# SCH_Scope_1013D_2023-01-07.net
KiCad netlist of a schematic drawn in EasyEDA
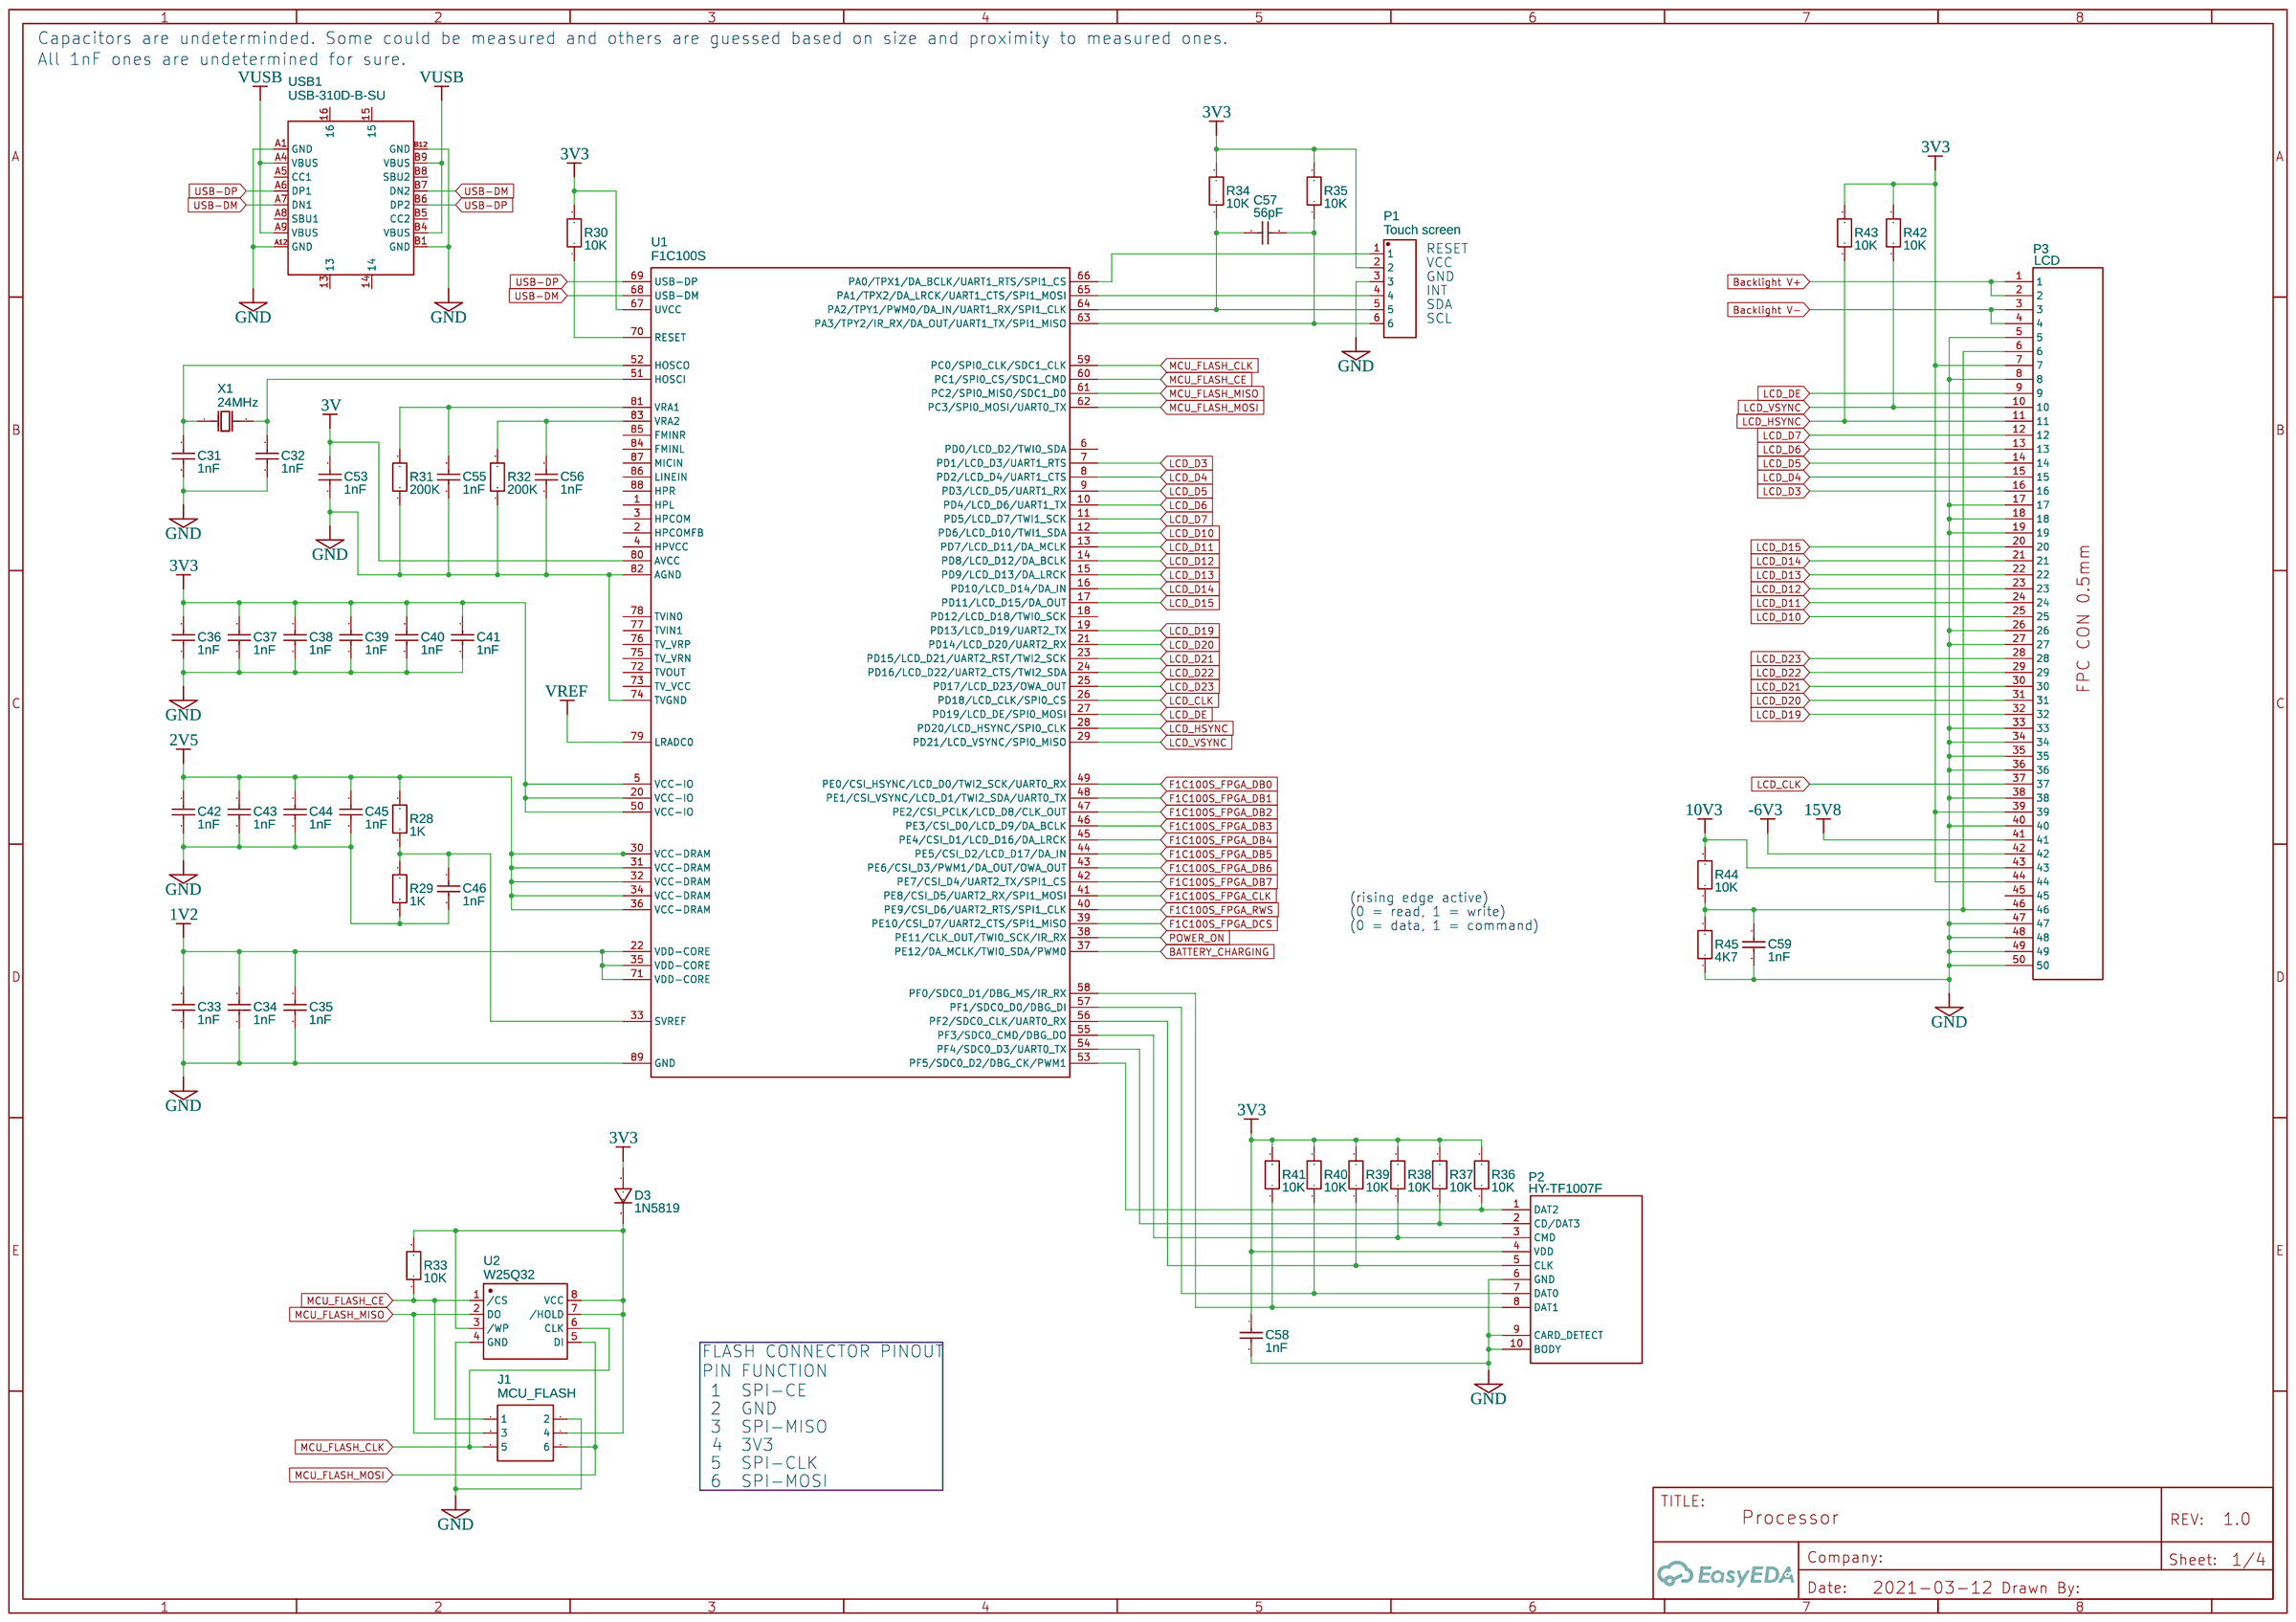
[diagram p0: Scope_Processor]
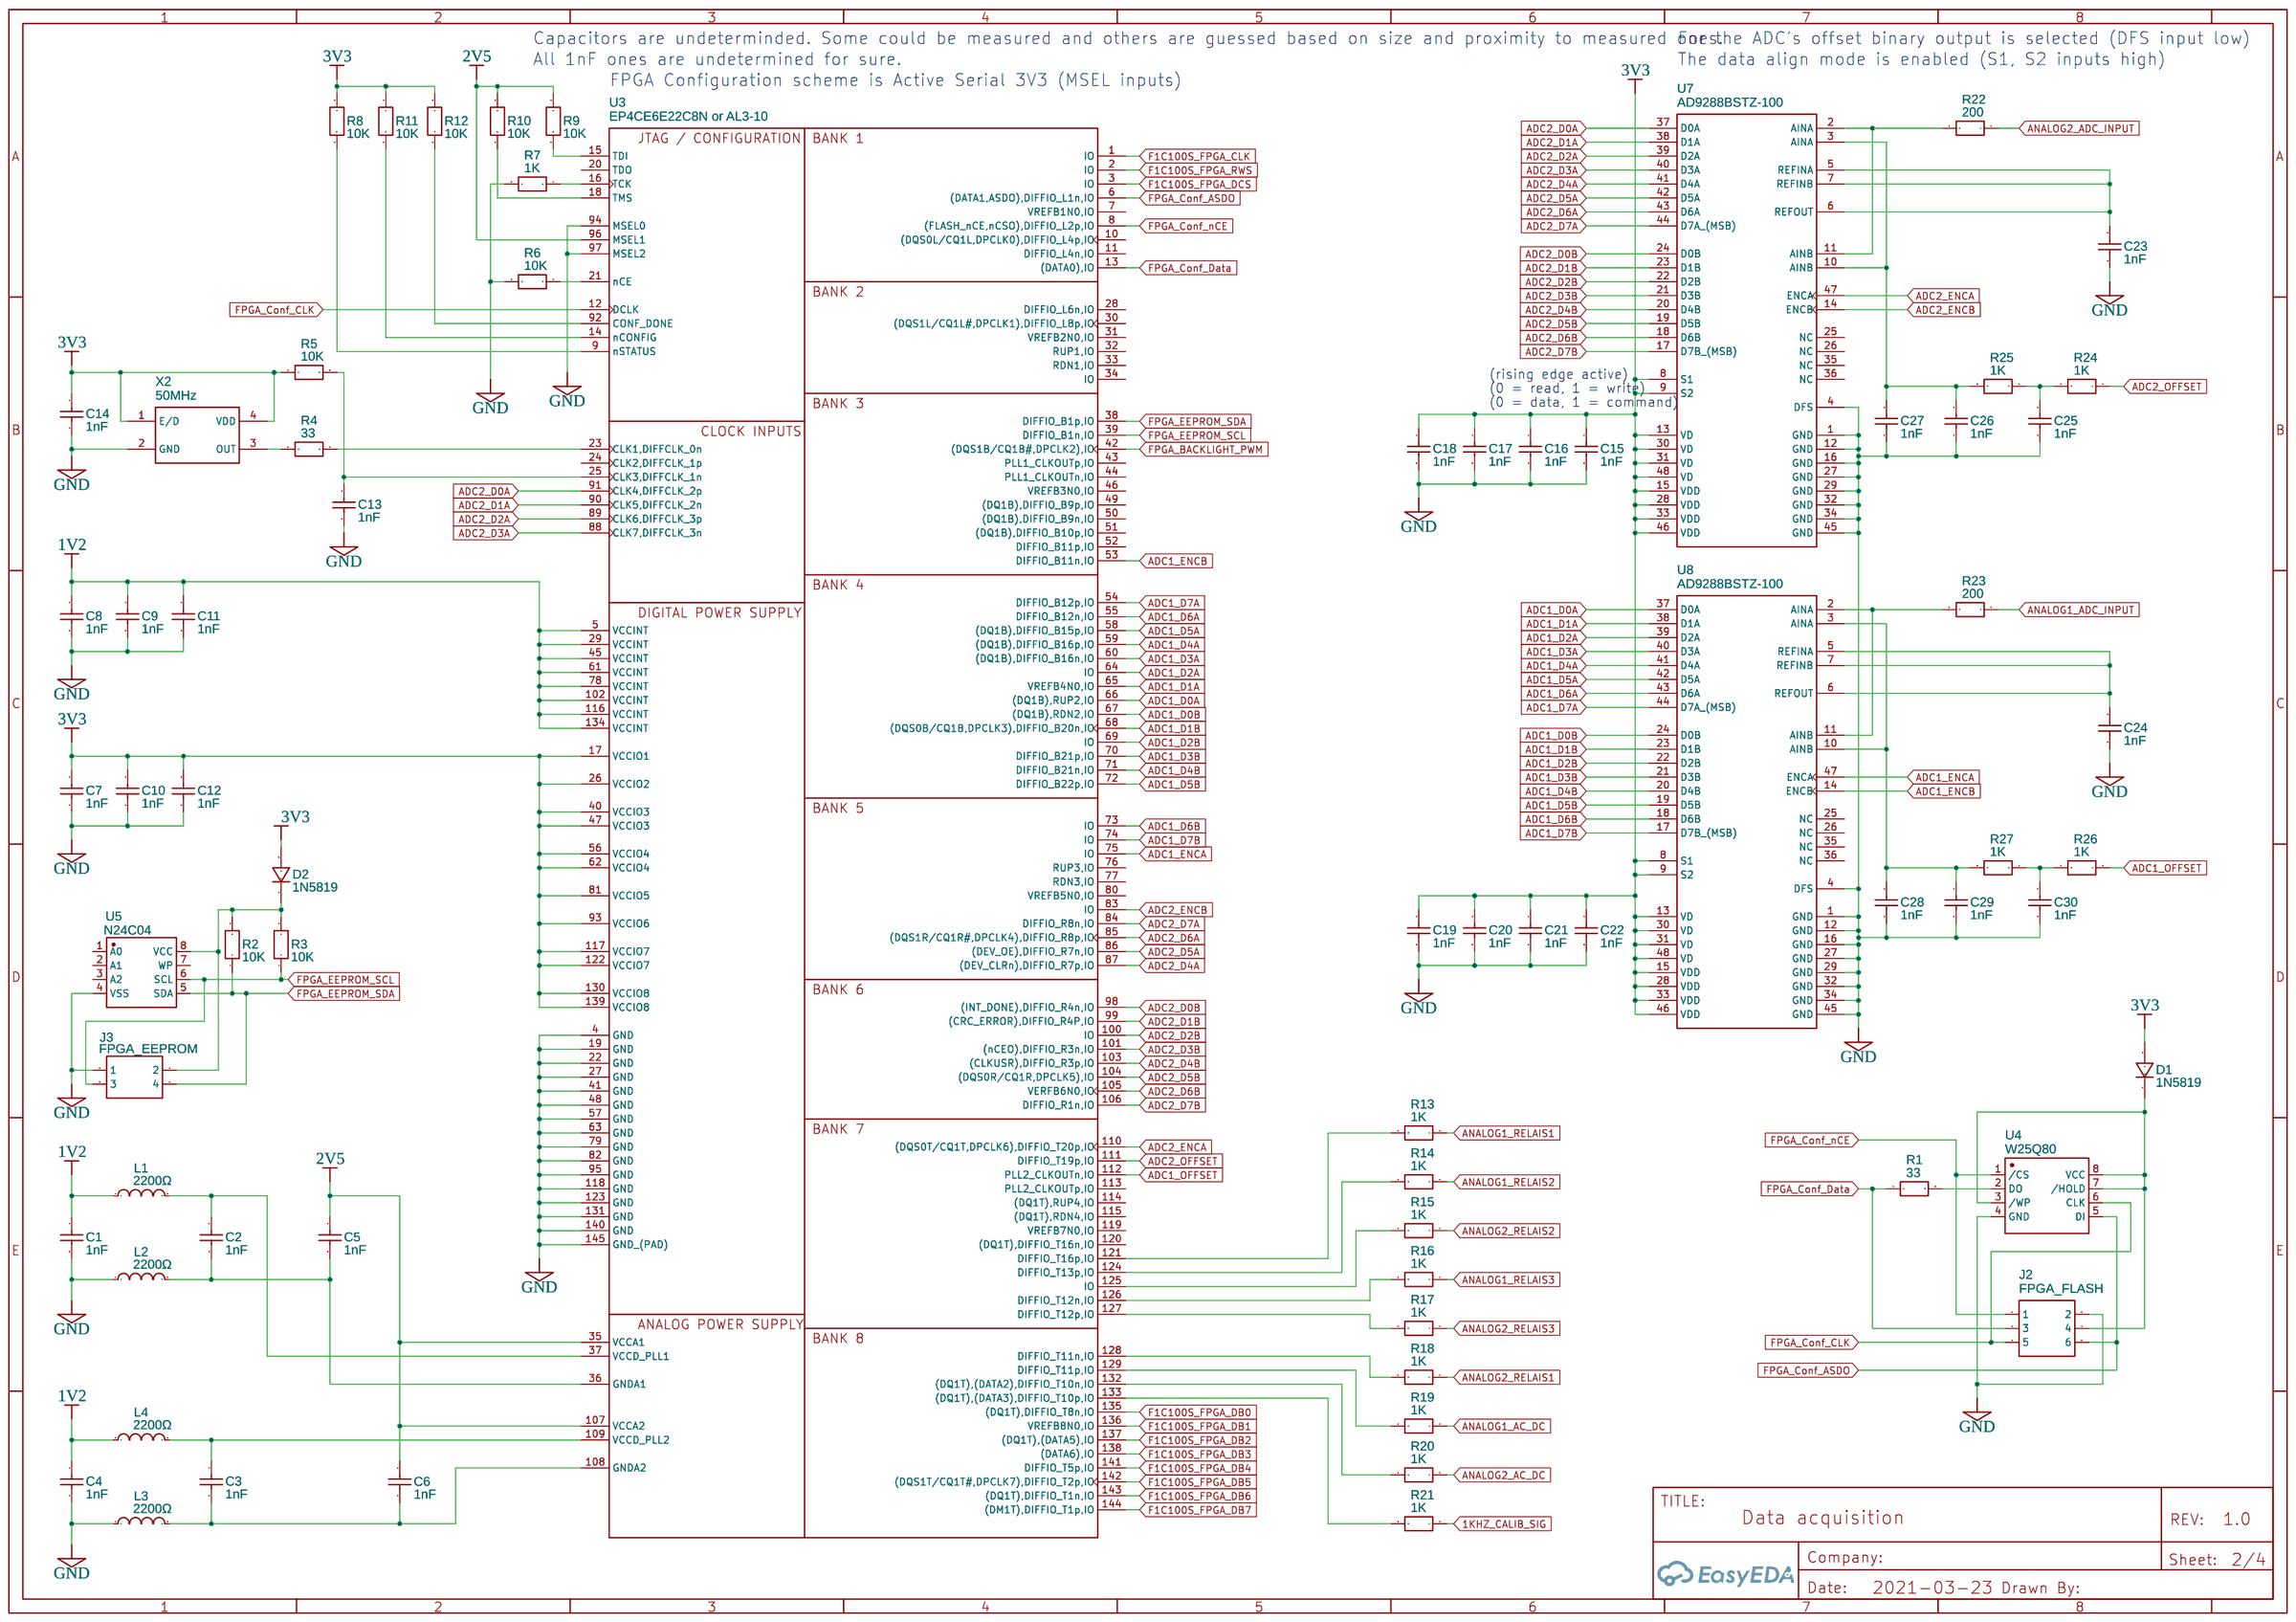
[diagram p1: Scope_Data_Acquisition]
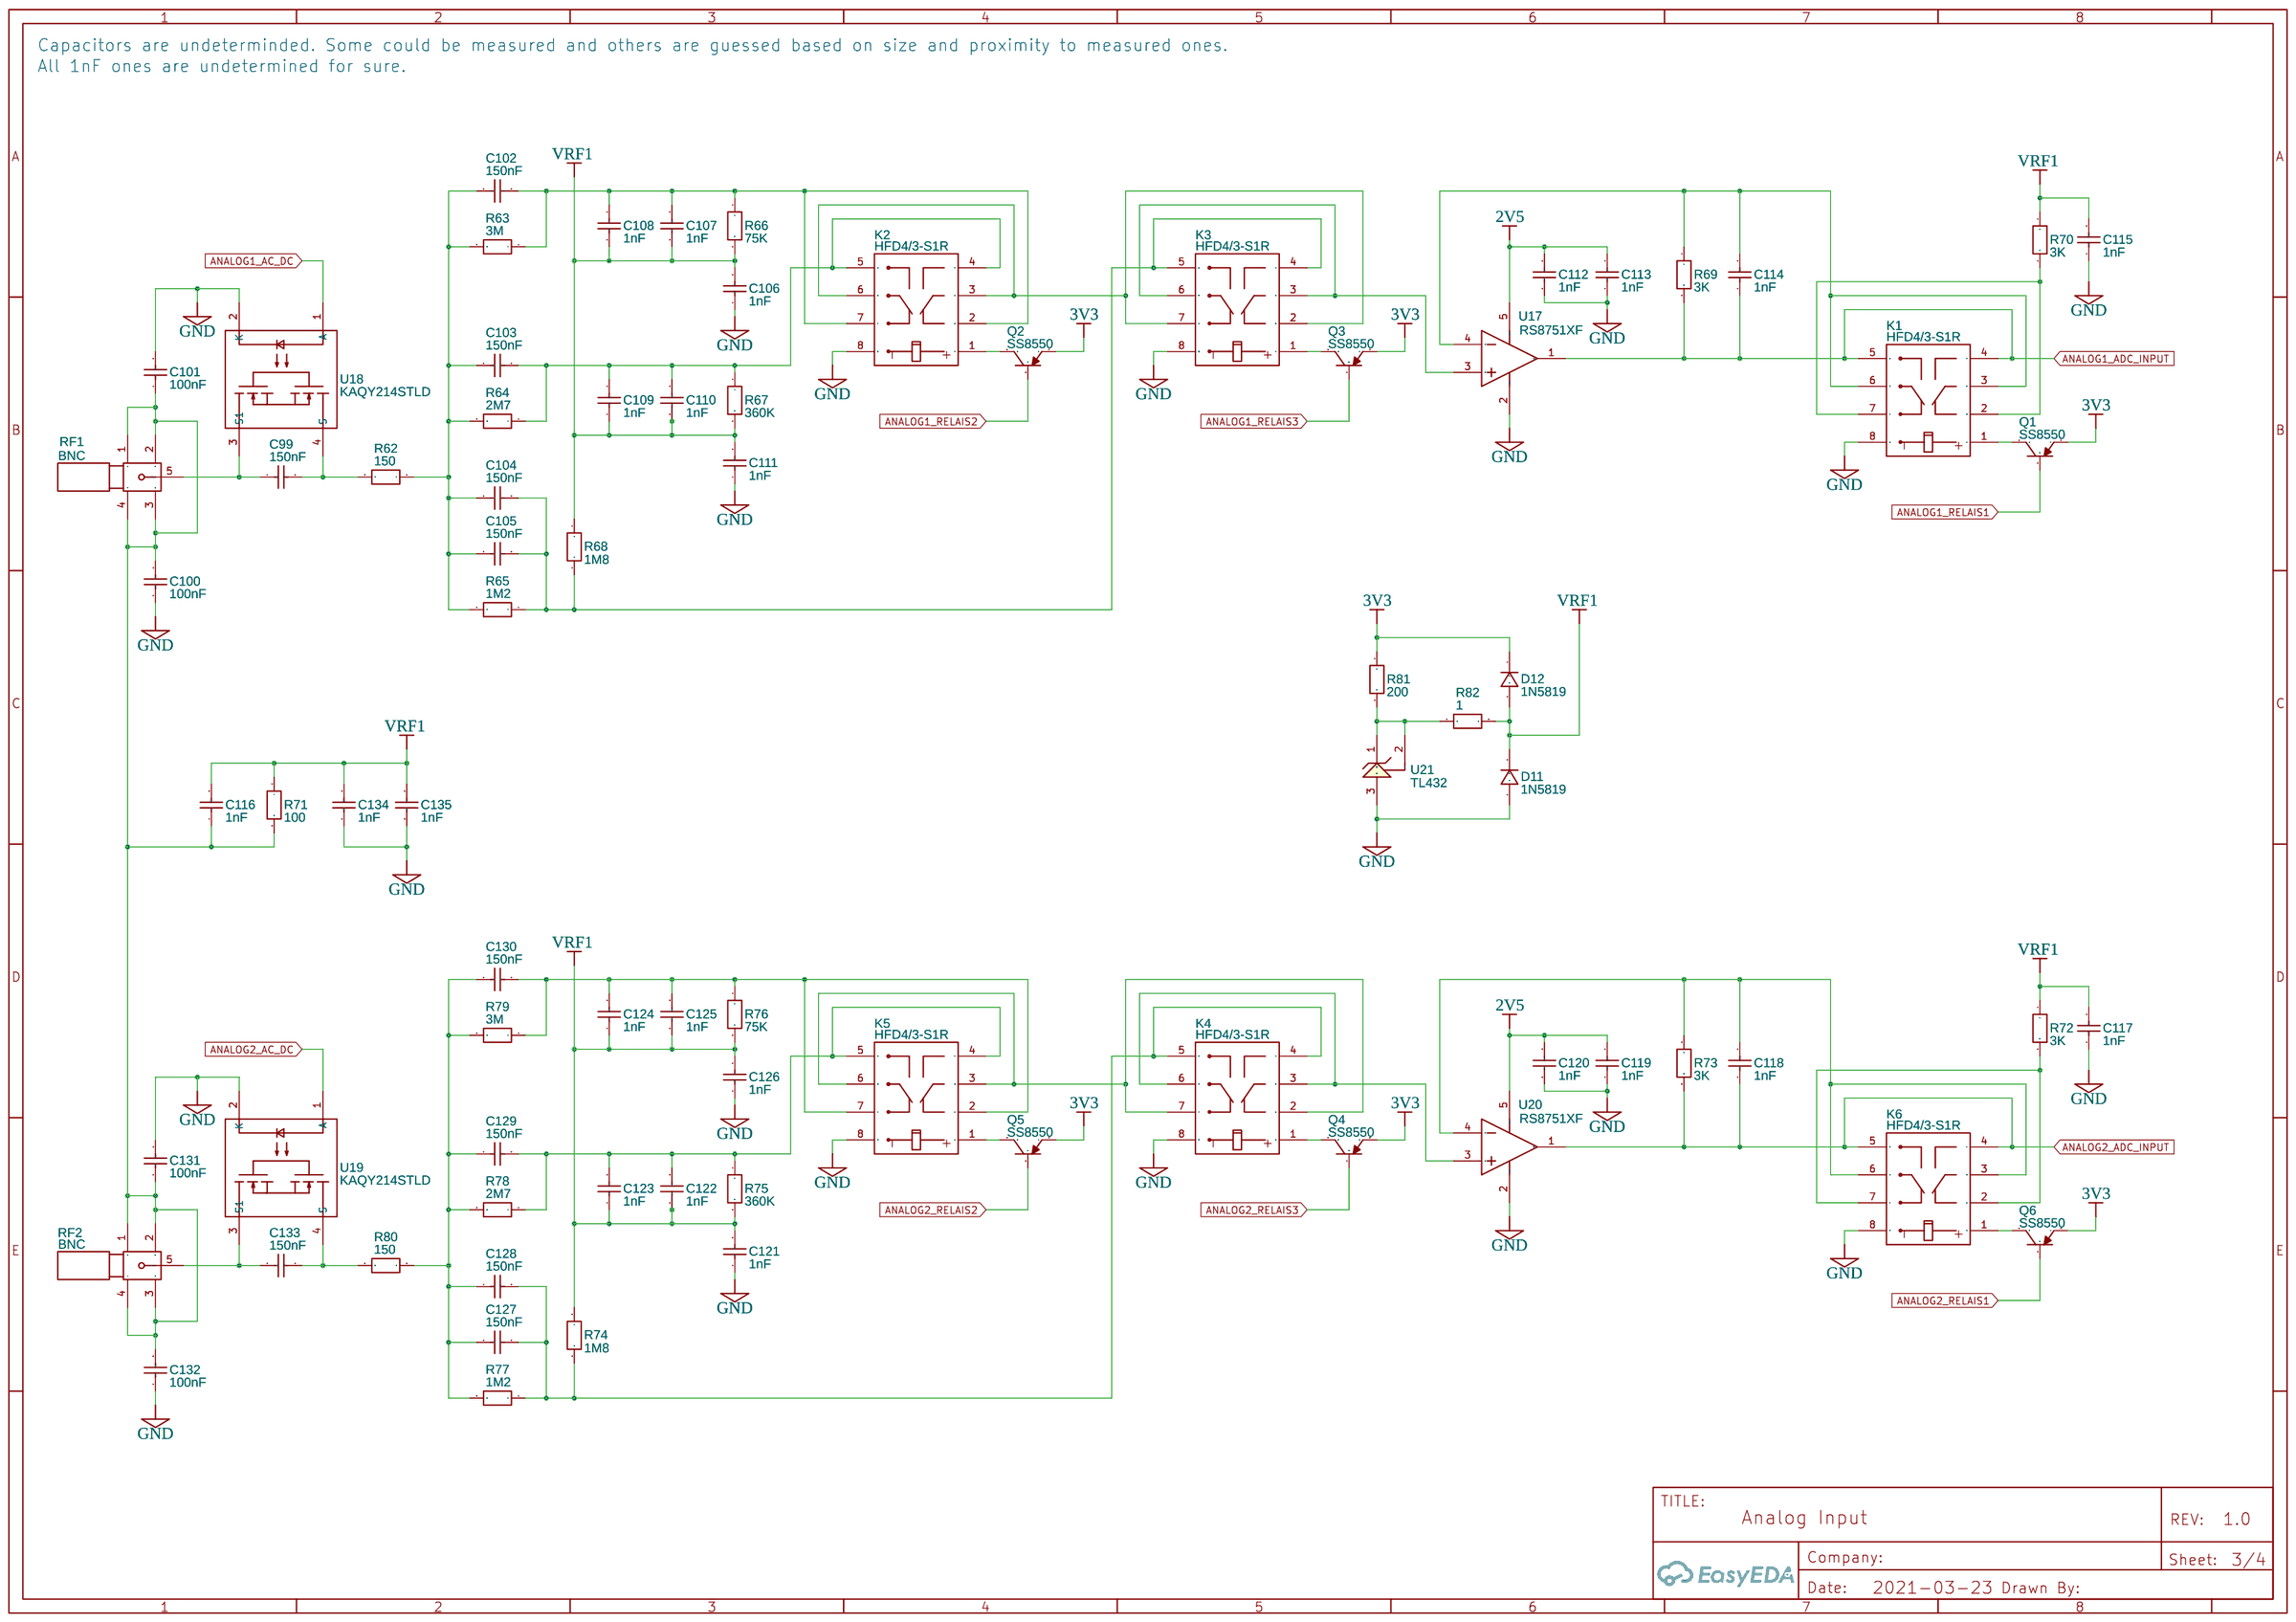
[diagram p2: Scope_Analog_Input]
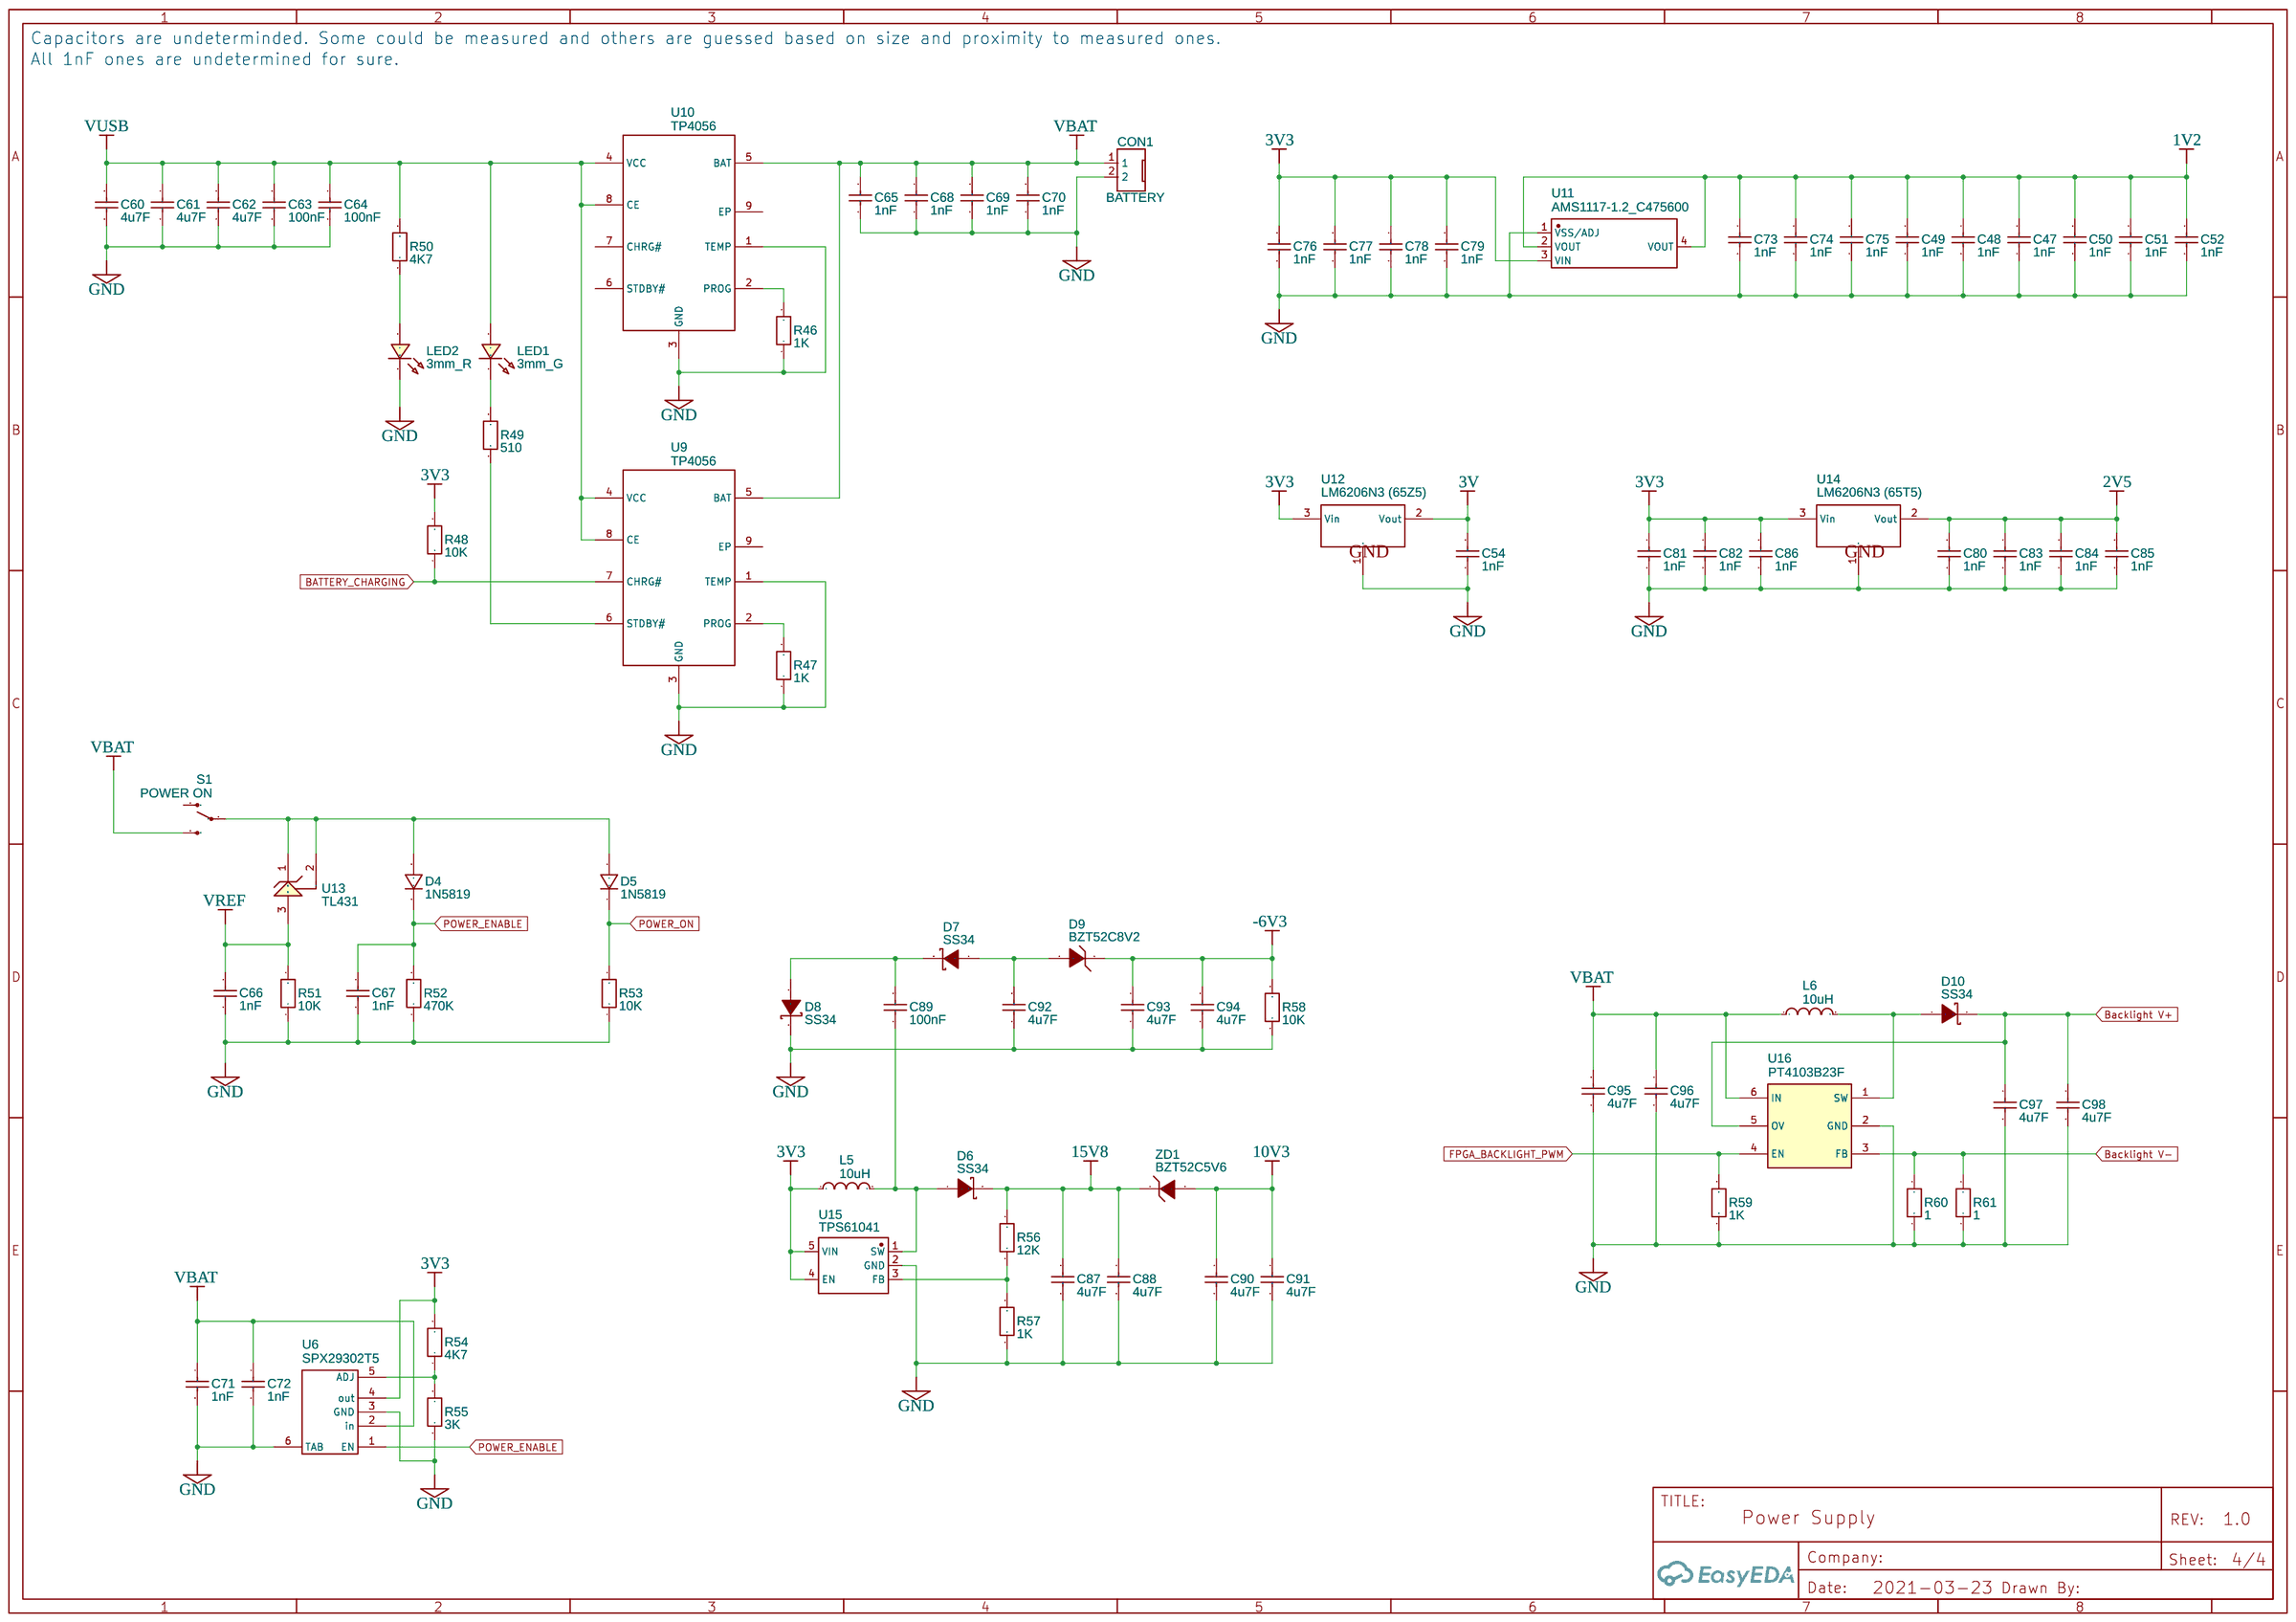
[diagram p3: Scope_Power_Supply]

(export (version "E")
  (design (tool "Eeschema 10.0.6"))
  (components
    (comp (ref "C31")
      (value "1nF")
      (fields
        (field (name "BOM_Manufacturer Part") "GRM31B7U3A471JW31L")
        (field (name "BOM_Supplier Part") "C97936")
      )
      (libsource (lib "") (part "GRM31B7U3A471JW31L"))
    )
    (comp (ref "C32")
      (value "1nF")
      (fields
        (field (name "BOM_Manufacturer Part") "GRM31B7U3A471JW31L")
        (field (name "BOM_Supplier Part") "C97936")
      )
      (libsource (lib "") (part "GRM31B7U3A471JW31L"))
    )
    (comp (ref "C33")
      (value "1nF")
      (fields
        (field (name "BOM_Manufacturer Part") "GRM31B7U3A471JW31L")
        (field (name "BOM_Supplier Part") "C97936")
      )
      (libsource (lib "") (part "GRM31B7U3A471JW31L"))
    )
    (comp (ref "C34")
      (value "1nF")
      (fields
        (field (name "BOM_Manufacturer Part") "GRM31B7U3A471JW31L")
        (field (name "BOM_Supplier Part") "C97936")
      )
      (libsource (lib "") (part "GRM31B7U3A471JW31L"))
    )
    (comp (ref "C35")
      (value "1nF")
      (fields
        (field (name "BOM_Manufacturer Part") "GRM31B7U3A471JW31L")
        (field (name "BOM_Supplier Part") "C97936")
      )
      (libsource (lib "") (part "GRM31B7U3A471JW31L"))
    )
    (comp (ref "C36")
      (value "1nF")
      (fields
        (field (name "BOM_Manufacturer Part") "GRM31B7U3A471JW31L")
        (field (name "BOM_Supplier Part") "C97936")
      )
      (libsource (lib "") (part "GRM31B7U3A471JW31L"))
    )
    (comp (ref "C37")
      (value "1nF")
      (fields
        (field (name "BOM_Manufacturer Part") "GRM31B7U3A471JW31L")
        (field (name "BOM_Supplier Part") "C97936")
      )
      (libsource (lib "") (part "GRM31B7U3A471JW31L"))
    )
    (comp (ref "C38")
      (value "1nF")
      (fields
        (field (name "BOM_Manufacturer Part") "GRM31B7U3A471JW31L")
        (field (name "BOM_Supplier Part") "C97936")
      )
      (libsource (lib "") (part "GRM31B7U3A471JW31L"))
    )
    (comp (ref "C39")
      (value "1nF")
      (fields
        (field (name "BOM_Manufacturer Part") "GRM31B7U3A471JW31L")
        (field (name "BOM_Supplier Part") "C97936")
      )
      (libsource (lib "") (part "GRM31B7U3A471JW31L"))
    )
    (comp (ref "C40")
      (value "1nF")
      (fields
        (field (name "BOM_Manufacturer Part") "GRM31B7U3A471JW31L")
        (field (name "BOM_Supplier Part") "C97936")
      )
      (libsource (lib "") (part "GRM31B7U3A471JW31L"))
    )
    (comp (ref "C41")
      (value "1nF")
      (fields
        (field (name "BOM_Manufacturer Part") "GRM31B7U3A471JW31L")
        (field (name "BOM_Supplier Part") "C97936")
      )
      (libsource (lib "") (part "GRM31B7U3A471JW31L"))
    )
    (comp (ref "C42")
      (value "1nF")
      (fields
        (field (name "BOM_Manufacturer Part") "GRM31B7U3A471JW31L")
        (field (name "BOM_Supplier Part") "C97936")
      )
      (libsource (lib "") (part "GRM31B7U3A471JW31L"))
    )
    (comp (ref "C43")
      (value "1nF")
      (fields
        (field (name "BOM_Manufacturer Part") "GRM31B7U3A471JW31L")
        (field (name "BOM_Supplier Part") "C97936")
      )
      (libsource (lib "") (part "GRM31B7U3A471JW31L"))
    )
    (comp (ref "C44")
      (value "1nF")
      (fields
        (field (name "BOM_Manufacturer Part") "GRM31B7U3A471JW31L")
        (field (name "BOM_Supplier Part") "C97936")
      )
      (libsource (lib "") (part "GRM31B7U3A471JW31L"))
    )
    (comp (ref "C45")
      (value "1nF")
      (fields
        (field (name "BOM_Manufacturer Part") "GRM31B7U3A471JW31L")
        (field (name "BOM_Supplier Part") "C97936")
      )
      (libsource (lib "") (part "GRM31B7U3A471JW31L"))
    )
    (comp (ref "C46")
      (value "1nF")
      (fields
        (field (name "BOM_Manufacturer Part") "GRM31B7U3A471JW31L")
        (field (name "BOM_Supplier Part") "C97936")
      )
      (libsource (lib "") (part "GRM31B7U3A471JW31L"))
    )
    (comp (ref "C53")
      (value "1nF")
      (fields
        (field (name "BOM_Manufacturer Part") "GRM31B7U3A471JW31L")
        (field (name "BOM_Supplier Part") "C97936")
      )
      (libsource (lib "") (part "GRM31B7U3A471JW31L"))
    )
    (comp (ref "C55")
      (value "1nF")
      (fields
        (field (name "BOM_Manufacturer Part") "GRM31B7U3A471JW31L")
        (field (name "BOM_Supplier Part") "C97936")
      )
      (libsource (lib "") (part "GRM31B7U3A471JW31L"))
    )
    (comp (ref "C56")
      (value "1nF")
      (fields
        (field (name "BOM_Manufacturer Part") "GRM31B7U3A471JW31L")
        (field (name "BOM_Supplier Part") "C97936")
      )
      (libsource (lib "") (part "GRM31B7U3A471JW31L"))
    )
    (comp (ref "C57")
      (value "56pF")
      (fields
        (field (name "BOM_Manufacturer Part") "GRM31B7U3A471JW31L")
        (field (name "BOM_Supplier Part") "C97936")
      )
      (libsource (lib "") (part "GRM31B7U3A471JW31L_1"))
    )
    (comp (ref "C58")
      (value "1nF")
      (fields
        (field (name "BOM_Manufacturer Part") "GRM31B7U3A471JW31L")
        (field (name "BOM_Supplier Part") "C97936")
      )
      (libsource (lib "") (part "GRM31B7U3A471JW31L"))
    )
    (comp (ref "C59")
      (value "1nF")
      (fields
        (field (name "BOM_Manufacturer Part") "GRM31B7U3A471JW31L")
        (field (name "BOM_Supplier Part") "C97936")
      )
      (libsource (lib "") (part "GRM31B7U3A471JW31L"))
    )
    (comp (ref "D3")
      (value "1N5819")
      (fields (field (name "BOM_Manufacturer Part") "1N4007") (field (name "BOM_Supplier Part") "C106903"))
      (libsource (lib "") (part "1N4007"))
    )
    (comp (ref "J1")
      (value "MCU_FLASH")
      (fields (field (name "BOM_Supplier Part") "C65114"))
      (libsource (lib "") (part "HDR-M-2.54_2x3"))
    )
    (comp (ref "P1")
      (value "Touch screen")
      (fields (field (name "BOM_Supplier Part") "C11049"))
      (libsource (lib "") (part "FPC-0.5MM-LSXJ-H2.0-6P"))
    )
    (comp (ref "P2")
      (value "HY-TF1007F")
      (fields (field (name "BOM_Supplier Part") "undefined"))
      (libsource (lib "") (part "HY-TF1007F"))
    )
    (comp (ref "P3") (value "LCD") (libsource (lib "") (part "FPC CONNECTOR 50P 0.5mm")))
    (comp (ref "R28") (value "1K") (libsource (lib "") (part "R_0805_EU")))
    (comp (ref "R29") (value "1K") (libsource (lib "") (part "R_0805_EU")))
    (comp (ref "R30") (value "10K") (libsource (lib "") (part "R_0805_EU")))
    (comp (ref "R31") (value "200K") (libsource (lib "") (part "R_0805_EU")))
    (comp (ref "R32") (value "200K") (libsource (lib "") (part "R_0805_EU")))
    (comp (ref "R33") (value "10K") (libsource (lib "") (part "R_0805_EU")))
    (comp (ref "R34") (value "10K") (libsource (lib "") (part "R_0805_EU")))
    (comp (ref "R35") (value "10K") (libsource (lib "") (part "R_0805_EU")))
    (comp (ref "R36") (value "10K") (libsource (lib "") (part "R_0805_EU")))
    (comp (ref "R37") (value "10K") (libsource (lib "") (part "R_0805_EU")))
    (comp (ref "R38") (value "10K") (libsource (lib "") (part "R_0805_EU")))
    (comp (ref "R39") (value "10K") (libsource (lib "") (part "R_0805_EU")))
    (comp (ref "R40") (value "10K") (libsource (lib "") (part "R_0805_EU")))
    (comp (ref "R41") (value "10K") (libsource (lib "") (part "R_0805_EU")))
    (comp (ref "R42") (value "10K") (libsource (lib "") (part "R_0805_EU")))
    (comp (ref "R43") (value "10K") (libsource (lib "") (part "R_0805_EU")))
    (comp (ref "R44") (value "10K") (libsource (lib "") (part "R_0805_EU")))
    (comp (ref "R45") (value "4K7") (libsource (lib "") (part "R_0805_EU")))
    (comp (ref "U1") (value "F1C100S") (libsource (lib "") (part "F1C100S")))
    (comp (ref "U2")
      (value "W25Q32")
      (fields
        (field (name "BOM_Manufacturer Part") "W25Q32FVSSIGTR")
        (field (name "BOM_Supplier Part") "C108057")
      )
      (libsource (lib "") (part "W25Q32FVSSIGTR"))
    )
    (comp (ref "USB1")
      (value "USB-310D-B-SU")
      (fields (field (name "BOM_Supplier Part") "C309349"))
      (libsource (lib "") (part "USB-310D-B-SU"))
    )
    (comp (ref "X1")
      (value "24MHz")
      (fields
        (field (name "BOM_Manufacturer Part") "X503224MSD2GC")
        (field (name "BOM_Supplier Part") "C48304")
      )
      (libsource (lib "") (part "X503224MSD2GC"))
    )
    (comp (ref "C1")
      (value "1nF")
      (fields
        (field (name "BOM_Manufacturer Part") "GRM31B7U3A471JW31L")
        (field (name "BOM_Supplier Part") "C97936")
      )
      (libsource (lib "") (part "GRM31B7U3A471JW31L"))
    )
    (comp (ref "C2")
      (value "1nF")
      (fields
        (field (name "BOM_Manufacturer Part") "GRM31B7U3A471JW31L")
        (field (name "BOM_Supplier Part") "C97936")
      )
      (libsource (lib "") (part "GRM31B7U3A471JW31L"))
    )
    (comp (ref "C3")
      (value "1nF")
      (fields
        (field (name "BOM_Manufacturer Part") "GRM31B7U3A471JW31L")
        (field (name "BOM_Supplier Part") "C97936")
      )
      (libsource (lib "") (part "GRM31B7U3A471JW31L"))
    )
    (comp (ref "C4")
      (value "1nF")
      (fields
        (field (name "BOM_Manufacturer Part") "GRM31B7U3A471JW31L")
        (field (name "BOM_Supplier Part") "C97936")
      )
      (libsource (lib "") (part "GRM31B7U3A471JW31L"))
    )
    (comp (ref "C5")
      (value "1nF")
      (fields
        (field (name "BOM_Manufacturer Part") "GRM31B7U3A471JW31L")
        (field (name "BOM_Supplier Part") "C97936")
      )
      (libsource (lib "") (part "GRM31B7U3A471JW31L"))
    )
    (comp (ref "C6")
      (value "1nF")
      (fields
        (field (name "BOM_Manufacturer Part") "GRM31B7U3A471JW31L")
        (field (name "BOM_Supplier Part") "C97936")
      )
      (libsource (lib "") (part "GRM31B7U3A471JW31L_1"))
    )
    (comp (ref "C7")
      (value "1nF")
      (fields
        (field (name "BOM_Manufacturer Part") "GRM31B7U3A471JW31L")
        (field (name "BOM_Supplier Part") "C97936")
      )
      (libsource (lib "") (part "GRM31B7U3A471JW31L"))
    )
    (comp (ref "C8")
      (value "1nF")
      (fields
        (field (name "BOM_Manufacturer Part") "GRM31B7U3A471JW31L")
        (field (name "BOM_Supplier Part") "C97936")
      )
      (libsource (lib "") (part "GRM31B7U3A471JW31L"))
    )
    (comp (ref "C9")
      (value "1nF")
      (fields
        (field (name "BOM_Manufacturer Part") "GRM31B7U3A471JW31L")
        (field (name "BOM_Supplier Part") "C97936")
      )
      (libsource (lib "") (part "GRM31B7U3A471JW31L"))
    )
    (comp (ref "C10")
      (value "1nF")
      (fields
        (field (name "BOM_Manufacturer Part") "GRM31B7U3A471JW31L")
        (field (name "BOM_Supplier Part") "C97936")
      )
      (libsource (lib "") (part "GRM31B7U3A471JW31L"))
    )
    (comp (ref "C11")
      (value "1nF")
      (fields
        (field (name "BOM_Manufacturer Part") "GRM31B7U3A471JW31L")
        (field (name "BOM_Supplier Part") "C97936")
      )
      (libsource (lib "") (part "GRM31B7U3A471JW31L"))
    )
    (comp (ref "C12")
      (value "1nF")
      (fields
        (field (name "BOM_Manufacturer Part") "GRM31B7U3A471JW31L")
        (field (name "BOM_Supplier Part") "C97936")
      )
      (libsource (lib "") (part "GRM31B7U3A471JW31L"))
    )
    (comp (ref "C13")
      (value "1nF")
      (fields
        (field (name "BOM_Manufacturer Part") "GRM31B7U3A471JW31L")
        (field (name "BOM_Supplier Part") "C97936")
      )
      (libsource (lib "") (part "GRM31B7U3A471JW31L"))
    )
    (comp (ref "C14")
      (value "1nF")
      (fields
        (field (name "BOM_Manufacturer Part") "GRM31B7U3A471JW31L")
        (field (name "BOM_Supplier Part") "C97936")
      )
      (libsource (lib "") (part "GRM31B7U3A471JW31L"))
    )
    (comp (ref "C15")
      (value "1nF")
      (fields
        (field (name "BOM_Manufacturer Part") "GRM31B7U3A471JW31L")
        (field (name "BOM_Supplier Part") "C97936")
      )
      (libsource (lib "") (part "GRM31B7U3A471JW31L"))
    )
    (comp (ref "C16")
      (value "1nF")
      (fields
        (field (name "BOM_Manufacturer Part") "GRM31B7U3A471JW31L")
        (field (name "BOM_Supplier Part") "C97936")
      )
      (libsource (lib "") (part "GRM31B7U3A471JW31L"))
    )
    (comp (ref "C17")
      (value "1nF")
      (fields
        (field (name "BOM_Manufacturer Part") "GRM31B7U3A471JW31L")
        (field (name "BOM_Supplier Part") "C97936")
      )
      (libsource (lib "") (part "GRM31B7U3A471JW31L"))
    )
    (comp (ref "C18")
      (value "1nF")
      (fields
        (field (name "BOM_Manufacturer Part") "GRM31B7U3A471JW31L")
        (field (name "BOM_Supplier Part") "C97936")
      )
      (libsource (lib "") (part "GRM31B7U3A471JW31L"))
    )
    (comp (ref "C19")
      (value "1nF")
      (fields
        (field (name "BOM_Manufacturer Part") "GRM31B7U3A471JW31L")
        (field (name "BOM_Supplier Part") "C97936")
      )
      (libsource (lib "") (part "GRM31B7U3A471JW31L"))
    )
    (comp (ref "C20")
      (value "1nF")
      (fields
        (field (name "BOM_Manufacturer Part") "GRM31B7U3A471JW31L")
        (field (name "BOM_Supplier Part") "C97936")
      )
      (libsource (lib "") (part "GRM31B7U3A471JW31L"))
    )
    (comp (ref "C21")
      (value "1nF")
      (fields
        (field (name "BOM_Manufacturer Part") "GRM31B7U3A471JW31L")
        (field (name "BOM_Supplier Part") "C97936")
      )
      (libsource (lib "") (part "GRM31B7U3A471JW31L"))
    )
    (comp (ref "C22")
      (value "1nF")
      (fields
        (field (name "BOM_Manufacturer Part") "GRM31B7U3A471JW31L")
        (field (name "BOM_Supplier Part") "C97936")
      )
      (libsource (lib "") (part "GRM31B7U3A471JW31L"))
    )
    (comp (ref "C23")
      (value "1nF")
      (fields
        (field (name "BOM_Manufacturer Part") "GRM31B7U3A471JW31L")
        (field (name "BOM_Supplier Part") "C97936")
      )
      (libsource (lib "") (part "GRM31B7U3A471JW31L"))
    )
    (comp (ref "C24")
      (value "1nF")
      (fields
        (field (name "BOM_Manufacturer Part") "GRM31B7U3A471JW31L")
        (field (name "BOM_Supplier Part") "C97936")
      )
      (libsource (lib "") (part "GRM31B7U3A471JW31L"))
    )
    (comp (ref "C25")
      (value "1nF")
      (fields
        (field (name "BOM_Manufacturer Part") "GRM31B7U3A471JW31L")
        (field (name "BOM_Supplier Part") "C97936")
      )
      (libsource (lib "") (part "GRM31B7U3A471JW31L"))
    )
    (comp (ref "C26")
      (value "1nF")
      (fields
        (field (name "BOM_Manufacturer Part") "GRM31B7U3A471JW31L")
        (field (name "BOM_Supplier Part") "C97936")
      )
      (libsource (lib "") (part "GRM31B7U3A471JW31L"))
    )
    (comp (ref "C27")
      (value "1nF")
      (fields
        (field (name "BOM_Manufacturer Part") "GRM31B7U3A471JW31L")
        (field (name "BOM_Supplier Part") "C97936")
      )
      (libsource (lib "") (part "GRM31B7U3A471JW31L"))
    )
    (comp (ref "C28")
      (value "1nF")
      (fields
        (field (name "BOM_Manufacturer Part") "GRM31B7U3A471JW31L")
        (field (name "BOM_Supplier Part") "C97936")
      )
      (libsource (lib "") (part "GRM31B7U3A471JW31L"))
    )
    (comp (ref "C29")
      (value "1nF")
      (fields
        (field (name "BOM_Manufacturer Part") "GRM31B7U3A471JW31L")
        (field (name "BOM_Supplier Part") "C97936")
      )
      (libsource (lib "") (part "GRM31B7U3A471JW31L"))
    )
    (comp (ref "C30")
      (value "1nF")
      (fields
        (field (name "BOM_Manufacturer Part") "GRM31B7U3A471JW31L")
        (field (name "BOM_Supplier Part") "C97936")
      )
      (libsource (lib "") (part "GRM31B7U3A471JW31L"))
    )
    (comp (ref "D1")
      (value "1N5819")
      (fields (field (name "BOM_Manufacturer Part") "1N4007") (field (name "BOM_Supplier Part") "C106903"))
      (libsource (lib "") (part "1N4007"))
    )
    (comp (ref "D2")
      (value "1N5819")
      (fields (field (name "BOM_Manufacturer Part") "1N4007") (field (name "BOM_Supplier Part") "C106903"))
      (libsource (lib "") (part "1N4007"))
    )
    (comp (ref "J2")
      (value "FPGA_FLASH")
      (fields (field (name "BOM_Supplier Part") "C65114"))
      (libsource (lib "") (part "HDR-M-2.54_2x3"))
    )
    (comp (ref "J3")
      (value "FPGA_EEPROM")
      (fields (field (name "BOM_Supplier Part") "C66690"))
      (libsource (lib "") (part "HDR-M-2.54_2x2"))
    )
    (comp (ref "L1")
      (value "2200Ω")
      (fields
        (field (name "BOM_Manufacturer Part") "BLM21PG221SN1D")
        (field (name "BOM_Supplier Part") "C85840")
      )
      (libsource (lib "") (part "BLM21PG221SN1D"))
    )
    (comp (ref "L2")
      (value "2200Ω")
      (fields
        (field (name "BOM_Manufacturer Part") "BLM21PG221SN1D")
        (field (name "BOM_Supplier Part") "C85840")
      )
      (libsource (lib "") (part "BLM21PG221SN1D"))
    )
    (comp (ref "L3")
      (value "2200Ω")
      (fields
        (field (name "BOM_Manufacturer Part") "BLM21PG221SN1D")
        (field (name "BOM_Supplier Part") "C85840")
      )
      (libsource (lib "") (part "BLM21PG221SN1D"))
    )
    (comp (ref "L4")
      (value "2200Ω")
      (fields
        (field (name "BOM_Manufacturer Part") "BLM21PG221SN1D")
        (field (name "BOM_Supplier Part") "C85840")
      )
      (libsource (lib "") (part "BLM21PG221SN1D"))
    )
    (comp (ref "R1") (value "33") (libsource (lib "") (part "R_0805_EU_3")))
    (comp (ref "R2") (value "10K") (libsource (lib "") (part "R_0805_EU_2")))
    (comp (ref "R3") (value "10K") (libsource (lib "") (part "R_0805_EU_2")))
    (comp (ref "R4") (value "33") (libsource (lib "") (part "R_0805_EU")))
    (comp (ref "R5") (value "10K") (libsource (lib "") (part "R_0805_EU_3")))
    (comp (ref "R6") (value "10K") (libsource (lib "") (part "R_0805_EU")))
    (comp (ref "R7") (value "1K") (libsource (lib "") (part "R_0805_EU")))
    (comp (ref "R8") (value "10K") (libsource (lib "") (part "R_0805_EU_1")))
    (comp (ref "R9") (value "10K") (libsource (lib "") (part "R_0805_EU_1")))
    (comp (ref "R10") (value "10K") (libsource (lib "") (part "R_0805_EU_1")))
    (comp (ref "R11") (value "10K") (libsource (lib "") (part "R_0805_EU_1")))
    (comp (ref "R12") (value "10K") (libsource (lib "") (part "R_0805_EU_1")))
    (comp (ref "R13") (value "1K") (libsource (lib "") (part "R_0805_EU")))
    (comp (ref "R14") (value "1K") (libsource (lib "") (part "R_0805_EU")))
    (comp (ref "R15") (value "1K") (libsource (lib "") (part "R_0805_EU")))
    (comp (ref "R16") (value "1K") (libsource (lib "") (part "R_0805_EU")))
    (comp (ref "R17") (value "1K") (libsource (lib "") (part "R_0805_EU")))
    (comp (ref "R18") (value "1K") (libsource (lib "") (part "R_0805_EU")))
    (comp (ref "R19") (value "1K") (libsource (lib "") (part "R_0805_EU")))
    (comp (ref "R20") (value "1K") (libsource (lib "") (part "R_0805_EU")))
    (comp (ref "R21") (value "1K") (libsource (lib "") (part "R_0805_EU")))
    (comp (ref "R22") (value "200") (libsource (lib "") (part "R_0805_EU")))
    (comp (ref "R23") (value "200") (libsource (lib "") (part "R_0805_EU")))
    (comp (ref "R24") (value "1K") (libsource (lib "") (part "R_0805_EU")))
    (comp (ref "R25") (value "1K") (libsource (lib "") (part "R_0805_EU")))
    (comp (ref "R26") (value "1K") (libsource (lib "") (part "R_0805_EU")))
    (comp (ref "R27") (value "1K") (libsource (lib "") (part "R_0805_EU")))
    (comp (ref "U3") (value "EP4CE6E22C8N or AL3-10") (libsource (lib "") (part "EP4CE6E22C8N")))
    (comp (ref "U4")
      (value "W25Q80")
      (fields
        (field (name "BOM_Manufacturer Part") "W25Q32FVSSIGTR")
        (field (name "BOM_Supplier Part") "C108057")
      )
      (libsource (lib "") (part "W25Q32FVSSIGTR"))
    )
    (comp (ref "U5")
      (value "N24C04")
      (fields
        (field (name "BOM_Manufacturer Part") "24LC04BT-I/SN")
        (field (name "BOM_Supplier Part") "C511263")
      )
      (libsource (lib "") (part "24LC04BT-I/SN"))
    )
    (comp (ref "U7") (value "AD9288BSTZ-100") (libsource (lib "") (part "AD9288BSTZ-100")))
    (comp (ref "U8") (value "AD9288BSTZ-100") (libsource (lib "") (part "AD9288BSTZ-100")))
    (comp (ref "X2")
      (value "50MHz")
      (fields
        (field (name "BOM_Manufacturer Part") "O705050MEEA4SC 50MHZ±25PPM")
        (field (name "BOM_Supplier Part") "C112970")
      )
      (libsource (lib "") (part "O705050MEEA4SC 50MHZ±25PPM"))
    )
    (comp (ref "C99")
      (value "150nF")
      (fields
        (field (name "BOM_Manufacturer Part") "GRM31B7U3A471JW31L")
        (field (name "BOM_Supplier Part") "C97936")
      )
      (libsource (lib "") (part "GRM31B7U3A471JW31L_1"))
    )
    (comp (ref "C100")
      (value "100nF")
      (fields
        (field (name "BOM_Manufacturer Part") "GRM31B7U3A471JW31L")
        (field (name "BOM_Supplier Part") "C97936")
      )
      (libsource (lib "") (part "GRM31B7U3A471JW31L"))
    )
    (comp (ref "C101")
      (value "100nF")
      (fields
        (field (name "BOM_Manufacturer Part") "GRM31B7U3A471JW31L")
        (field (name "BOM_Supplier Part") "C97936")
      )
      (libsource (lib "") (part "GRM31B7U3A471JW31L"))
    )
    (comp (ref "C102")
      (value "150nF")
      (fields
        (field (name "BOM_Manufacturer Part") "GRM31B7U3A471JW31L")
        (field (name "BOM_Supplier Part") "C97936")
      )
      (libsource (lib "") (part "GRM31B7U3A471JW31L_1"))
    )
    (comp (ref "C103")
      (value "150nF")
      (fields
        (field (name "BOM_Manufacturer Part") "GRM31B7U3A471JW31L")
        (field (name "BOM_Supplier Part") "C97936")
      )
      (libsource (lib "") (part "GRM31B7U3A471JW31L_1"))
    )
    (comp (ref "C104")
      (value "150nF")
      (fields
        (field (name "BOM_Manufacturer Part") "GRM31B7U3A471JW31L")
        (field (name "BOM_Supplier Part") "C97936")
      )
      (libsource (lib "") (part "GRM31B7U3A471JW31L_1"))
    )
    (comp (ref "C105")
      (value "150nF")
      (fields
        (field (name "BOM_Manufacturer Part") "GRM31B7U3A471JW31L")
        (field (name "BOM_Supplier Part") "C97936")
      )
      (libsource (lib "") (part "GRM31B7U3A471JW31L_1"))
    )
    (comp (ref "C106")
      (value "1nF")
      (fields
        (field (name "BOM_Manufacturer Part") "GRM31B7U3A471JW31L")
        (field (name "BOM_Supplier Part") "C97936")
      )
      (libsource (lib "") (part "GRM31B7U3A471JW31L"))
    )
    (comp (ref "C107")
      (value "1nF")
      (fields
        (field (name "BOM_Manufacturer Part") "GRM31B7U3A471JW31L")
        (field (name "BOM_Supplier Part") "C97936")
      )
      (libsource (lib "") (part "GRM31B7U3A471JW31L"))
    )
    (comp (ref "C108")
      (value "1nF")
      (fields
        (field (name "BOM_Manufacturer Part") "GRM31B7U3A471JW31L")
        (field (name "BOM_Supplier Part") "C97936")
      )
      (libsource (lib "") (part "GRM31B7U3A471JW31L"))
    )
    (comp (ref "C109")
      (value "1nF")
      (fields
        (field (name "BOM_Manufacturer Part") "GRM31B7U3A471JW31L")
        (field (name "BOM_Supplier Part") "C97936")
      )
      (libsource (lib "") (part "GRM31B7U3A471JW31L"))
    )
    (comp (ref "C110")
      (value "1nF")
      (fields
        (field (name "BOM_Manufacturer Part") "GRM31B7U3A471JW31L")
        (field (name "BOM_Supplier Part") "C97936")
      )
      (libsource (lib "") (part "GRM31B7U3A471JW31L"))
    )
    (comp (ref "C111")
      (value "1nF")
      (fields
        (field (name "BOM_Manufacturer Part") "GRM31B7U3A471JW31L")
        (field (name "BOM_Supplier Part") "C97936")
      )
      (libsource (lib "") (part "GRM31B7U3A471JW31L"))
    )
    (comp (ref "C112")
      (value "1nF")
      (fields
        (field (name "BOM_Manufacturer Part") "GRM31B7U3A471JW31L")
        (field (name "BOM_Supplier Part") "C97936")
      )
      (libsource (lib "") (part "GRM31B7U3A471JW31L"))
    )
    (comp (ref "C113")
      (value "1nF")
      (fields
        (field (name "BOM_Manufacturer Part") "GRM31B7U3A471JW31L")
        (field (name "BOM_Supplier Part") "C97936")
      )
      (libsource (lib "") (part "GRM31B7U3A471JW31L"))
    )
    (comp (ref "C114")
      (value "1nF")
      (fields
        (field (name "BOM_Manufacturer Part") "GRM31B7U3A471JW31L")
        (field (name "BOM_Supplier Part") "C97936")
      )
      (libsource (lib "") (part "GRM31B7U3A471JW31L"))
    )
    (comp (ref "C115")
      (value "1nF")
      (fields
        (field (name "BOM_Manufacturer Part") "GRM31B7U3A471JW31L")
        (field (name "BOM_Supplier Part") "C97936")
      )
      (libsource (lib "") (part "GRM31B7U3A471JW31L"))
    )
    (comp (ref "C116")
      (value "1nF")
      (fields
        (field (name "BOM_Manufacturer Part") "GRM31B7U3A471JW31L")
        (field (name "BOM_Supplier Part") "C97936")
      )
      (libsource (lib "") (part "GRM31B7U3A471JW31L"))
    )
    (comp (ref "C117")
      (value "1nF")
      (fields
        (field (name "BOM_Manufacturer Part") "GRM31B7U3A471JW31L")
        (field (name "BOM_Supplier Part") "C97936")
      )
      (libsource (lib "") (part "GRM31B7U3A471JW31L"))
    )
    (comp (ref "C118")
      (value "1nF")
      (fields
        (field (name "BOM_Manufacturer Part") "GRM31B7U3A471JW31L")
        (field (name "BOM_Supplier Part") "C97936")
      )
      (libsource (lib "") (part "GRM31B7U3A471JW31L"))
    )
    (comp (ref "C119")
      (value "1nF")
      (fields
        (field (name "BOM_Manufacturer Part") "GRM31B7U3A471JW31L")
        (field (name "BOM_Supplier Part") "C97936")
      )
      (libsource (lib "") (part "GRM31B7U3A471JW31L"))
    )
    (comp (ref "C120")
      (value "1nF")
      (fields
        (field (name "BOM_Manufacturer Part") "GRM31B7U3A471JW31L")
        (field (name "BOM_Supplier Part") "C97936")
      )
      (libsource (lib "") (part "GRM31B7U3A471JW31L"))
    )
    (comp (ref "C121")
      (value "1nF")
      (fields
        (field (name "BOM_Manufacturer Part") "GRM31B7U3A471JW31L")
        (field (name "BOM_Supplier Part") "C97936")
      )
      (libsource (lib "") (part "GRM31B7U3A471JW31L"))
    )
    (comp (ref "C122")
      (value "1nF")
      (fields
        (field (name "BOM_Manufacturer Part") "GRM31B7U3A471JW31L")
        (field (name "BOM_Supplier Part") "C97936")
      )
      (libsource (lib "") (part "GRM31B7U3A471JW31L"))
    )
    (comp (ref "C123")
      (value "1nF")
      (fields
        (field (name "BOM_Manufacturer Part") "GRM31B7U3A471JW31L")
        (field (name "BOM_Supplier Part") "C97936")
      )
      (libsource (lib "") (part "GRM31B7U3A471JW31L"))
    )
    (comp (ref "C124")
      (value "1nF")
      (fields
        (field (name "BOM_Manufacturer Part") "GRM31B7U3A471JW31L")
        (field (name "BOM_Supplier Part") "C97936")
      )
      (libsource (lib "") (part "GRM31B7U3A471JW31L"))
    )
    (comp (ref "C125")
      (value "1nF")
      (fields
        (field (name "BOM_Manufacturer Part") "GRM31B7U3A471JW31L")
        (field (name "BOM_Supplier Part") "C97936")
      )
      (libsource (lib "") (part "GRM31B7U3A471JW31L"))
    )
    (comp (ref "C126")
      (value "1nF")
      (fields
        (field (name "BOM_Manufacturer Part") "GRM31B7U3A471JW31L")
        (field (name "BOM_Supplier Part") "C97936")
      )
      (libsource (lib "") (part "GRM31B7U3A471JW31L"))
    )
    (comp (ref "C127")
      (value "150nF")
      (fields
        (field (name "BOM_Manufacturer Part") "GRM31B7U3A471JW31L")
        (field (name "BOM_Supplier Part") "C97936")
      )
      (libsource (lib "") (part "GRM31B7U3A471JW31L_1"))
    )
    (comp (ref "C128")
      (value "150nF")
      (fields
        (field (name "BOM_Manufacturer Part") "GRM31B7U3A471JW31L")
        (field (name "BOM_Supplier Part") "C97936")
      )
      (libsource (lib "") (part "GRM31B7U3A471JW31L_1"))
    )
    (comp (ref "C129")
      (value "150nF")
      (fields
        (field (name "BOM_Manufacturer Part") "GRM31B7U3A471JW31L")
        (field (name "BOM_Supplier Part") "C97936")
      )
      (libsource (lib "") (part "GRM31B7U3A471JW31L_1"))
    )
    (comp (ref "C130")
      (value "150nF")
      (fields
        (field (name "BOM_Manufacturer Part") "GRM31B7U3A471JW31L")
        (field (name "BOM_Supplier Part") "C97936")
      )
      (libsource (lib "") (part "GRM31B7U3A471JW31L_1"))
    )
    (comp (ref "C131")
      (value "100nF")
      (fields
        (field (name "BOM_Manufacturer Part") "GRM31B7U3A471JW31L")
        (field (name "BOM_Supplier Part") "C97936")
      )
      (libsource (lib "") (part "GRM31B7U3A471JW31L"))
    )
    (comp (ref "C132")
      (value "100nF")
      (fields
        (field (name "BOM_Manufacturer Part") "GRM31B7U3A471JW31L")
        (field (name "BOM_Supplier Part") "C97936")
      )
      (libsource (lib "") (part "GRM31B7U3A471JW31L"))
    )
    (comp (ref "C133")
      (value "150nF")
      (fields
        (field (name "BOM_Manufacturer Part") "GRM31B7U3A471JW31L")
        (field (name "BOM_Supplier Part") "C97936")
      )
      (libsource (lib "") (part "GRM31B7U3A471JW31L_1"))
    )
    (comp (ref "C134")
      (value "1nF")
      (fields
        (field (name "BOM_Manufacturer Part") "GRM31B7U3A471JW31L")
        (field (name "BOM_Supplier Part") "C97936")
      )
      (libsource (lib "") (part "GRM31B7U3A471JW31L"))
    )
    (comp (ref "C135")
      (value "1nF")
      (fields
        (field (name "BOM_Manufacturer Part") "GRM31B7U3A471JW31L")
        (field (name "BOM_Supplier Part") "C97936")
      )
      (libsource (lib "") (part "GRM31B7U3A471JW31L"))
    )
    (comp (ref "D11")
      (value "1N5819")
      (fields (field (name "BOM_Manufacturer Part") "1N4007") (field (name "BOM_Supplier Part") "C106903"))
      (libsource (lib "") (part "1N4007"))
    )
    (comp (ref "D12")
      (value "1N5819")
      (fields (field (name "BOM_Manufacturer Part") "1N4007") (field (name "BOM_Supplier Part") "C106903"))
      (libsource (lib "") (part "1N4007"))
    )
    (comp (ref "K1")
      (value "HFD4/3-S1R")
      (fields (field (name "BOM_Supplier Part") "C143232"))
      (libsource (lib "") (part "HFD4/3-S1R"))
    )
    (comp (ref "K2")
      (value "HFD4/3-S1R")
      (fields (field (name "BOM_Supplier Part") "C143232"))
      (libsource (lib "") (part "HFD4/3-S1R"))
    )
    (comp (ref "K3")
      (value "HFD4/3-S1R")
      (fields (field (name "BOM_Supplier Part") "C143232"))
      (libsource (lib "") (part "HFD4/3-S1R"))
    )
    (comp (ref "K4")
      (value "HFD4/3-S1R")
      (fields (field (name "BOM_Supplier Part") "C143232"))
      (libsource (lib "") (part "HFD4/3-S1R"))
    )
    (comp (ref "K5")
      (value "HFD4/3-S1R")
      (fields (field (name "BOM_Supplier Part") "C143232"))
      (libsource (lib "") (part "HFD4/3-S1R"))
    )
    (comp (ref "K6")
      (value "HFD4/3-S1R")
      (fields (field (name "BOM_Supplier Part") "C143232"))
      (libsource (lib "") (part "HFD4/3-S1R"))
    )
    (comp (ref "Q1")
      (value "SS8550")
      (fields (field (name "BOM_Supplier Part") "C909745"))
      (libsource (lib "") (part "SS8550"))
    )
    (comp (ref "Q2")
      (value "SS8550")
      (fields (field (name "BOM_Supplier Part") "C909745"))
      (libsource (lib "") (part "SS8550"))
    )
    (comp (ref "Q3")
      (value "SS8550")
      (fields (field (name "BOM_Supplier Part") "C909745"))
      (libsource (lib "") (part "SS8550"))
    )
    (comp (ref "Q4")
      (value "SS8550")
      (fields (field (name "BOM_Supplier Part") "C909745"))
      (libsource (lib "") (part "SS8550"))
    )
    (comp (ref "Q5")
      (value "SS8550")
      (fields (field (name "BOM_Supplier Part") "C909745"))
      (libsource (lib "") (part "SS8550"))
    )
    (comp (ref "Q6")
      (value "SS8550")
      (fields (field (name "BOM_Supplier Part") "C909745"))
      (libsource (lib "") (part "SS8550"))
    )
    (comp (ref "R62") (value "150") (libsource (lib "") (part "R_0805_EU_1")))
    (comp (ref "R63") (value "3M") (libsource (lib "") (part "R_0805_EU_1")))
    (comp (ref "R64") (value "2M7") (libsource (lib "") (part "R_0805_EU_1")))
    (comp (ref "R65") (value "1M2") (libsource (lib "") (part "R_0805_EU_1")))
    (comp (ref "R66") (value "75K") (libsource (lib "") (part "R_0805_EU")))
    (comp (ref "R67") (value "360K") (libsource (lib "") (part "R_0805_EU")))
    (comp (ref "R68") (value "1M8") (libsource (lib "") (part "R_0805_EU")))
    (comp (ref "R69") (value "3K") (libsource (lib "") (part "R_0805_EU")))
    (comp (ref "R70") (value "3K") (libsource (lib "") (part "R_0805_EU")))
    (comp (ref "R71") (value "100") (libsource (lib "") (part "R_0805_EU")))
    (comp (ref "R72") (value "3K") (libsource (lib "") (part "R_0805_EU")))
    (comp (ref "R73") (value "3K") (libsource (lib "") (part "R_0805_EU")))
    (comp (ref "R74") (value "1M8") (libsource (lib "") (part "R_0805_EU")))
    (comp (ref "R75") (value "360K") (libsource (lib "") (part "R_0805_EU")))
    (comp (ref "R76") (value "75K") (libsource (lib "") (part "R_0805_EU")))
    (comp (ref "R77") (value "1M2") (libsource (lib "") (part "R_0805_EU_1")))
    (comp (ref "R78") (value "2M7") (libsource (lib "") (part "R_0805_EU_1")))
    (comp (ref "R79") (value "3M") (libsource (lib "") (part "R_0805_EU_1")))
    (comp (ref "R80") (value "150") (libsource (lib "") (part "R_0805_EU_1")))
    (comp (ref "R81") (value "200") (libsource (lib "") (part "R_0805_EU")))
    (comp (ref "R82") (value "1") (libsource (lib "") (part "R_0805_EU_2")))
    (comp (ref "RF1")
      (value "BNC")
      (fields
        (field (name "BOM_Manufacturer Part") "DOSIN-801-0080")
        (field (name "BOM_Supplier Part") "C521219")
      )
      (libsource (lib "") (part "DOSIN-801-0080"))
    )
    (comp (ref "RF2")
      (value "BNC")
      (fields
        (field (name "BOM_Manufacturer Part") "DOSIN-801-0080")
        (field (name "BOM_Supplier Part") "C521219")
      )
      (libsource (lib "") (part "DOSIN-801-0080"))
    )
    (comp (ref "U17")
      (value "RS8751XF")
      (fields (field (name "BOM_Supplier Part") "C236995"))
      (libsource (lib "") (part "RS8751XF"))
    )
    (comp (ref "U18")
      (value "KAQY214STLD")
      (fields (field (name "BOM_Supplier Part") "C113331"))
      (libsource (lib "") (part "KAQY214STLD"))
    )
    (comp (ref "U19")
      (value "KAQY214STLD")
      (fields (field (name "BOM_Supplier Part") "C113331"))
      (libsource (lib "") (part "KAQY214STLD"))
    )
    (comp (ref "U20")
      (value "RS8751XF")
      (fields (field (name "BOM_Supplier Part") "C236995"))
      (libsource (lib "") (part "RS8751XF"))
    )
    (comp (ref "U21") (value "TL432") (libsource (lib "") (part "TL431AIDBZTG4")))
    (comp (ref "C47")
      (value "1nF")
      (fields
        (field (name "BOM_Manufacturer Part") "GRM31B7U3A471JW31L")
        (field (name "BOM_Supplier Part") "C97936")
      )
      (libsource (lib "") (part "GRM31B7U3A471JW31L"))
    )
    (comp (ref "C48")
      (value "1nF")
      (fields
        (field (name "BOM_Manufacturer Part") "GRM31B7U3A471JW31L")
        (field (name "BOM_Supplier Part") "C97936")
      )
      (libsource (lib "") (part "GRM31B7U3A471JW31L"))
    )
    (comp (ref "C49")
      (value "1nF")
      (fields
        (field (name "BOM_Manufacturer Part") "GRM31B7U3A471JW31L")
        (field (name "BOM_Supplier Part") "C97936")
      )
      (libsource (lib "") (part "GRM31B7U3A471JW31L"))
    )
    (comp (ref "C50")
      (value "1nF")
      (fields
        (field (name "BOM_Manufacturer Part") "GRM31B7U3A471JW31L")
        (field (name "BOM_Supplier Part") "C97936")
      )
      (libsource (lib "") (part "GRM31B7U3A471JW31L"))
    )
    (comp (ref "C51")
      (value "1nF")
      (fields
        (field (name "BOM_Manufacturer Part") "GRM31B7U3A471JW31L")
        (field (name "BOM_Supplier Part") "C97936")
      )
      (libsource (lib "") (part "GRM31B7U3A471JW31L"))
    )
    (comp (ref "C52")
      (value "1nF")
      (fields
        (field (name "BOM_Manufacturer Part") "GRM31B7U3A471JW31L")
        (field (name "BOM_Supplier Part") "C97936")
      )
      (libsource (lib "") (part "GRM31B7U3A471JW31L"))
    )
    (comp (ref "C54")
      (value "1nF")
      (fields
        (field (name "BOM_Manufacturer Part") "GRM31B7U3A471JW31L")
        (field (name "BOM_Supplier Part") "C97936")
      )
      (libsource (lib "") (part "GRM31B7U3A471JW31L"))
    )
    (comp (ref "C60")
      (value "4u7F")
      (fields
        (field (name "BOM_Manufacturer Part") "GRM31B7U3A471JW31L")
        (field (name "BOM_Supplier Part") "C97936")
      )
      (libsource (lib "") (part "GRM31B7U3A471JW31L"))
    )
    (comp (ref "C61")
      (value "4u7F")
      (fields
        (field (name "BOM_Manufacturer Part") "GRM31B7U3A471JW31L")
        (field (name "BOM_Supplier Part") "C97936")
      )
      (libsource (lib "") (part "GRM31B7U3A471JW31L"))
    )
    (comp (ref "C62")
      (value "4u7F")
      (fields
        (field (name "BOM_Manufacturer Part") "GRM31B7U3A471JW31L")
        (field (name "BOM_Supplier Part") "C97936")
      )
      (libsource (lib "") (part "GRM31B7U3A471JW31L"))
    )
    (comp (ref "C63")
      (value "100nF")
      (fields
        (field (name "BOM_Manufacturer Part") "GRM31B7U3A471JW31L")
        (field (name "BOM_Supplier Part") "C97936")
      )
      (libsource (lib "") (part "GRM31B7U3A471JW31L"))
    )
    (comp (ref "C64")
      (value "100nF")
      (fields
        (field (name "BOM_Manufacturer Part") "GRM31B7U3A471JW31L")
        (field (name "BOM_Supplier Part") "C97936")
      )
      (libsource (lib "") (part "GRM31B7U3A471JW31L"))
    )
    (comp (ref "C65")
      (value "1nF")
      (fields
        (field (name "BOM_Manufacturer Part") "GRM31B7U3A471JW31L")
        (field (name "BOM_Supplier Part") "C97936")
      )
      (libsource (lib "") (part "GRM31B7U3A471JW31L"))
    )
    (comp (ref "C66")
      (value "1nF")
      (fields
        (field (name "BOM_Manufacturer Part") "GRM31B7U3A471JW31L")
        (field (name "BOM_Supplier Part") "C97936")
      )
      (libsource (lib "") (part "GRM31B7U3A471JW31L"))
    )
    (comp (ref "C67")
      (value "1nF")
      (fields
        (field (name "BOM_Manufacturer Part") "GRM31B7U3A471JW31L")
        (field (name "BOM_Supplier Part") "C97936")
      )
      (libsource (lib "") (part "GRM31B7U3A471JW31L"))
    )
    (comp (ref "C68")
      (value "1nF")
      (fields
        (field (name "BOM_Manufacturer Part") "GRM31B7U3A471JW31L")
        (field (name "BOM_Supplier Part") "C97936")
      )
      (libsource (lib "") (part "GRM31B7U3A471JW31L"))
    )
    (comp (ref "C69")
      (value "1nF")
      (fields
        (field (name "BOM_Manufacturer Part") "GRM31B7U3A471JW31L")
        (field (name "BOM_Supplier Part") "C97936")
      )
      (libsource (lib "") (part "GRM31B7U3A471JW31L"))
    )
    (comp (ref "C70")
      (value "1nF")
      (fields
        (field (name "BOM_Manufacturer Part") "GRM31B7U3A471JW31L")
        (field (name "BOM_Supplier Part") "C97936")
      )
      (libsource (lib "") (part "GRM31B7U3A471JW31L"))
    )
    (comp (ref "C71")
      (value "1nF")
      (fields
        (field (name "BOM_Manufacturer Part") "GRM31B7U3A471JW31L")
        (field (name "BOM_Supplier Part") "C97936")
      )
      (libsource (lib "") (part "GRM31B7U3A471JW31L"))
    )
    (comp (ref "C72")
      (value "1nF")
      (fields
        (field (name "BOM_Manufacturer Part") "GRM31B7U3A471JW31L")
        (field (name "BOM_Supplier Part") "C97936")
      )
      (libsource (lib "") (part "GRM31B7U3A471JW31L"))
    )
    (comp (ref "C73")
      (value "1nF")
      (fields
        (field (name "BOM_Manufacturer Part") "GRM31B7U3A471JW31L")
        (field (name "BOM_Supplier Part") "C97936")
      )
      (libsource (lib "") (part "GRM31B7U3A471JW31L"))
    )
    (comp (ref "C74")
      (value "1nF")
      (fields
        (field (name "BOM_Manufacturer Part") "GRM31B7U3A471JW31L")
        (field (name "BOM_Supplier Part") "C97936")
      )
      (libsource (lib "") (part "GRM31B7U3A471JW31L"))
    )
    (comp (ref "C75")
      (value "1nF")
      (fields
        (field (name "BOM_Manufacturer Part") "GRM31B7U3A471JW31L")
        (field (name "BOM_Supplier Part") "C97936")
      )
      (libsource (lib "") (part "GRM31B7U3A471JW31L"))
    )
    (comp (ref "C76")
      (value "1nF")
      (fields
        (field (name "BOM_Manufacturer Part") "GRM31B7U3A471JW31L")
        (field (name "BOM_Supplier Part") "C97936")
      )
      (libsource (lib "") (part "GRM31B7U3A471JW31L"))
    )
    (comp (ref "C77")
      (value "1nF")
      (fields
        (field (name "BOM_Manufacturer Part") "GRM31B7U3A471JW31L")
        (field (name "BOM_Supplier Part") "C97936")
      )
      (libsource (lib "") (part "GRM31B7U3A471JW31L"))
    )
    (comp (ref "C78")
      (value "1nF")
      (fields
        (field (name "BOM_Manufacturer Part") "GRM31B7U3A471JW31L")
        (field (name "BOM_Supplier Part") "C97936")
      )
      (libsource (lib "") (part "GRM31B7U3A471JW31L"))
    )
    (comp (ref "C79")
      (value "1nF")
      (fields
        (field (name "BOM_Manufacturer Part") "GRM31B7U3A471JW31L")
        (field (name "BOM_Supplier Part") "C97936")
      )
      (libsource (lib "") (part "GRM31B7U3A471JW31L"))
    )
    (comp (ref "C80")
      (value "1nF")
      (fields
        (field (name "BOM_Manufacturer Part") "GRM31B7U3A471JW31L")
        (field (name "BOM_Supplier Part") "C97936")
      )
      (libsource (lib "") (part "GRM31B7U3A471JW31L"))
    )
    (comp (ref "C81")
      (value "1nF")
      (fields
        (field (name "BOM_Manufacturer Part") "GRM31B7U3A471JW31L")
        (field (name "BOM_Supplier Part") "C97936")
      )
      (libsource (lib "") (part "GRM31B7U3A471JW31L"))
    )
    (comp (ref "C82")
      (value "1nF")
      (fields
        (field (name "BOM_Manufacturer Part") "GRM31B7U3A471JW31L")
        (field (name "BOM_Supplier Part") "C97936")
      )
      (libsource (lib "") (part "GRM31B7U3A471JW31L"))
    )
    (comp (ref "C83")
      (value "1nF")
      (fields
        (field (name "BOM_Manufacturer Part") "GRM31B7U3A471JW31L")
        (field (name "BOM_Supplier Part") "C97936")
      )
      (libsource (lib "") (part "GRM31B7U3A471JW31L"))
    )
    (comp (ref "C84")
      (value "1nF")
      (fields
        (field (name "BOM_Manufacturer Part") "GRM31B7U3A471JW31L")
        (field (name "BOM_Supplier Part") "C97936")
      )
      (libsource (lib "") (part "GRM31B7U3A471JW31L"))
    )
    (comp (ref "C85")
      (value "1nF")
      (fields
        (field (name "BOM_Manufacturer Part") "GRM31B7U3A471JW31L")
        (field (name "BOM_Supplier Part") "C97936")
      )
      (libsource (lib "") (part "GRM31B7U3A471JW31L"))
    )
    (comp (ref "C86")
      (value "1nF")
      (fields
        (field (name "BOM_Manufacturer Part") "GRM31B7U3A471JW31L")
        (field (name "BOM_Supplier Part") "C97936")
      )
      (libsource (lib "") (part "GRM31B7U3A471JW31L"))
    )
    (comp (ref "C87")
      (value "4u7F")
      (fields
        (field (name "BOM_Manufacturer Part") "GRM31B7U3A471JW31L")
        (field (name "BOM_Supplier Part") "C97936")
      )
      (libsource (lib "") (part "GRM31B7U3A471JW31L"))
    )
    (comp (ref "C88")
      (value "4u7F")
      (fields
        (field (name "BOM_Manufacturer Part") "GRM31B7U3A471JW31L")
        (field (name "BOM_Supplier Part") "C97936")
      )
      (libsource (lib "") (part "GRM31B7U3A471JW31L"))
    )
    (comp (ref "C89")
      (value "100nF")
      (fields
        (field (name "BOM_Manufacturer Part") "GRM31B7U3A471JW31L")
        (field (name "BOM_Supplier Part") "C97936")
      )
      (libsource (lib "") (part "GRM31B7U3A471JW31L"))
    )
    (comp (ref "C90")
      (value "4u7F")
      (fields
        (field (name "BOM_Manufacturer Part") "GRM31B7U3A471JW31L")
        (field (name "BOM_Supplier Part") "C97936")
      )
      (libsource (lib "") (part "GRM31B7U3A471JW31L"))
    )
    (comp (ref "C91")
      (value "4u7F")
      (fields
        (field (name "BOM_Manufacturer Part") "GRM31B7U3A471JW31L")
        (field (name "BOM_Supplier Part") "C97936")
      )
      (libsource (lib "") (part "GRM31B7U3A471JW31L"))
    )
    (comp (ref "C92")
      (value "4u7F")
      (fields
        (field (name "BOM_Manufacturer Part") "GRM31B7U3A471JW31L")
        (field (name "BOM_Supplier Part") "C97936")
      )
      (libsource (lib "") (part "GRM31B7U3A471JW31L"))
    )
    (comp (ref "C93")
      (value "4u7F")
      (fields
        (field (name "BOM_Manufacturer Part") "GRM31B7U3A471JW31L")
        (field (name "BOM_Supplier Part") "C97936")
      )
      (libsource (lib "") (part "GRM31B7U3A471JW31L"))
    )
    (comp (ref "C94")
      (value "4u7F")
      (fields
        (field (name "BOM_Manufacturer Part") "GRM31B7U3A471JW31L")
        (field (name "BOM_Supplier Part") "C97936")
      )
      (libsource (lib "") (part "GRM31B7U3A471JW31L"))
    )
    (comp (ref "C95")
      (value "4u7F")
      (fields
        (field (name "BOM_Manufacturer Part") "GRM31B7U3A471JW31L")
        (field (name "BOM_Supplier Part") "C97936")
      )
      (libsource (lib "") (part "GRM31B7U3A471JW31L"))
    )
    (comp (ref "C96")
      (value "4u7F")
      (fields
        (field (name "BOM_Manufacturer Part") "GRM31B7U3A471JW31L")
        (field (name "BOM_Supplier Part") "C97936")
      )
      (libsource (lib "") (part "GRM31B7U3A471JW31L"))
    )
    (comp (ref "C97")
      (value "4u7F")
      (fields
        (field (name "BOM_Manufacturer Part") "GRM31B7U3A471JW31L")
        (field (name "BOM_Supplier Part") "C97936")
      )
      (libsource (lib "") (part "GRM31B7U3A471JW31L"))
    )
    (comp (ref "C98")
      (value "4u7F")
      (fields
        (field (name "BOM_Manufacturer Part") "GRM31B7U3A471JW31L")
        (field (name "BOM_Supplier Part") "C97936")
      )
      (libsource (lib "") (part "GRM31B7U3A471JW31L"))
    )
    (comp (ref "CON1") (value "BATTERY") (libsource (lib "") (part "XH2.54-2P")))
    (comp (ref "D4")
      (value "1N5819")
      (fields (field (name "BOM_Manufacturer Part") "1N4007") (field (name "BOM_Supplier Part") "C106903"))
      (libsource (lib "") (part "1N4007"))
    )
    (comp (ref "D5")
      (value "1N5819")
      (fields (field (name "BOM_Manufacturer Part") "1N4007") (field (name "BOM_Supplier Part") "C106903"))
      (libsource (lib "") (part "1N4007"))
    )
    (comp (ref "D6")
      (value "SS34")
      (fields (field (name "BOM_Supplier Part") "C13763"))
      (libsource (lib "") (part "SS34"))
    )
    (comp (ref "D7")
      (value "SS34")
      (fields (field (name "BOM_Supplier Part") "C13763"))
      (libsource (lib "") (part "SS34_2"))
    )
    (comp (ref "D8")
      (value "SS34")
      (fields (field (name "BOM_Supplier Part") "C13763"))
      (libsource (lib "") (part "SS34_1"))
    )
    (comp (ref "D9")
      (value "BZT52C8V2")
      (fields (field (name "BOM_Supplier Part") "C2122"))
      (libsource (lib "") (part "BZT52C8V2"))
    )
    (comp (ref "D10")
      (value "SS34")
      (fields (field (name "BOM_Supplier Part") "C13763"))
      (libsource (lib "") (part "SS34"))
    )
    (comp (ref "L5")
      (value "10uH")
      (fields
        (field (name "BOM_Manufacturer Part") "SMDRI74-101MT")
        (field (name "BOM_Supplier Part") "C36970")
      )
      (libsource (lib "") (part "SMDRI74-101MT_1"))
    )
    (comp (ref "L6")
      (value "10uH")
      (fields
        (field (name "BOM_Manufacturer Part") "SMDRI74-101MT")
        (field (name "BOM_Supplier Part") "C36970")
      )
      (libsource (lib "") (part "SMDRI74-101MT"))
    )
    (comp (ref "LED1")
      (value "3mm_G")
      (fields
        (field (name "BOM_Manufacturer Part") "204-10SYGD/S530-E3")
        (field (name "BOM_Supplier Part") "C85161")
      )
      (libsource (lib "") (part "LED-TH-3mm_G"))
    )
    (comp (ref "LED2")
      (value "3mm_R")
      (fields
        (field (name "BOM_Manufacturer Part") "204-10SDRD/S530-A3-L")
        (field (name "BOM_Supplier Part") "C84774")
      )
      (libsource (lib "") (part "LED-TH-3mm_R"))
    )
    (comp (ref "R46") (value "1K") (libsource (lib "") (part "R_0805_EU")))
    (comp (ref "R47") (value "1K") (libsource (lib "") (part "R_0805_EU")))
    (comp (ref "R48") (value "10K") (libsource (lib "") (part "R_0805_EU")))
    (comp (ref "R49") (value "510") (libsource (lib "") (part "R_0805_EU")))
    (comp (ref "R50") (value "4K7") (libsource (lib "") (part "R_0805_EU")))
    (comp (ref "R51") (value "10K") (libsource (lib "") (part "R_0805_EU")))
    (comp (ref "R52") (value "470K") (libsource (lib "") (part "R_0805_EU")))
    (comp (ref "R53") (value "10K") (libsource (lib "") (part "R_0805_EU")))
    (comp (ref "R54") (value "4K7") (libsource (lib "") (part "R_0805_EU")))
    (comp (ref "R55") (value "3K") (libsource (lib "") (part "R_0805_EU")))
    (comp (ref "R56") (value "12K") (libsource (lib "") (part "R_0805_EU")))
    (comp (ref "R57") (value "1K") (libsource (lib "") (part "R_0805_EU")))
    (comp (ref "R58") (value "10K") (libsource (lib "") (part "R_0805_EU")))
    (comp (ref "R59") (value "1K") (libsource (lib "") (part "R_0805_EU")))
    (comp (ref "R60") (value "1") (libsource (lib "") (part "R_0805_EU")))
    (comp (ref "R61") (value "1") (libsource (lib "") (part "R_0805_EU")))
    (comp (ref "S1") (value "POWER ON") (libsource (lib "") (part "SWITCH-SPDTPTH2")))
    (comp (ref "U6")
      (value "SPX29302T5")
      (fields
        (field (name "BOM_Manufacturer Part") "SPX29302T5-L/TR")
        (field (name "BOM_Supplier Part") "C9013")
      )
      (libsource (lib "") (part "SPX29302T5-L/TR"))
    )
    (comp (ref "U9")
      (value "TP4056")
      (fields (field (name "BOM_Supplier Part") "C16581"))
      (libsource (lib "") (part "TP4056"))
    )
    (comp (ref "U10")
      (value "TP4056")
      (fields (field (name "BOM_Supplier Part") "C16581"))
      (libsource (lib "") (part "TP4056"))
    )
    (comp (ref "U11")
      (value "AMS1117-1.2_C475600")
      (fields
        (field (name "BOM_Manufacturer Part") "AMS1117-1.2")
        (field (name "BOM_Supplier Part") "C475600")
      )
      (libsource (lib "") (part "AMS1117-1.2_C475600"))
    )
    (comp (ref "U12")
      (value "LM6206N3 (65Z5)")
      (fields
        (field (name "BOM_Manufacturer Part") "LM6206N3")
        (field (name "BOM_Supplier Part") "LM6206N3 (662K)")
      )
      (libsource (lib "") (part "LM6206N3"))
    )
    (comp (ref "U13") (value "TL431") (libsource (lib "") (part "TL431AIDBZTG4")))
    (comp (ref "U14")
      (value "LM6206N3 (65T5)")
      (fields
        (field (name "BOM_Manufacturer Part") "LM6206N3")
        (field (name "BOM_Supplier Part") "LM6206N3 (662K)")
      )
      (libsource (lib "") (part "LM6206N3"))
    )
    (comp (ref "U15")
      (value "TPS61041")
      (fields
        (field (name "BOM_Manufacturer Part") "TPS61040DBVR")
        (field (name "BOM_Supplier Part") "C7722")
      )
      (libsource (lib "") (part "TPS61040DBVR"))
    )
    (comp (ref "U16")
      (value "PT4103B23F")
      (fields (field (name "BOM_Supplier Part") "C19861"))
      (libsource (lib "") (part "PT4103B23F"))
    )
    (comp (ref "ZD1")
      (value "BZT52C5V6")
      (fields (field (name "BOM_Supplier Part") "C2119"))
      (libsource (lib "") (part "BZT52C5V6"))
    )
  )
  (nets
    (net (code "1") (name "-6V3") (class "Default")
      (node (ref "C93") (pin "1") (pinfunction "1_1") (pintype "input"))
      (node (ref "C94") (pin "1") (pinfunction "1_1") (pintype "input"))
      (node (ref "D9") (pin "1") (pinfunction "K_1") (pintype "unspecified"))
      (node (ref "P3") (pin "42") (pinfunction "42_42") (pintype "unspecified"))
      (node (ref "R58") (pin "2") (pinfunction "2_2") (pintype "unspecified"))
    )
    (net (code "2") (name "1KHZ_CALIB_SIG") (class "Default")
      (node (ref "R21") (pin "1") (pinfunction "1_1") (pintype "unspecified"))
    )
    (net (code "3") (name "1V2") (class "Default")
      (node (ref "C1") (pin "1") (pinfunction "1_1") (pintype "input"))
      (node (ref "C11") (pin "1") (pinfunction "1_1") (pintype "input"))
      (node (ref "C33") (pin "1") (pinfunction "1_1") (pintype "input"))
      (node (ref "C34") (pin "1") (pinfunction "1_1") (pintype "input"))
      (node (ref "C35") (pin "1") (pinfunction "1_1") (pintype "input"))
      (node (ref "C4") (pin "1") (pinfunction "1_1") (pintype "input"))
      (node (ref "C47") (pin "1") (pinfunction "1_1") (pintype "input"))
      (node (ref "C48") (pin "1") (pinfunction "1_1") (pintype "input"))
      (node (ref "C49") (pin "1") (pinfunction "1_1") (pintype "input"))
      (node (ref "C50") (pin "1") (pinfunction "1_1") (pintype "input"))
      (node (ref "C51") (pin "1") (pinfunction "1_1") (pintype "input"))
      (node (ref "C52") (pin "1") (pinfunction "1_1") (pintype "input"))
      (node (ref "C73") (pin "1") (pinfunction "1_1") (pintype "input"))
      (node (ref "C74") (pin "1") (pinfunction "1_1") (pintype "input"))
      (node (ref "C75") (pin "1") (pinfunction "1_1") (pintype "input"))
      (node (ref "C8") (pin "1") (pinfunction "1_1") (pintype "input"))
      (node (ref "C9") (pin "1") (pinfunction "1_1") (pintype "input"))
      (node (ref "L1") (pin "1") (pinfunction "1_1") (pintype "unspecified"))
      (node (ref "L4") (pin "1") (pinfunction "1_1") (pintype "unspecified"))
      (node (ref "U1") (pin "22") (pinfunction "VDD-CORE_22") (pintype "unspecified"))
      (node (ref "U1") (pin "35") (pinfunction "VDD-CORE_35") (pintype "unspecified"))
      (node (ref "U1") (pin "71") (pinfunction "VDD-CORE_71") (pintype "unspecified"))
      (node (ref "U11") (pin "2") (pinfunction "VOUT_2") (pintype "unspecified"))
      (node (ref "U11") (pin "4") (pinfunction "VOUT_4") (pintype "unspecified"))
      (node (ref "U3") (pin "102") (pinfunction "VCCINT_102") (pintype "input"))
      (node (ref "U3") (pin "116") (pinfunction "VCCINT_116") (pintype "input"))
      (node (ref "U3") (pin "134") (pinfunction "VCCINT_134") (pintype "input"))
      (node (ref "U3") (pin "29") (pinfunction "VCCINT_29") (pintype "input"))
      (node (ref "U3") (pin "45") (pinfunction "VCCINT_45") (pintype "input"))
      (node (ref "U3") (pin "5") (pinfunction "VCCINT_5") (pintype "input"))
      (node (ref "U3") (pin "61") (pinfunction "VCCINT_61") (pintype "input"))
      (node (ref "U3") (pin "78") (pinfunction "VCCINT_78") (pintype "input"))
    )
    (net (code "4") (name "2V5") (class "Default")
      (node (ref "C112") (pin "2") (pinfunction "2_2") (pintype "input"))
      (node (ref "C113") (pin "2") (pinfunction "2_2") (pintype "input"))
      (node (ref "C119") (pin "2") (pinfunction "2_2") (pintype "input"))
      (node (ref "C120") (pin "2") (pinfunction "2_2") (pintype "input"))
      (node (ref "C42") (pin "1") (pinfunction "1_1") (pintype "input"))
      (node (ref "C43") (pin "1") (pinfunction "1_1") (pintype "input"))
      (node (ref "C44") (pin "1") (pinfunction "1_1") (pintype "input"))
      (node (ref "C45") (pin "1") (pinfunction "1_1") (pintype "input"))
      (node (ref "C5") (pin "1") (pinfunction "1_1") (pintype "input"))
      (node (ref "C6") (pin "2") (pinfunction "2_2") (pintype "input"))
      (node (ref "C80") (pin "1") (pinfunction "1_1") (pintype "input"))
      (node (ref "C83") (pin "1") (pinfunction "1_1") (pintype "input"))
      (node (ref "C84") (pin "1") (pinfunction "1_1") (pintype "input"))
      (node (ref "C85") (pin "1") (pinfunction "1_1") (pintype "input"))
      (node (ref "R10") (pin "1") (pinfunction "1_1") (pintype "unspecified"))
      (node (ref "R28") (pin "2") (pinfunction "2_2") (pintype "unspecified"))
      (node (ref "R9") (pin "1") (pinfunction "1_1") (pintype "unspecified"))
      (node (ref "U1") (pin "30") (pinfunction "VCC-DRAM_30") (pintype "unspecified"))
      (node (ref "U1") (pin "31") (pinfunction "VCC-DRAM_31") (pintype "unspecified"))
      (node (ref "U1") (pin "32") (pinfunction "VCC-DRAM_32") (pintype "unspecified"))
      (node (ref "U1") (pin "34") (pinfunction "VCC-DRAM_34") (pintype "unspecified"))
      (node (ref "U1") (pin "36") (pinfunction "VCC-DRAM_36") (pintype "unspecified"))
      (node (ref "U14") (pin "2") (pinfunction "Vout_2") (pintype "output"))
      (node (ref "U17") (pin "5") (pinfunction "+V_5") (pintype "passive"))
      (node (ref "U20") (pin "5") (pinfunction "+V_5") (pintype "passive"))
      (node (ref "U3") (pin "107") (pinfunction "VCCA2_107") (pintype "input"))
      (node (ref "U3") (pin "35") (pinfunction "VCCA1_35") (pintype "input"))
      (node (ref "U3") (pin "96") (pinfunction "MSEL1_96") (pintype "input"))
    )
    (net (code "5") (name "3V") (class "Default")
      (node (ref "C53") (pin "1") (pinfunction "1_1") (pintype "input"))
      (node (ref "C54") (pin "1") (pinfunction "1_1") (pintype "input"))
      (node (ref "U1") (pin "80") (pinfunction "AVCC_80") (pintype "unspecified"))
      (node (ref "U12") (pin "2") (pinfunction "Vout_2") (pintype "output"))
    )
    (net (code "6") (name "3V3") (class "Default")
      (node (ref "C10") (pin "1") (pinfunction "1_1") (pintype "input"))
      (node (ref "C12") (pin "1") (pinfunction "1_1") (pintype "input"))
      (node (ref "C14") (pin "1") (pinfunction "1_1") (pintype "input"))
      (node (ref "C15") (pin "1") (pinfunction "1_1") (pintype "input"))
      (node (ref "C16") (pin "1") (pinfunction "1_1") (pintype "input"))
      (node (ref "C17") (pin "1") (pinfunction "1_1") (pintype "input"))
      (node (ref "C18") (pin "1") (pinfunction "1_1") (pintype "input"))
      (node (ref "C19") (pin "1") (pinfunction "1_1") (pintype "input"))
      (node (ref "C20") (pin "1") (pinfunction "1_1") (pintype "input"))
      (node (ref "C21") (pin "1") (pinfunction "1_1") (pintype "input"))
      (node (ref "C22") (pin "1") (pinfunction "1_1") (pintype "input"))
      (node (ref "C36") (pin "1") (pinfunction "1_1") (pintype "input"))
      (node (ref "C37") (pin "1") (pinfunction "1_1") (pintype "input"))
      (node (ref "C38") (pin "1") (pinfunction "1_1") (pintype "input"))
      (node (ref "C39") (pin "1") (pinfunction "1_1") (pintype "input"))
      (node (ref "C40") (pin "1") (pinfunction "1_1") (pintype "input"))
      (node (ref "C41") (pin "1") (pinfunction "1_1") (pintype "input"))
      (node (ref "C58") (pin "1") (pinfunction "1_1") (pintype "input"))
      (node (ref "C7") (pin "1") (pinfunction "1_1") (pintype "input"))
      (node (ref "C76") (pin "1") (pinfunction "1_1") (pintype "input"))
      (node (ref "C77") (pin "1") (pinfunction "1_1") (pintype "input"))
      (node (ref "C78") (pin "1") (pinfunction "1_1") (pintype "input"))
      (node (ref "C79") (pin "1") (pinfunction "1_1") (pintype "input"))
      (node (ref "C81") (pin "1") (pinfunction "1_1") (pintype "input"))
      (node (ref "C82") (pin "1") (pinfunction "1_1") (pintype "input"))
      (node (ref "C86") (pin "1") (pinfunction "1_1") (pintype "input"))
      (node (ref "D1") (pin "2") (pinfunction "2_2") (pintype "unspecified"))
      (node (ref "D12") (pin "1") (pinfunction "1_1") (pintype "unspecified"))
      (node (ref "D2") (pin "2") (pinfunction "2_2") (pintype "unspecified"))
      (node (ref "D3") (pin "2") (pinfunction "2_2") (pintype "unspecified"))
      (node (ref "L5") (pin "1") (pinfunction "1_1") (pintype "unspecified"))
      (node (ref "P1") (pin "2") (pinfunction "2_2") (pintype "unspecified"))
      (node (ref "P2") (pin "4") (pinfunction "VDD_4") (pintype "unspecified"))
      (node (ref "P3") (pin "39") (pinfunction "39_39") (pintype "unspecified"))
      (node (ref "P3") (pin "44") (pinfunction "44_44") (pintype "unspecified"))
      (node (ref "P3") (pin "7") (pinfunction "7_7") (pintype "unspecified"))
      (node (ref "Q1") (pin "2") (pinfunction "E_2") (pintype "input"))
      (node (ref "Q2") (pin "2") (pinfunction "E_2") (pintype "input"))
      (node (ref "Q3") (pin "2") (pinfunction "E_2") (pintype "input"))
      (node (ref "Q4") (pin "2") (pinfunction "E_2") (pintype "input"))
      (node (ref "Q5") (pin "2") (pinfunction "E_2") (pintype "input"))
      (node (ref "Q6") (pin "2") (pinfunction "E_2") (pintype "input"))
      (node (ref "R11") (pin "1") (pinfunction "1_1") (pintype "unspecified"))
      (node (ref "R12") (pin "1") (pinfunction "1_1") (pintype "unspecified"))
      (node (ref "R30") (pin "2") (pinfunction "2_2") (pintype "unspecified"))
      (node (ref "R34") (pin "2") (pinfunction "2_2") (pintype "unspecified"))
      (node (ref "R35") (pin "2") (pinfunction "2_2") (pintype "unspecified"))
      (node (ref "R36") (pin "2") (pinfunction "2_2") (pintype "unspecified"))
      (node (ref "R37") (pin "2") (pinfunction "2_2") (pintype "unspecified"))
      (node (ref "R38") (pin "2") (pinfunction "2_2") (pintype "unspecified"))
      (node (ref "R39") (pin "2") (pinfunction "2_2") (pintype "unspecified"))
      (node (ref "R40") (pin "2") (pinfunction "2_2") (pintype "unspecified"))
      (node (ref "R41") (pin "2") (pinfunction "2_2") (pintype "unspecified"))
      (node (ref "R42") (pin "2") (pinfunction "2_2") (pintype "unspecified"))
      (node (ref "R43") (pin "2") (pinfunction "2_2") (pintype "unspecified"))
      (node (ref "R48") (pin "2") (pinfunction "2_2") (pintype "unspecified"))
      (node (ref "R5") (pin "1") (pinfunction "1_1") (pintype "unspecified"))
      (node (ref "R54") (pin "2") (pinfunction "2_2") (pintype "unspecified"))
      (node (ref "R8") (pin "1") (pinfunction "1_1") (pintype "unspecified"))
      (node (ref "R81") (pin "1") (pinfunction "1_1") (pintype "unspecified"))
      (node (ref "U1") (pin "20") (pinfunction "VCC-IO_20") (pintype "unspecified"))
      (node (ref "U1") (pin "5") (pinfunction "VCC-IO_5") (pintype "unspecified"))
      (node (ref "U1") (pin "50") (pinfunction "VCC-IO_50") (pintype "unspecified"))
      (node (ref "U1") (pin "67") (pinfunction "UVCC_67") (pintype "unspecified"))
      (node (ref "U11") (pin "3") (pinfunction "VIN_3") (pintype "unspecified"))
      (node (ref "U12") (pin "3") (pinfunction "Vin_3") (pintype "unspecified"))
      (node (ref "U14") (pin "3") (pinfunction "Vin_3") (pintype "unspecified"))
      (node (ref "U15") (pin "4") (pinfunction "EN_4") (pintype "unspecified"))
      (node (ref "U15") (pin "5") (pinfunction "VIN_5") (pintype "unspecified"))
      (node (ref "U3") (pin "117") (pinfunction "VCCIO7_117") (pintype "input"))
      (node (ref "U3") (pin "122") (pinfunction "VCCIO7_122") (pintype "input"))
      (node (ref "U3") (pin "130") (pinfunction "VCCIO8_130") (pintype "input"))
      (node (ref "U3") (pin "139") (pinfunction "VCCIO8_139") (pintype "input"))
      (node (ref "U3") (pin "17") (pinfunction "VCCIO1_17") (pintype "input"))
      (node (ref "U3") (pin "26") (pinfunction "VCCIO2_26") (pintype "input"))
      (node (ref "U3") (pin "40") (pinfunction "VCCIO3_40") (pintype "input"))
      (node (ref "U3") (pin "47") (pinfunction "VCCIO3_47") (pintype "input"))
      (node (ref "U3") (pin "56") (pinfunction "VCCIO4_56") (pintype "input"))
      (node (ref "U3") (pin "62") (pinfunction "VCCIO4_62") (pintype "input"))
      (node (ref "U3") (pin "81") (pinfunction "VCCIO5_81") (pintype "input"))
      (node (ref "U3") (pin "93") (pinfunction "VCCIO6_93") (pintype "input"))
      (node (ref "U6") (pin "4") (pinfunction "out_4") (pintype "unspecified"))
      (node (ref "U7") (pin "13") (pinfunction "VD_13") (pintype "passive"))
      (node (ref "U7") (pin "15") (pinfunction "VDD_15") (pintype "passive"))
      (node (ref "U7") (pin "28") (pinfunction "VDD_28") (pintype "passive"))
      (node (ref "U7") (pin "30") (pinfunction "VD_30") (pintype "passive"))
      (node (ref "U7") (pin "31") (pinfunction "VD_31") (pintype "passive"))
      (node (ref "U7") (pin "33") (pinfunction "VDD_33") (pintype "passive"))
      (node (ref "U7") (pin "46") (pinfunction "VDD_46") (pintype "passive"))
      (node (ref "U7") (pin "48") (pinfunction "VD_48") (pintype "passive"))
      (node (ref "U7") (pin "8") (pinfunction "S1_8") (pintype "unspecified"))
      (node (ref "U7") (pin "9") (pinfunction "S2_9") (pintype "unspecified"))
      (node (ref "U8") (pin "13") (pinfunction "VD_13") (pintype "passive"))
      (node (ref "U8") (pin "15") (pinfunction "VDD_15") (pintype "passive"))
      (node (ref "U8") (pin "28") (pinfunction "VDD_28") (pintype "passive"))
      (node (ref "U8") (pin "30") (pinfunction "VD_30") (pintype "passive"))
      (node (ref "U8") (pin "31") (pinfunction "VD_31") (pintype "passive"))
      (node (ref "U8") (pin "33") (pinfunction "VDD_33") (pintype "passive"))
      (node (ref "U8") (pin "46") (pinfunction "VDD_46") (pintype "passive"))
      (node (ref "U8") (pin "48") (pinfunction "VD_48") (pintype "passive"))
      (node (ref "U8") (pin "8") (pinfunction "S1_8") (pintype "unspecified"))
      (node (ref "U8") (pin "9") (pinfunction "S2_9") (pintype "unspecified"))
      (node (ref "X2") (pin "1") (pinfunction "E/D_1") (pintype "unspecified"))
      (node (ref "X2") (pin "4") (pinfunction "VDD_4") (pintype "unspecified"))
    )
    (net (code "7") (name "10V3") (class "Default")
      (node (ref "C90") (pin "1") (pinfunction "1_1") (pintype "input"))
      (node (ref "C91") (pin "1") (pinfunction "1_1") (pintype "input"))
      (node (ref "P3") (pin "43") (pinfunction "43_43") (pintype "unspecified"))
      (node (ref "R44") (pin "2") (pinfunction "2_2") (pintype "unspecified"))
      (node (ref "ZD1") (pin "2") (pinfunction "A_2") (pintype "unspecified"))
    )
    (net (code "8") (name "15V8") (class "Default")
      (node (ref "C87") (pin "1") (pinfunction "1_1") (pintype "input"))
      (node (ref "C88") (pin "1") (pinfunction "1_1") (pintype "input"))
      (node (ref "D6") (pin "2") (pinfunction "K_2") (pintype "unspecified"))
      (node (ref "P3") (pin "41") (pinfunction "41_41") (pintype "unspecified"))
      (node (ref "R56") (pin "2") (pinfunction "2_2") (pintype "unspecified"))
      (node (ref "ZD1") (pin "1") (pinfunction "K_1") (pintype "unspecified"))
    )
    (net (code "9") (name "ADC1_D0A") (class "Default")
      (node (ref "U3") (pin "66") (pinfunction "(DQ1B),RUP2,IO_66") (pintype "input"))
      (node (ref "U8") (pin "37") (pinfunction "D0A_37") (pintype "unspecified"))
    )
    (net (code "10") (name "ADC1_D0B") (class "Default")
      (node (ref "U3") (pin "67") (pinfunction "(DQ1B),RDN2,IO_67") (pintype "input"))
      (node (ref "U8") (pin "24") (pinfunction "D0B_24") (pintype "unspecified"))
    )
    (net (code "11") (name "ADC1_D1A") (class "Default")
      (node (ref "U3") (pin "65") (pinfunction "VREFB4N0,IO_65") (pintype "input"))
      (node (ref "U8") (pin "38") (pinfunction "D1A_38") (pintype "unspecified"))
    )
    (net (code "12") (name "ADC1_D1B") (class "Default")
      (node (ref "U3") (pin "68") (pinfunction "(DQS0B/CQ1B,DPCLK3),DIFFIO_B20n,IO_68") (pintype "input"))
      (node (ref "U8") (pin "23") (pinfunction "D1B_23") (pintype "unspecified"))
    )
    (net (code "13") (name "ADC1_D2A") (class "Default")
      (node (ref "U3") (pin "64") (pinfunction "IO_64") (pintype "input"))
      (node (ref "U8") (pin "39") (pinfunction "D2A_39") (pintype "unspecified"))
    )
    (net (code "14") (name "ADC1_D2B") (class "Default")
      (node (ref "U3") (pin "69") (pinfunction "IO_69") (pintype "input"))
      (node (ref "U8") (pin "22") (pinfunction "D2B_22") (pintype "unspecified"))
    )
    (net (code "15") (name "ADC1_D3A") (class "Default")
      (node (ref "U3") (pin "60") (pinfunction "(DQ1B),DIFFIO_B16n,IO_60") (pintype "input"))
      (node (ref "U8") (pin "40") (pinfunction "D3A_40") (pintype "unspecified"))
    )
    (net (code "16") (name "ADC1_D3B") (class "Default")
      (node (ref "U3") (pin "70") (pinfunction "DIFFIO_B21p,IO_70") (pintype "input"))
      (node (ref "U8") (pin "21") (pinfunction "D3B_21") (pintype "unspecified"))
    )
    (net (code "17") (name "ADC1_D4A") (class "Default")
      (node (ref "U3") (pin "59") (pinfunction "(DQ1B),DIFFIO_B16p,IO_59") (pintype "input"))
      (node (ref "U8") (pin "41") (pinfunction "D4A_41") (pintype "unspecified"))
    )
    (net (code "18") (name "ADC1_D4B") (class "Default")
      (node (ref "U3") (pin "71") (pinfunction "DIFFIO_B21n,IO_71") (pintype "input"))
      (node (ref "U8") (pin "20") (pinfunction "D4B_20") (pintype "unspecified"))
    )
    (net (code "19") (name "ADC1_D5A") (class "Default")
      (node (ref "U3") (pin "58") (pinfunction "(DQ1B),DIFFIO_B15p,IO_58") (pintype "input"))
      (node (ref "U8") (pin "42") (pinfunction "D5A_42") (pintype "unspecified"))
    )
    (net (code "20") (name "ADC1_D5B") (class "Default")
      (node (ref "U3") (pin "72") (pinfunction "DIFFIO_B22p,IO_72") (pintype "input"))
      (node (ref "U8") (pin "19") (pinfunction "D5B_19") (pintype "unspecified"))
    )
    (net (code "21") (name "ADC1_D6A") (class "Default")
      (node (ref "U3") (pin "55") (pinfunction "DIFFIO_B12n,IO_55") (pintype "input"))
      (node (ref "U8") (pin "43") (pinfunction "D6A_43") (pintype "unspecified"))
    )
    (net (code "22") (name "ADC1_D6B") (class "Default")
      (node (ref "U3") (pin "73") (pinfunction "IO_73") (pintype "input"))
      (node (ref "U8") (pin "18") (pinfunction "D6B_18") (pintype "unspecified"))
    )
    (net (code "23") (name "ADC1_D7A") (class "Default")
      (node (ref "U3") (pin "54") (pinfunction "DIFFIO_B12p,IO_54") (pintype "input"))
      (node (ref "U8") (pin "44") (pinfunction "D7A_(MSB)_44") (pintype "unspecified"))
    )
    (net (code "24") (name "ADC1_D7B") (class "Default")
      (node (ref "U3") (pin "74") (pinfunction "IO_74") (pintype "input"))
      (node (ref "U8") (pin "17") (pinfunction "D7B_(MSB)_17") (pintype "unspecified"))
    )
    (net (code "25") (name "ADC1_ENCA") (class "Default")
      (node (ref "U3") (pin "75") (pinfunction "IO_75") (pintype "input"))
      (node (ref "U8") (pin "47") (pinfunction "ENCA_47") (pintype "unspecified"))
    )
    (net (code "26") (name "ADC1_ENCB") (class "Default")
      (node (ref "U3") (pin "53") (pinfunction "DIFFIO_B11n,IO_53") (pintype "input"))
      (node (ref "U8") (pin "14") (pinfunction "ENCB_14") (pintype "unspecified"))
    )
    (net (code "27") (name "ADC1_OFFSET") (class "Default")
      (node (ref "R26") (pin "1") (pinfunction "1_1") (pintype "unspecified"))
      (node (ref "U3") (pin "112") (pinfunction "PLL2_CLKOUTn,IO_112") (pintype "input"))
    )
    (net (code "28") (name "ADC2_D0A") (class "Default")
      (node (ref "U3") (pin "91") (pinfunction "CLK4,DIFFCLK_2p_91") (pintype "input"))
      (node (ref "U7") (pin "37") (pinfunction "D0A_37") (pintype "unspecified"))
    )
    (net (code "29") (name "ADC2_D0B") (class "Default")
      (node (ref "U3") (pin "98") (pinfunction "(INT_DONE),DIFFIO_R4n,IO_98") (pintype "input"))
      (node (ref "U7") (pin "24") (pinfunction "D0B_24") (pintype "unspecified"))
    )
    (net (code "30") (name "ADC2_D1A") (class "Default")
      (node (ref "U3") (pin "90") (pinfunction "CLK5,DIFFCLK_2n_90") (pintype "input"))
      (node (ref "U7") (pin "38") (pinfunction "D1A_38") (pintype "unspecified"))
    )
    (net (code "31") (name "ADC2_D1B") (class "Default")
      (node (ref "U3") (pin "99") (pinfunction "(CRC_ERROR),DIFFIO_R4P,IO_99") (pintype "input"))
      (node (ref "U7") (pin "23") (pinfunction "D1B_23") (pintype "unspecified"))
    )
    (net (code "32") (name "ADC2_D2A") (class "Default")
      (node (ref "U3") (pin "89") (pinfunction "CLK6,DIFFCLK_3p_89") (pintype "input"))
      (node (ref "U7") (pin "39") (pinfunction "D2A_39") (pintype "unspecified"))
    )
    (net (code "33") (name "ADC2_D2B") (class "Default")
      (node (ref "U3") (pin "100") (pinfunction "IO_100") (pintype "input"))
      (node (ref "U7") (pin "22") (pinfunction "D2B_22") (pintype "unspecified"))
    )
    (net (code "34") (name "ADC2_D3A") (class "Default")
      (node (ref "U3") (pin "88") (pinfunction "CLK7,DIFFCLK_3n_88") (pintype "input"))
      (node (ref "U7") (pin "40") (pinfunction "D3A_40") (pintype "unspecified"))
    )
    (net (code "35") (name "ADC2_D3B") (class "Default")
      (node (ref "U3") (pin "101") (pinfunction "(nCEO),DIFFIO_R3n,IO_101") (pintype "input"))
      (node (ref "U7") (pin "21") (pinfunction "D3B_21") (pintype "unspecified"))
    )
    (net (code "36") (name "ADC2_D4A") (class "Default")
      (node (ref "U3") (pin "87") (pinfunction "(DEV_CLRn),DIFFIO_R7p,IO_87") (pintype "input"))
      (node (ref "U7") (pin "41") (pinfunction "D4A_41") (pintype "unspecified"))
    )
    (net (code "37") (name "ADC2_D4B") (class "Default")
      (node (ref "U3") (pin "103") (pinfunction "(CLKUSR),DIFFIO_R3p,IO_103") (pintype "input"))
      (node (ref "U7") (pin "20") (pinfunction "D4B_20") (pintype "unspecified"))
    )
    (net (code "38") (name "ADC2_D5A") (class "Default")
      (node (ref "U3") (pin "86") (pinfunction "(DEV_OE),DIFFIO_R7n,IO_86") (pintype "input"))
      (node (ref "U7") (pin "42") (pinfunction "D5A_42") (pintype "unspecified"))
    )
    (net (code "39") (name "ADC2_D5B") (class "Default")
      (node (ref "U3") (pin "104") (pinfunction "(DQS0R/CQ1R,DPCLK5),IO_104") (pintype "input"))
      (node (ref "U7") (pin "19") (pinfunction "D5B_19") (pintype "unspecified"))
    )
    (net (code "40") (name "ADC2_D6A") (class "Default")
      (node (ref "U3") (pin "85") (pinfunction "(DQS1R/CQ1R#,DPCLK4),DIFFIO_R8p,IO_85") (pintype "input"))
      (node (ref "U7") (pin "43") (pinfunction "D6A_43") (pintype "unspecified"))
    )
    (net (code "41") (name "ADC2_D6B") (class "Default")
      (node (ref "U3") (pin "105") (pinfunction "VERFB6N0,IO_105") (pintype "input"))
      (node (ref "U7") (pin "18") (pinfunction "D6B_18") (pintype "unspecified"))
    )
    (net (code "42") (name "ADC2_D7A") (class "Default")
      (node (ref "U3") (pin "84") (pinfunction "DIFFIO_R8n,IO_84") (pintype "input"))
      (node (ref "U7") (pin "44") (pinfunction "D7A_(MSB)_44") (pintype "unspecified"))
    )
    (net (code "43") (name "ADC2_D7B") (class "Default")
      (node (ref "U3") (pin "106") (pinfunction "DIFFIO_R1n,IO_106") (pintype "input"))
      (node (ref "U7") (pin "17") (pinfunction "D7B_(MSB)_17") (pintype "unspecified"))
    )
    (net (code "44") (name "ADC2_ENCA") (class "Default")
      (node (ref "U3") (pin "110") (pinfunction "(DQS0T/CQ1T,DPCLK6),DIFFIO_T20p,IO_110") (pintype "input"))
      (node (ref "U7") (pin "47") (pinfunction "ENCA_47") (pintype "unspecified"))
    )
    (net (code "45") (name "ADC2_ENCB") (class "Default")
      (node (ref "U3") (pin "83") (pinfunction "IO_83") (pintype "input"))
      (node (ref "U7") (pin "14") (pinfunction "ENCB_14") (pintype "unspecified"))
    )
    (net (code "46") (name "ADC2_OFFSET") (class "Default")
      (node (ref "R24") (pin "1") (pinfunction "1_1") (pintype "unspecified"))
      (node (ref "U3") (pin "111") (pinfunction "DIFFIO_T19p,IO_111") (pintype "input"))
    )
    (net (code "47") (name "ANALOG1_AC_DC") (class "Default")
      (node (ref "R19") (pin "1") (pinfunction "1_1") (pintype "unspecified"))
      (node (ref "U18") (pin "1") (pinfunction "A_1") (pintype "unspecified"))
    )
    (net (code "48") (name "ANALOG1_ADC_INPUT") (class "Default")
      (node (ref "C114") (pin "1") (pinfunction "1_1") (pintype "input"))
      (node (ref "K1") (pin "4") (pinfunction "4_4") (pintype "input"))
      (node (ref "K1") (pin "5") (pinfunction "5_5") (pintype "input"))
      (node (ref "R23") (pin "1") (pinfunction "1_1") (pintype "unspecified"))
      (node (ref "R69") (pin "2") (pinfunction "2_2") (pintype "unspecified"))
      (node (ref "U17") (pin "1") (pinfunction "OUT_1") (pintype "output"))
    )
    (net (code "49") (name "ANALOG1_RELAIS1") (class "Default")
      (node (ref "Q1") (pin "1") (pinfunction "B_1") (pintype "input"))
      (node (ref "R13") (pin "1") (pinfunction "1_1") (pintype "unspecified"))
    )
    (net (code "50") (name "ANALOG1_RELAIS2") (class "Default")
      (node (ref "Q2") (pin "1") (pinfunction "B_1") (pintype "input"))
      (node (ref "R14") (pin "1") (pinfunction "1_1") (pintype "unspecified"))
    )
    (net (code "51") (name "ANALOG1_RELAIS3") (class "Default")
      (node (ref "Q3") (pin "1") (pinfunction "B_1") (pintype "input"))
      (node (ref "R16") (pin "1") (pinfunction "1_1") (pintype "unspecified"))
    )
    (net (code "52") (name "ANALOG2_AC_DC") (class "Default")
      (node (ref "R20") (pin "1") (pinfunction "1_1") (pintype "unspecified"))
      (node (ref "U19") (pin "1") (pinfunction "A_1") (pintype "unspecified"))
    )
    (net (code "53") (name "ANALOG2_ADC_INPUT") (class "Default")
      (node (ref "C118") (pin "1") (pinfunction "1_1") (pintype "input"))
      (node (ref "K6") (pin "4") (pinfunction "4_4") (pintype "input"))
      (node (ref "K6") (pin "5") (pinfunction "5_5") (pintype "input"))
      (node (ref "R22") (pin "1") (pinfunction "1_1") (pintype "unspecified"))
      (node (ref "R73") (pin "2") (pinfunction "2_2") (pintype "unspecified"))
      (node (ref "U20") (pin "1") (pinfunction "OUT_1") (pintype "output"))
    )
    (net (code "54") (name "ANALOG2_RELAIS1") (class "Default")
      (node (ref "Q6") (pin "1") (pinfunction "B_1") (pintype "input"))
      (node (ref "R18") (pin "1") (pinfunction "1_1") (pintype "unspecified"))
    )
    (net (code "55") (name "ANALOG2_RELAIS2") (class "Default")
      (node (ref "Q5") (pin "1") (pinfunction "B_1") (pintype "input"))
      (node (ref "R15") (pin "1") (pinfunction "1_1") (pintype "unspecified"))
    )
    (net (code "56") (name "ANALOG2_RELAIS3") (class "Default")
      (node (ref "Q4") (pin "1") (pinfunction "B_1") (pintype "input"))
      (node (ref "R17") (pin "1") (pinfunction "1_1") (pintype "unspecified"))
    )
    (net (code "57") (name "BATTERY_CHARGING") (class "Default")
      (node (ref "R48") (pin "1") (pinfunction "1_1") (pintype "unspecified"))
      (node (ref "U1") (pin "37") (pinfunction "PE12/DA_MCLK/TWI0_SDA/PWM0_37") (pintype "unspecified"))
      (node (ref "U9") (pin "7") (pinfunction "CHRG#_7") (pintype "unspecified"))
    )
    (net (code "58") (name "Backlight V+") (class "Default")
      (node (ref "C97") (pin "1") (pinfunction "1_1") (pintype "input"))
      (node (ref "C98") (pin "1") (pinfunction "1_1") (pintype "input"))
      (node (ref "D10") (pin "2") (pinfunction "K_2") (pintype "unspecified"))
      (node (ref "P3") (pin "1") (pinfunction "1_1") (pintype "unspecified"))
      (node (ref "P3") (pin "2") (pinfunction "2_2") (pintype "unspecified"))
      (node (ref "U16") (pin "5") (pinfunction "OV_5") (pintype "unspecified"))
    )
    (net (code "59") (name "Backlight V-") (class "Default")
      (node (ref "P3") (pin "3") (pinfunction "3_3") (pintype "unspecified"))
      (node (ref "P3") (pin "4") (pinfunction "4_4") (pintype "unspecified"))
      (node (ref "R60") (pin "2") (pinfunction "2_2") (pintype "unspecified"))
      (node (ref "R61") (pin "2") (pinfunction "2_2") (pintype "unspecified"))
      (node (ref "U16") (pin "3") (pinfunction "FB_3") (pintype "unspecified"))
    )
    (net (code "60") (name "F1C100S_FPGA_CLK") (class "Default")
      (node (ref "U1") (pin "41") (pinfunction "PE8/CSI_D5/UART2_RX/SPI1_MOSI_41") (pintype "unspecified"))
      (node (ref "U3") (pin "1") (pinfunction "IO_1") (pintype "input"))
    )
    (net (code "61") (name "F1C100S_FPGA_DB0") (class "Default")
      (node (ref "U1") (pin "49") (pinfunction "PE0/CSI_HSYNC/LCD_D0/TWI2_SCK/UART0_RX_49") (pintype "unspecified"))
      (node (ref "U3") (pin "135") (pinfunction "(DQ1T),DIFFIO_T8n,IO_135") (pintype "input"))
    )
    (net (code "62") (name "F1C100S_FPGA_DB1") (class "Default")
      (node (ref "U1") (pin "48") (pinfunction "PE1/CSI_VSYNC/LCD_D1/TWI2_SDA/UART0_TX_48") (pintype "unspecified"))
      (node (ref "U3") (pin "136") (pinfunction "VREFB8N0,IO_136") (pintype "input"))
    )
    (net (code "63") (name "F1C100S_FPGA_DB2") (class "Default")
      (node (ref "U1") (pin "47") (pinfunction "PE2/CSI_PCLK/LCD_D8/CLK_OUT_47") (pintype "unspecified"))
      (node (ref "U3") (pin "137") (pinfunction "(DQ1T),(DATA5),IO_137") (pintype "input"))
    )
    (net (code "64") (name "F1C100S_FPGA_DB3") (class "Default")
      (node (ref "U1") (pin "46") (pinfunction "PE3/CSI_D0/LCD_D9/DA_BCLK_46") (pintype "unspecified"))
      (node (ref "U3") (pin "138") (pinfunction "(DATA6),IO_138") (pintype "input"))
    )
    (net (code "65") (name "F1C100S_FPGA_DB4") (class "Default")
      (node (ref "U1") (pin "45") (pinfunction "PE4/CSI_D1/LCD_D16/DA_LRCK_45") (pintype "unspecified"))
      (node (ref "U3") (pin "141") (pinfunction "DIFFIO_T5p,IO_141") (pintype "input"))
    )
    (net (code "66") (name "F1C100S_FPGA_DB5") (class "Default")
      (node (ref "U1") (pin "44") (pinfunction "PE5/CSI_D2/LCD_D17/DA_IN_44") (pintype "unspecified"))
      (node (ref "U3") (pin "142") (pinfunction "(DQS1T/CQ1T#,DPCLK7),DIFFIO_T2p,IO_142") (pintype "input"))
    )
    (net (code "67") (name "F1C100S_FPGA_DB6") (class "Default")
      (node (ref "U1") (pin "43") (pinfunction "PE6/CSI_D3/PWM1/DA_OUT/OWA_OUT_43") (pintype "unspecified"))
      (node (ref "U3") (pin "143") (pinfunction "(DQ1T),DIFFIO_T1n,IO_143") (pintype "input"))
    )
    (net (code "68") (name "F1C100S_FPGA_DB7") (class "Default")
      (node (ref "U1") (pin "42") (pinfunction "PE7/CSI_D4/UART2_TX/SPI1_CS_42") (pintype "unspecified"))
      (node (ref "U3") (pin "144") (pinfunction "(DM1T),DIFFIO_T1p,IO_144") (pintype "input"))
    )
    (net (code "69") (name "F1C100S_FPGA_DCS") (class "Default")
      (node (ref "U1") (pin "39") (pinfunction "PE10/CSI_D7/UART2_CTS/SPI1_MISO_39") (pintype "unspecified"))
      (node (ref "U3") (pin "3") (pinfunction "IO_3") (pintype "input"))
    )
    (net (code "70") (name "F1C100S_FPGA_RWS") (class "Default")
      (node (ref "U1") (pin "40") (pinfunction "PE9/CSI_D6/UART2_RTS/SPI1_CLK_40") (pintype "unspecified"))
      (node (ref "U3") (pin "2") (pinfunction "IO_2") (pintype "input"))
    )
    (net (code "71") (name "FPGA_BACKLIGHT_PWM") (class "Default")
      (node (ref "R59") (pin "2") (pinfunction "2_2") (pintype "unspecified"))
      (node (ref "U16") (pin "4") (pinfunction "EN_4") (pintype "unspecified"))
      (node (ref "U3") (pin "42") (pinfunction "(DQS1B/CQ1B#,DPCLK2),IO_42") (pintype "input"))
    )
    (net (code "72") (name "FPGA_Conf_ASDO") (class "Default")
      (node (ref "J2") (pin "6") (pinfunction "6_6") (pintype "input"))
      (node (ref "U3") (pin "6") (pinfunction "(DATA1,ASDO),DIFFIO_L1n,IO_6") (pintype "input"))
      (node (ref "U4") (pin "5") (pinfunction "DI_5") (pintype "unspecified"))
    )
    (net (code "73") (name "FPGA_Conf_CLK") (class "Default")
      (node (ref "J2") (pin "5") (pinfunction "5_5") (pintype "input"))
      (node (ref "U3") (pin "12") (pinfunction "DCLK_12") (pintype "input"))
      (node (ref "U4") (pin "6") (pinfunction "CLK_6") (pintype "unspecified"))
    )
    (net (code "74") (name "FPGA_Conf_Data") (class "Default")
      (node (ref "J2") (pin "3") (pinfunction "3_3") (pintype "input"))
      (node (ref "R1") (pin "1") (pinfunction "1_1") (pintype "unspecified"))
      (node (ref "U3") (pin "13") (pinfunction "(DATA0),IO_13") (pintype "input"))
    )
    (net (code "75") (name "FPGA_Conf_nCE") (class "Default")
      (node (ref "J2") (pin "1") (pinfunction "1_1") (pintype "input"))
      (node (ref "U3") (pin "8") (pinfunction "(FLASH_nCE,nCSO),DIFFIO_L2p,IO_8") (pintype "input"))
      (node (ref "U4") (pin "1") (pinfunction "/CS_1") (pintype "unspecified"))
    )
    (net (code "76") (name "FPGA_EEPROM_SCL") (class "Default")
      (node (ref "J3") (pin "3") (pinfunction "3_3") (pintype "input"))
      (node (ref "R3") (pin "1") (pinfunction "1_1") (pintype "unspecified"))
      (node (ref "U3") (pin "39") (pinfunction "DIFFIO_B1n,IO_39") (pintype "input"))
      (node (ref "U5") (pin "6") (pinfunction "SCL_6") (pintype "unspecified"))
    )
    (net (code "77") (name "FPGA_EEPROM_SDA") (class "Default")
      (node (ref "J3") (pin "4") (pinfunction "4_4") (pintype "input"))
      (node (ref "R2") (pin "1") (pinfunction "1_1") (pintype "unspecified"))
      (node (ref "U3") (pin "38") (pinfunction "DIFFIO_B1p,IO_38") (pintype "input"))
      (node (ref "U5") (pin "5") (pinfunction "SDA_5") (pintype "unspecified"))
    )
    (net (code "78") (name "GND") (class "Default")
      (node (ref "C1") (pin "2") (pinfunction "2_2") (pintype "input"))
      (node (ref "C10") (pin "2") (pinfunction "2_2") (pintype "input"))
      (node (ref "C100") (pin "1") (pinfunction "1_1") (pintype "input"))
      (node (ref "C101") (pin "2") (pinfunction "2_2") (pintype "input"))
      (node (ref "C106") (pin "1") (pinfunction "1_1") (pintype "input"))
      (node (ref "C11") (pin "2") (pinfunction "2_2") (pintype "input"))
      (node (ref "C111") (pin "1") (pinfunction "1_1") (pintype "input"))
      (node (ref "C112") (pin "1") (pinfunction "1_1") (pintype "input"))
      (node (ref "C113") (pin "1") (pinfunction "1_1") (pintype "input"))
      (node (ref "C115") (pin "1") (pinfunction "1_1") (pintype "input"))
      (node (ref "C117") (pin "1") (pinfunction "1_1") (pintype "input"))
      (node (ref "C119") (pin "1") (pinfunction "1_1") (pintype "input"))
      (node (ref "C12") (pin "2") (pinfunction "2_2") (pintype "input"))
      (node (ref "C120") (pin "1") (pinfunction "1_1") (pintype "input"))
      (node (ref "C121") (pin "1") (pinfunction "1_1") (pintype "input"))
      (node (ref "C126") (pin "1") (pinfunction "1_1") (pintype "input"))
      (node (ref "C13") (pin "2") (pinfunction "2_2") (pintype "input"))
      (node (ref "C131") (pin "2") (pinfunction "2_2") (pintype "input"))
      (node (ref "C132") (pin "1") (pinfunction "1_1") (pintype "input"))
      (node (ref "C134") (pin "1") (pinfunction "1_1") (pintype "input"))
      (node (ref "C135") (pin "1") (pinfunction "1_1") (pintype "input"))
      (node (ref "C14") (pin "2") (pinfunction "2_2") (pintype "input"))
      (node (ref "C15") (pin "2") (pinfunction "2_2") (pintype "input"))
      (node (ref "C16") (pin "2") (pinfunction "2_2") (pintype "input"))
      (node (ref "C17") (pin "2") (pinfunction "2_2") (pintype "input"))
      (node (ref "C18") (pin "2") (pinfunction "2_2") (pintype "input"))
      (node (ref "C19") (pin "2") (pinfunction "2_2") (pintype "input"))
      (node (ref "C20") (pin "2") (pinfunction "2_2") (pintype "input"))
      (node (ref "C21") (pin "2") (pinfunction "2_2") (pintype "input"))
      (node (ref "C22") (pin "2") (pinfunction "2_2") (pintype "input"))
      (node (ref "C23") (pin "2") (pinfunction "2_2") (pintype "input"))
      (node (ref "C24") (pin "2") (pinfunction "2_2") (pintype "input"))
      (node (ref "C25") (pin "2") (pinfunction "2_2") (pintype "input"))
      (node (ref "C26") (pin "2") (pinfunction "2_2") (pintype "input"))
      (node (ref "C27") (pin "2") (pinfunction "2_2") (pintype "input"))
      (node (ref "C28") (pin "2") (pinfunction "2_2") (pintype "input"))
      (node (ref "C29") (pin "2") (pinfunction "2_2") (pintype "input"))
      (node (ref "C30") (pin "2") (pinfunction "2_2") (pintype "input"))
      (node (ref "C31") (pin "2") (pinfunction "2_2") (pintype "input"))
      (node (ref "C32") (pin "2") (pinfunction "2_2") (pintype "input"))
      (node (ref "C33") (pin "2") (pinfunction "2_2") (pintype "input"))
      (node (ref "C34") (pin "2") (pinfunction "2_2") (pintype "input"))
      (node (ref "C35") (pin "2") (pinfunction "2_2") (pintype "input"))
      (node (ref "C36") (pin "2") (pinfunction "2_2") (pintype "input"))
      (node (ref "C37") (pin "2") (pinfunction "2_2") (pintype "input"))
      (node (ref "C38") (pin "2") (pinfunction "2_2") (pintype "input"))
      (node (ref "C39") (pin "2") (pinfunction "2_2") (pintype "input"))
      (node (ref "C4") (pin "2") (pinfunction "2_2") (pintype "input"))
      (node (ref "C40") (pin "2") (pinfunction "2_2") (pintype "input"))
      (node (ref "C41") (pin "2") (pinfunction "2_2") (pintype "input"))
      (node (ref "C42") (pin "2") (pinfunction "2_2") (pintype "input"))
      (node (ref "C43") (pin "2") (pinfunction "2_2") (pintype "input"))
      (node (ref "C44") (pin "2") (pinfunction "2_2") (pintype "input"))
      (node (ref "C45") (pin "2") (pinfunction "2_2") (pintype "input"))
      (node (ref "C46") (pin "2") (pinfunction "2_2") (pintype "input"))
      (node (ref "C47") (pin "2") (pinfunction "2_2") (pintype "input"))
      (node (ref "C48") (pin "2") (pinfunction "2_2") (pintype "input"))
      (node (ref "C49") (pin "2") (pinfunction "2_2") (pintype "input"))
      (node (ref "C50") (pin "2") (pinfunction "2_2") (pintype "input"))
      (node (ref "C51") (pin "2") (pinfunction "2_2") (pintype "input"))
      (node (ref "C52") (pin "2") (pinfunction "2_2") (pintype "input"))
      (node (ref "C53") (pin "2") (pinfunction "2_2") (pintype "input"))
      (node (ref "C54") (pin "2") (pinfunction "2_2") (pintype "input"))
      (node (ref "C55") (pin "2") (pinfunction "2_2") (pintype "input"))
      (node (ref "C56") (pin "2") (pinfunction "2_2") (pintype "input"))
      (node (ref "C58") (pin "2") (pinfunction "2_2") (pintype "input"))
      (node (ref "C59") (pin "2") (pinfunction "2_2") (pintype "input"))
      (node (ref "C60") (pin "2") (pinfunction "2_2") (pintype "input"))
      (node (ref "C61") (pin "2") (pinfunction "2_2") (pintype "input"))
      (node (ref "C62") (pin "2") (pinfunction "2_2") (pintype "input"))
      (node (ref "C63") (pin "2") (pinfunction "2_2") (pintype "input"))
      (node (ref "C64") (pin "2") (pinfunction "2_2") (pintype "input"))
      (node (ref "C65") (pin "2") (pinfunction "2_2") (pintype "input"))
      (node (ref "C66") (pin "2") (pinfunction "2_2") (pintype "input"))
      (node (ref "C67") (pin "2") (pinfunction "2_2") (pintype "input"))
      (node (ref "C68") (pin "2") (pinfunction "2_2") (pintype "input"))
      (node (ref "C69") (pin "2") (pinfunction "2_2") (pintype "input"))
      (node (ref "C7") (pin "2") (pinfunction "2_2") (pintype "input"))
      (node (ref "C70") (pin "2") (pinfunction "2_2") (pintype "input"))
      (node (ref "C71") (pin "2") (pinfunction "2_2") (pintype "input"))
      (node (ref "C72") (pin "2") (pinfunction "2_2") (pintype "input"))
      (node (ref "C73") (pin "2") (pinfunction "2_2") (pintype "input"))
      (node (ref "C74") (pin "2") (pinfunction "2_2") (pintype "input"))
      (node (ref "C75") (pin "2") (pinfunction "2_2") (pintype "input"))
      (node (ref "C76") (pin "2") (pinfunction "2_2") (pintype "input"))
      (node (ref "C77") (pin "2") (pinfunction "2_2") (pintype "input"))
      (node (ref "C78") (pin "2") (pinfunction "2_2") (pintype "input"))
      (node (ref "C79") (pin "2") (pinfunction "2_2") (pintype "input"))
      (node (ref "C8") (pin "2") (pinfunction "2_2") (pintype "input"))
      (node (ref "C80") (pin "2") (pinfunction "2_2") (pintype "input"))
      (node (ref "C81") (pin "2") (pinfunction "2_2") (pintype "input"))
      (node (ref "C82") (pin "2") (pinfunction "2_2") (pintype "input"))
      (node (ref "C83") (pin "2") (pinfunction "2_2") (pintype "input"))
      (node (ref "C84") (pin "2") (pinfunction "2_2") (pintype "input"))
      (node (ref "C85") (pin "2") (pinfunction "2_2") (pintype "input"))
      (node (ref "C86") (pin "2") (pinfunction "2_2") (pintype "input"))
      (node (ref "C87") (pin "2") (pinfunction "2_2") (pintype "input"))
      (node (ref "C88") (pin "2") (pinfunction "2_2") (pintype "input"))
      (node (ref "C9") (pin "2") (pinfunction "2_2") (pintype "input"))
      (node (ref "C90") (pin "2") (pinfunction "2_2") (pintype "input"))
      (node (ref "C91") (pin "2") (pinfunction "2_2") (pintype "input"))
      (node (ref "C92") (pin "2") (pinfunction "2_2") (pintype "input"))
      (node (ref "C93") (pin "2") (pinfunction "2_2") (pintype "input"))
      (node (ref "C94") (pin "2") (pinfunction "2_2") (pintype "input"))
      (node (ref "C95") (pin "2") (pinfunction "2_2") (pintype "input"))
      (node (ref "C96") (pin "2") (pinfunction "2_2") (pintype "input"))
      (node (ref "C97") (pin "2") (pinfunction "2_2") (pintype "input"))
      (node (ref "C98") (pin "2") (pinfunction "2_2") (pintype "input"))
      (node (ref "CON1") (pin "2") (pinfunction "2_2") (pintype "bidirectional"))
      (node (ref "D11") (pin "2") (pinfunction "2_2") (pintype "unspecified"))
      (node (ref "D8") (pin "2") (pinfunction "K_2") (pintype "unspecified"))
      (node (ref "J1") (pin "2") (pinfunction "2_2") (pintype "input"))
      (node (ref "J2") (pin "2") (pinfunction "2_2") (pintype "input"))
      (node (ref "J3") (pin "1") (pinfunction "1_1") (pintype "input"))
      (node (ref "K1") (pin "8") (pinfunction "8_8") (pintype "input"))
      (node (ref "K2") (pin "8") (pinfunction "8_8") (pintype "input"))
      (node (ref "K3") (pin "8") (pinfunction "8_8") (pintype "input"))
      (node (ref "K4") (pin "8") (pinfunction "8_8") (pintype "input"))
      (node (ref "K5") (pin "8") (pinfunction "8_8") (pintype "input"))
      (node (ref "K6") (pin "8") (pinfunction "8_8") (pintype "input"))
      (node (ref "L2") (pin "1") (pinfunction "1_1") (pintype "unspecified"))
      (node (ref "L3") (pin "1") (pinfunction "1_1") (pintype "unspecified"))
      (node (ref "LED2") (pin "2") (pinfunction "2_2") (pintype "unspecified"))
      (node (ref "P1") (pin "3") (pinfunction "3_3") (pintype "unspecified"))
      (node (ref "P2") (pin "10") (pinfunction "BODY_10") (pintype "unspecified"))
      (node (ref "P2") (pin "6") (pinfunction "GND_6") (pintype "unspecified"))
      (node (ref "P2") (pin "9") (pinfunction "CARD_DETECT_9") (pintype "unspecified"))
      (node (ref "P3") (pin "17") (pinfunction "17_17") (pintype "unspecified"))
      (node (ref "P3") (pin "18") (pinfunction "18_18") (pintype "unspecified"))
      (node (ref "P3") (pin "19") (pinfunction "19_19") (pintype "unspecified"))
      (node (ref "P3") (pin "26") (pinfunction "26_26") (pintype "unspecified"))
      (node (ref "P3") (pin "27") (pinfunction "27_27") (pintype "unspecified"))
      (node (ref "P3") (pin "33") (pinfunction "33_33") (pintype "unspecified"))
      (node (ref "P3") (pin "34") (pinfunction "34_34") (pintype "unspecified"))
      (node (ref "P3") (pin "35") (pinfunction "35_35") (pintype "unspecified"))
      (node (ref "P3") (pin "36") (pinfunction "36_36") (pintype "unspecified"))
      (node (ref "P3") (pin "38") (pinfunction "38_38") (pintype "unspecified"))
      (node (ref "P3") (pin "40") (pinfunction "40_40") (pintype "unspecified"))
      (node (ref "P3") (pin "47") (pinfunction "47_47") (pintype "unspecified"))
      (node (ref "P3") (pin "48") (pinfunction "48_48") (pintype "unspecified"))
      (node (ref "P3") (pin "49") (pinfunction "49_49") (pintype "unspecified"))
      (node (ref "P3") (pin "5") (pinfunction "5_5") (pintype "unspecified"))
      (node (ref "P3") (pin "50") (pinfunction "50_50") (pintype "unspecified"))
      (node (ref "P3") (pin "8") (pinfunction "8_8") (pintype "unspecified"))
      (node (ref "R29") (pin "1") (pinfunction "1_1") (pintype "unspecified"))
      (node (ref "R31") (pin "1") (pinfunction "1_1") (pintype "unspecified"))
      (node (ref "R32") (pin "1") (pinfunction "1_1") (pintype "unspecified"))
      (node (ref "R45") (pin "1") (pinfunction "1_1") (pintype "unspecified"))
      (node (ref "R46") (pin "1") (pinfunction "1_1") (pintype "unspecified"))
      (node (ref "R47") (pin "1") (pinfunction "1_1") (pintype "unspecified"))
      (node (ref "R51") (pin "1") (pinfunction "1_1") (pintype "unspecified"))
      (node (ref "R52") (pin "1") (pinfunction "1_1") (pintype "unspecified"))
      (node (ref "R53") (pin "1") (pinfunction "1_1") (pintype "unspecified"))
      (node (ref "R55") (pin "1") (pinfunction "1_1") (pintype "unspecified"))
      (node (ref "R57") (pin "1") (pinfunction "1_1") (pintype "unspecified"))
      (node (ref "R58") (pin "1") (pinfunction "1_1") (pintype "unspecified"))
      (node (ref "R59") (pin "1") (pinfunction "1_1") (pintype "unspecified"))
      (node (ref "R6") (pin "2") (pinfunction "2_2") (pintype "unspecified"))
      (node (ref "R60") (pin "1") (pinfunction "1_1") (pintype "unspecified"))
      (node (ref "R61") (pin "1") (pinfunction "1_1") (pintype "unspecified"))
      (node (ref "R7") (pin "2") (pinfunction "2_2") (pintype "unspecified"))
      (node (ref "U1") (pin "74") (pinfunction "TVGND_74") (pintype "unspecified"))
      (node (ref "U1") (pin "82") (pinfunction "AGND_82") (pintype "unspecified"))
      (node (ref "U1") (pin "89") (pinfunction "GND_89") (pintype "unspecified"))
      (node (ref "U10") (pin "1") (pinfunction "TEMP_1") (pintype "unspecified"))
      (node (ref "U10") (pin "3") (pinfunction "GND_3") (pintype "unspecified"))
      (node (ref "U11") (pin "1") (pinfunction "VSS/ADJ_1") (pintype "unspecified"))
      (node (ref "U12") (pin "1") (pinfunction "GND_1") (pintype "passive"))
      (node (ref "U14") (pin "1") (pinfunction "GND_1") (pintype "passive"))
      (node (ref "U15") (pin "2") (pinfunction "GND_2") (pintype "unspecified"))
      (node (ref "U16") (pin "2") (pinfunction "GND_2") (pintype "unspecified"))
      (node (ref "U17") (pin "2") (pinfunction "V-_2") (pintype "passive"))
      (node (ref "U18") (pin "2") (pinfunction "K_2") (pintype "unspecified"))
      (node (ref "U19") (pin "2") (pinfunction "K_2") (pintype "unspecified"))
      (node (ref "U2") (pin "4") (pinfunction "GND_4") (pintype "unspecified"))
      (node (ref "U20") (pin "2") (pinfunction "V-_2") (pintype "passive"))
      (node (ref "U21") (pin "3") (pinfunction "ANODE_3") (pintype "unspecified"))
      (node (ref "U3") (pin "118") (pinfunction "GND_118") (pintype "input"))
      (node (ref "U3") (pin "123") (pinfunction "GND_123") (pintype "input"))
      (node (ref "U3") (pin "131") (pinfunction "GND_131") (pintype "input"))
      (node (ref "U3") (pin "140") (pinfunction "GND_140") (pintype "input"))
      (node (ref "U3") (pin "145") (pinfunction "GND_(PAD)_145") (pintype "input"))
      (node (ref "U3") (pin "19") (pinfunction "GND_19") (pintype "input"))
      (node (ref "U3") (pin "22") (pinfunction "GND_22") (pintype "input"))
      (node (ref "U3") (pin "27") (pinfunction "GND_27") (pintype "input"))
      (node (ref "U3") (pin "4") (pinfunction "GND_4") (pintype "input"))
      (node (ref "U3") (pin "41") (pinfunction "GND_41") (pintype "input"))
      (node (ref "U3") (pin "48") (pinfunction "GND_48") (pintype "input"))
      (node (ref "U3") (pin "57") (pinfunction "GND_57") (pintype "input"))
      (node (ref "U3") (pin "63") (pinfunction "GND_63") (pintype "input"))
      (node (ref "U3") (pin "79") (pinfunction "GND_79") (pintype "input"))
      (node (ref "U3") (pin "82") (pinfunction "GND_82") (pintype "input"))
      (node (ref "U3") (pin "94") (pinfunction "MSEL0_94") (pintype "input"))
      (node (ref "U3") (pin "95") (pinfunction "GND_95") (pintype "input"))
      (node (ref "U3") (pin "97") (pinfunction "MSEL2_97") (pintype "input"))
      (node (ref "U4") (pin "4") (pinfunction "GND_4") (pintype "unspecified"))
      (node (ref "U5") (pin "4") (pinfunction "VSS_4") (pintype "unspecified"))
      (node (ref "U6") (pin "3") (pinfunction "GND_3") (pintype "unspecified"))
      (node (ref "U6") (pin "6") (pinfunction "TAB_6") (pintype "unspecified"))
      (node (ref "U7") (pin "1") (pinfunction "GND_1") (pintype "passive"))
      (node (ref "U7") (pin "12") (pinfunction "GND_12") (pintype "passive"))
      (node (ref "U7") (pin "16") (pinfunction "GND_16") (pintype "passive"))
      (node (ref "U7") (pin "27") (pinfunction "GND_27") (pintype "passive"))
      (node (ref "U7") (pin "29") (pinfunction "GND_29") (pintype "passive"))
      (node (ref "U7") (pin "32") (pinfunction "GND_32") (pintype "passive"))
      (node (ref "U7") (pin "34") (pinfunction "GND_34") (pintype "passive"))
      (node (ref "U7") (pin "4") (pinfunction "DFS_4") (pintype "unspecified"))
      (node (ref "U7") (pin "45") (pinfunction "GND_45") (pintype "passive"))
      (node (ref "U8") (pin "1") (pinfunction "GND_1") (pintype "passive"))
      (node (ref "U8") (pin "12") (pinfunction "GND_12") (pintype "passive"))
      (node (ref "U8") (pin "16") (pinfunction "GND_16") (pintype "passive"))
      (node (ref "U8") (pin "27") (pinfunction "GND_27") (pintype "passive"))
      (node (ref "U8") (pin "29") (pinfunction "GND_29") (pintype "passive"))
      (node (ref "U8") (pin "32") (pinfunction "GND_32") (pintype "passive"))
      (node (ref "U8") (pin "34") (pinfunction "GND_34") (pintype "passive"))
      (node (ref "U8") (pin "4") (pinfunction "DFS_4") (pintype "unspecified"))
      (node (ref "U8") (pin "45") (pinfunction "GND_45") (pintype "passive"))
      (node (ref "U9") (pin "1") (pinfunction "TEMP_1") (pintype "unspecified"))
      (node (ref "U9") (pin "3") (pinfunction "GND_3") (pintype "unspecified"))
      (node (ref "USB1") (pin "A1") (pinfunction "GND_A1") (pintype "unspecified"))
      (node (ref "USB1") (pin "A12") (pinfunction "GND_A12") (pintype "unspecified"))
      (node (ref "USB1") (pin "B1") (pinfunction "GND_B1") (pintype "unspecified"))
      (node (ref "USB1") (pin "B12") (pinfunction "GND_B12") (pintype "unspecified"))
      (node (ref "X2") (pin "2") (pinfunction "GND_2") (pintype "unspecified"))
    )
    (net (code "79") (name "LCD_CLK") (class "Default")
      (node (ref "P3") (pin "37") (pinfunction "37_37") (pintype "unspecified"))
      (node (ref "U1") (pin "26") (pinfunction "PD18/LCD_CLK/SPI0_CS_26") (pintype "unspecified"))
    )
    (net (code "80") (name "LCD_D3") (class "Default")
      (node (ref "P3") (pin "16") (pinfunction "16_16") (pintype "unspecified"))
      (node (ref "U1") (pin "7") (pinfunction "PD1/LCD_D3/UART1_RTS_7") (pintype "unspecified"))
    )
    (net (code "81") (name "LCD_D4") (class "Default")
      (node (ref "P3") (pin "15") (pinfunction "15_15") (pintype "unspecified"))
      (node (ref "U1") (pin "8") (pinfunction "PD2/LCD_D4/UART1_CTS_8") (pintype "unspecified"))
    )
    (net (code "82") (name "LCD_D5") (class "Default")
      (node (ref "P3") (pin "14") (pinfunction "14_14") (pintype "unspecified"))
      (node (ref "U1") (pin "9") (pinfunction "PD3/LCD_D5/UART1_RX_9") (pintype "unspecified"))
    )
    (net (code "83") (name "LCD_D6") (class "Default")
      (node (ref "P3") (pin "13") (pinfunction "13_13") (pintype "unspecified"))
      (node (ref "U1") (pin "10") (pinfunction "PD4/LCD_D6/UART1_TX_10") (pintype "unspecified"))
    )
    (net (code "84") (name "LCD_D7") (class "Default")
      (node (ref "P3") (pin "12") (pinfunction "12_12") (pintype "unspecified"))
      (node (ref "U1") (pin "11") (pinfunction "PD5/LCD_D7/TWI1_SCK_11") (pintype "unspecified"))
    )
    (net (code "85") (name "LCD_D10") (class "Default")
      (node (ref "P3") (pin "25") (pinfunction "25_25") (pintype "unspecified"))
      (node (ref "U1") (pin "12") (pinfunction "PD6/LCD_D10/TWI1_SDA_12") (pintype "unspecified"))
    )
    (net (code "86") (name "LCD_D11") (class "Default")
      (node (ref "P3") (pin "24") (pinfunction "24_24") (pintype "unspecified"))
      (node (ref "U1") (pin "13") (pinfunction "PD7/LCD_D11/DA_MCLK_13") (pintype "unspecified"))
    )
    (net (code "87") (name "LCD_D12") (class "Default")
      (node (ref "P3") (pin "23") (pinfunction "23_23") (pintype "unspecified"))
      (node (ref "U1") (pin "14") (pinfunction "PD8/LCD_D12/DA_BCLK_14") (pintype "unspecified"))
    )
    (net (code "88") (name "LCD_D13") (class "Default")
      (node (ref "P3") (pin "22") (pinfunction "22_22") (pintype "unspecified"))
      (node (ref "U1") (pin "15") (pinfunction "PD9/LCD_D13/DA_LRCK_15") (pintype "unspecified"))
    )
    (net (code "89") (name "LCD_D14") (class "Default")
      (node (ref "P3") (pin "21") (pinfunction "21_21") (pintype "unspecified"))
      (node (ref "U1") (pin "16") (pinfunction "PD10/LCD_D14/DA_IN_16") (pintype "unspecified"))
    )
    (net (code "90") (name "LCD_D15") (class "Default")
      (node (ref "P3") (pin "20") (pinfunction "20_20") (pintype "unspecified"))
      (node (ref "U1") (pin "17") (pinfunction "PD11/LCD_D15/DA_OUT_17") (pintype "unspecified"))
    )
    (net (code "91") (name "LCD_D19") (class "Default")
      (node (ref "P3") (pin "32") (pinfunction "32_32") (pintype "unspecified"))
      (node (ref "U1") (pin "19") (pinfunction "PD13/LCD_D19/UART2_TX_19") (pintype "unspecified"))
    )
    (net (code "92") (name "LCD_D20") (class "Default")
      (node (ref "P3") (pin "31") (pinfunction "31_31") (pintype "unspecified"))
      (node (ref "U1") (pin "21") (pinfunction "PD14/LCD_D20/UART2_RX_21") (pintype "unspecified"))
    )
    (net (code "93") (name "LCD_D21") (class "Default")
      (node (ref "P3") (pin "30") (pinfunction "30_30") (pintype "unspecified"))
      (node (ref "U1") (pin "23") (pinfunction "PD15/LCD_D21/UART2_RST/TWI2_SCK_23") (pintype "unspecified"))
    )
    (net (code "94") (name "LCD_D22") (class "Default")
      (node (ref "P3") (pin "29") (pinfunction "29_29") (pintype "unspecified"))
      (node (ref "U1") (pin "24") (pinfunction "PD16/LCD_D22/UART2_CTS/TWI2_SDA_24") (pintype "unspecified"))
    )
    (net (code "95") (name "LCD_D23") (class "Default")
      (node (ref "P3") (pin "28") (pinfunction "28_28") (pintype "unspecified"))
      (node (ref "U1") (pin "25") (pinfunction "PD17/LCD_D23/OWA_OUT_25") (pintype "unspecified"))
    )
    (net (code "96") (name "LCD_DE") (class "Default")
      (node (ref "P3") (pin "9") (pinfunction "9_9") (pintype "unspecified"))
      (node (ref "U1") (pin "27") (pinfunction "PD19/LCD_DE/SPI0_MOSI_27") (pintype "unspecified"))
    )
    (net (code "97") (name "LCD_HSYNC") (class "Default")
      (node (ref "P3") (pin "11") (pinfunction "11_11") (pintype "unspecified"))
      (node (ref "R43") (pin "1") (pinfunction "1_1") (pintype "unspecified"))
      (node (ref "U1") (pin "28") (pinfunction "PD20/LCD_HSYNC/SPI0_CLK_28") (pintype "unspecified"))
    )
    (net (code "98") (name "LCD_VSYNC") (class "Default")
      (node (ref "P3") (pin "10") (pinfunction "10_10") (pintype "unspecified"))
      (node (ref "R42") (pin "1") (pinfunction "1_1") (pintype "unspecified"))
      (node (ref "U1") (pin "29") (pinfunction "PD21/LCD_VSYNC/SPI0_MISO_29") (pintype "unspecified"))
    )
    (net (code "99") (name "MCU_FLASH_CE") (class "Default")
      (node (ref "J1") (pin "1") (pinfunction "1_1") (pintype "input"))
      (node (ref "R33") (pin "1") (pinfunction "1_1") (pintype "unspecified"))
      (node (ref "U1") (pin "60") (pinfunction "PC1/SPI0_CS/SDC1_CMD_60") (pintype "unspecified"))
      (node (ref "U2") (pin "1") (pinfunction "/CS_1") (pintype "unspecified"))
    )
    (net (code "100") (name "MCU_FLASH_CLK") (class "Default")
      (node (ref "J1") (pin "5") (pinfunction "5_5") (pintype "input"))
      (node (ref "U1") (pin "59") (pinfunction "PC0/SPI0_CLK/SDC1_CLK_59") (pintype "unspecified"))
      (node (ref "U2") (pin "6") (pinfunction "CLK_6") (pintype "unspecified"))
    )
    (net (code "101") (name "MCU_FLASH_MISO") (class "Default")
      (node (ref "J1") (pin "3") (pinfunction "3_3") (pintype "input"))
      (node (ref "U1") (pin "61") (pinfunction "PC2/SPI0_MISO/SDC1_D0_61") (pintype "unspecified"))
      (node (ref "U2") (pin "2") (pinfunction "DO_2") (pintype "unspecified"))
    )
    (net (code "102") (name "MCU_FLASH_MOSI") (class "Default")
      (node (ref "J1") (pin "6") (pinfunction "6_6") (pintype "input"))
      (node (ref "U1") (pin "62") (pinfunction "PC3/SPI0_MOSI/UART0_TX_62") (pintype "unspecified"))
      (node (ref "U2") (pin "5") (pinfunction "DI_5") (pintype "unspecified"))
    )
    (net (code "103") (name "Net-(C25-Pad1)") (class "Default")
      (node (ref "C25") (pin "1") (pinfunction "1_1") (pintype "input"))
      (node (ref "R24") (pin "2") (pinfunction "2_2") (pintype "unspecified"))
      (node (ref "R25") (pin "1") (pinfunction "1_1") (pintype "unspecified"))
    )
    (net (code "104") (name "Net-(C26-Pad1)") (class "Default")
      (node (ref "C26") (pin "1") (pinfunction "1_1") (pintype "input"))
      (node (ref "C27") (pin "1") (pinfunction "1_1") (pintype "input"))
      (node (ref "R25") (pin "2") (pinfunction "2_2") (pintype "unspecified"))
      (node (ref "U7") (pin "10") (pinfunction "AINB_10") (pintype "unspecified"))
      (node (ref "U7") (pin "3") (pinfunction "AINA_3") (pintype "unspecified"))
    )
    (net (code "105") (name "Net-(C28-Pad1)") (class "Default")
      (node (ref "C28") (pin "1") (pinfunction "1_1") (pintype "input"))
      (node (ref "C29") (pin "1") (pinfunction "1_1") (pintype "input"))
      (node (ref "R27") (pin "2") (pinfunction "2_2") (pintype "unspecified"))
      (node (ref "U8") (pin "10") (pinfunction "AINB_10") (pintype "unspecified"))
      (node (ref "U8") (pin "3") (pinfunction "AINA_3") (pintype "unspecified"))
    )
    (net (code "106") (name "Net-(C30-Pad1)") (class "Default")
      (node (ref "C30") (pin "1") (pinfunction "1_1") (pintype "input"))
      (node (ref "R26") (pin "2") (pinfunction "2_2") (pintype "unspecified"))
      (node (ref "R27") (pin "1") (pinfunction "1_1") (pintype "unspecified"))
    )
    (net (code "107") (name "Net-(C59-Pad1)") (class "Default")
      (node (ref "C59") (pin "1") (pinfunction "1_1") (pintype "input"))
      (node (ref "P3") (pin "46") (pinfunction "46_46") (pintype "unspecified"))
      (node (ref "P3") (pin "6") (pinfunction "6_6") (pintype "unspecified"))
      (node (ref "R44") (pin "1") (pinfunction "1_1") (pintype "unspecified"))
      (node (ref "R45") (pin "2") (pinfunction "2_2") (pintype "unspecified"))
    )
    (net (code "108") (name "Net-(C100-Pad2)") (class "Default")
      (node (ref "C100") (pin "2") (pinfunction "2_2") (pintype "input"))
      (node (ref "C101") (pin "1") (pinfunction "1_1") (pintype "input"))
      (node (ref "C116") (pin "1") (pinfunction "1_1") (pintype "input"))
      (node (ref "C131") (pin "1") (pinfunction "1_1") (pintype "input"))
      (node (ref "C132") (pin "2") (pinfunction "2_2") (pintype "input"))
      (node (ref "R71") (pin "2") (pinfunction "2_2") (pintype "unspecified"))
      (node (ref "RF1") (pin "1") (pinfunction "1_1") (pintype "unspecified"))
      (node (ref "RF1") (pin "2") (pinfunction "2_2") (pintype "unspecified"))
      (node (ref "RF1") (pin "3") (pinfunction "3_3") (pintype "unspecified"))
      (node (ref "RF1") (pin "4") (pinfunction "4_4") (pintype "unspecified"))
      (node (ref "RF2") (pin "1") (pinfunction "1_1") (pintype "unspecified"))
      (node (ref "RF2") (pin "2") (pinfunction "2_2") (pintype "unspecified"))
      (node (ref "RF2") (pin "3") (pinfunction "3_3") (pintype "unspecified"))
      (node (ref "RF2") (pin "4") (pinfunction "4_4") (pintype "unspecified"))
    )
    (net (code "109") (name "Net-(C102-Pad1)") (class "Default")
      (node (ref "C102") (pin "1") (pinfunction "1_1") (pintype "input"))
      (node (ref "C103") (pin "1") (pinfunction "1_1") (pintype "input"))
      (node (ref "C104") (pin "1") (pinfunction "1_1") (pintype "input"))
      (node (ref "C105") (pin "1") (pinfunction "1_1") (pintype "input"))
      (node (ref "R62") (pin "1") (pinfunction "1_1") (pintype "unspecified"))
      (node (ref "R63") (pin "2") (pinfunction "2_2") (pintype "unspecified"))
      (node (ref "R64") (pin "2") (pinfunction "2_2") (pintype "unspecified"))
      (node (ref "R65") (pin "2") (pinfunction "2_2") (pintype "unspecified"))
    )
    (net (code "110") (name "Net-(C102-Pad2)") (class "Default")
      (node (ref "C102") (pin "2") (pinfunction "2_2") (pintype "input"))
      (node (ref "C107") (pin "2") (pinfunction "2_2") (pintype "input"))
      (node (ref "C108") (pin "2") (pinfunction "2_2") (pintype "input"))
      (node (ref "K2") (pin "2") (pinfunction "2_2") (pintype "input"))
      (node (ref "K2") (pin "7") (pinfunction "7_7") (pintype "input"))
      (node (ref "R63") (pin "1") (pinfunction "1_1") (pintype "unspecified"))
      (node (ref "R66") (pin "1") (pinfunction "1_1") (pintype "unspecified"))
    )
    (net (code "111") (name "Net-(C103-Pad2)") (class "Default")
      (node (ref "C103") (pin "2") (pinfunction "2_2") (pintype "input"))
      (node (ref "C109") (pin "2") (pinfunction "2_2") (pintype "input"))
      (node (ref "C110") (pin "2") (pinfunction "2_2") (pintype "input"))
      (node (ref "K2") (pin "4") (pinfunction "4_4") (pintype "input"))
      (node (ref "K2") (pin "5") (pinfunction "5_5") (pintype "input"))
      (node (ref "R64") (pin "1") (pinfunction "1_1") (pintype "unspecified"))
      (node (ref "R67") (pin "1") (pinfunction "1_1") (pintype "unspecified"))
    )
    (net (code "112") (name "Net-(C104-Pad2)") (class "Default")
      (node (ref "C104") (pin "2") (pinfunction "2_2") (pintype "input"))
      (node (ref "C105") (pin "2") (pinfunction "2_2") (pintype "input"))
      (node (ref "K3") (pin "4") (pinfunction "4_4") (pintype "input"))
      (node (ref "K3") (pin "5") (pinfunction "5_5") (pintype "input"))
      (node (ref "R65") (pin "1") (pinfunction "1_1") (pintype "unspecified"))
      (node (ref "R68") (pin "2") (pinfunction "2_2") (pintype "unspecified"))
    )
    (net (code "113") (name "Net-(C122-Pad2)") (class "Default")
      (node (ref "C122") (pin "2") (pinfunction "2_2") (pintype "input"))
      (node (ref "C123") (pin "2") (pinfunction "2_2") (pintype "input"))
      (node (ref "C129") (pin "2") (pinfunction "2_2") (pintype "input"))
      (node (ref "K5") (pin "4") (pinfunction "4_4") (pintype "input"))
      (node (ref "K5") (pin "5") (pinfunction "5_5") (pintype "input"))
      (node (ref "R75") (pin "1") (pinfunction "1_1") (pintype "unspecified"))
      (node (ref "R78") (pin "1") (pinfunction "1_1") (pintype "unspecified"))
    )
    (net (code "114") (name "Net-(C124-Pad2)") (class "Default")
      (node (ref "C124") (pin "2") (pinfunction "2_2") (pintype "input"))
      (node (ref "C125") (pin "2") (pinfunction "2_2") (pintype "input"))
      (node (ref "C130") (pin "2") (pinfunction "2_2") (pintype "input"))
      (node (ref "K5") (pin "2") (pinfunction "2_2") (pintype "input"))
      (node (ref "K5") (pin "7") (pinfunction "7_7") (pintype "input"))
      (node (ref "R76") (pin "1") (pinfunction "1_1") (pintype "unspecified"))
      (node (ref "R79") (pin "1") (pinfunction "1_1") (pintype "unspecified"))
    )
    (net (code "115") (name "Net-(C127-Pad1)") (class "Default")
      (node (ref "C127") (pin "1") (pinfunction "1_1") (pintype "input"))
      (node (ref "C128") (pin "1") (pinfunction "1_1") (pintype "input"))
      (node (ref "C129") (pin "1") (pinfunction "1_1") (pintype "input"))
      (node (ref "C130") (pin "1") (pinfunction "1_1") (pintype "input"))
      (node (ref "R77") (pin "2") (pinfunction "2_2") (pintype "unspecified"))
      (node (ref "R78") (pin "2") (pinfunction "2_2") (pintype "unspecified"))
      (node (ref "R79") (pin "2") (pinfunction "2_2") (pintype "unspecified"))
      (node (ref "R80") (pin "1") (pinfunction "1_1") (pintype "unspecified"))
    )
    (net (code "116") (name "Net-(C127-Pad2)") (class "Default")
      (node (ref "C127") (pin "2") (pinfunction "2_2") (pintype "input"))
      (node (ref "C128") (pin "2") (pinfunction "2_2") (pintype "input"))
      (node (ref "K4") (pin "4") (pinfunction "4_4") (pintype "input"))
      (node (ref "K4") (pin "5") (pinfunction "5_5") (pintype "input"))
      (node (ref "R74") (pin "2") (pinfunction "2_2") (pintype "unspecified"))
      (node (ref "R77") (pin "1") (pinfunction "1_1") (pintype "unspecified"))
    )
    (net (code "117") (name "Net-(D6-A)") (class "Default")
      (node (ref "C89") (pin "2") (pinfunction "2_2") (pintype "input"))
      (node (ref "D6") (pin "1") (pinfunction "A_1") (pintype "unspecified"))
      (node (ref "L5") (pin "2") (pinfunction "2_2") (pintype "unspecified"))
      (node (ref "U15") (pin "1") (pinfunction "SW_1") (pintype "unspecified"))
    )
    (net (code "118") (name "Net-(D7-A)") (class "Default")
      (node (ref "C92") (pin "1") (pinfunction "1_1") (pintype "input"))
      (node (ref "D7") (pin "1") (pinfunction "A_1") (pintype "unspecified"))
      (node (ref "D9") (pin "2") (pinfunction "A_2") (pintype "unspecified"))
    )
    (net (code "119") (name "Net-(D7-K)") (class "Default")
      (node (ref "C89") (pin "1") (pinfunction "1_1") (pintype "input"))
      (node (ref "D7") (pin "2") (pinfunction "K_2") (pintype "unspecified"))
      (node (ref "D8") (pin "1") (pinfunction "A_1") (pintype "unspecified"))
    )
    (net (code "120") (name "Net-(D10-A)") (class "Default")
      (node (ref "D10") (pin "1") (pinfunction "A_1") (pintype "unspecified"))
      (node (ref "L6") (pin "2") (pinfunction "2_2") (pintype "unspecified"))
      (node (ref "U16") (pin "1") (pinfunction "SW_1") (pintype "unspecified"))
    )
    (net (code "121") (name "Net-(K1-Pad2)") (class "Default")
      (node (ref "K1") (pin "2") (pinfunction "2_2") (pintype "input"))
      (node (ref "K1") (pin "7") (pinfunction "7_7") (pintype "input"))
      (node (ref "R70") (pin "2") (pinfunction "2_2") (pintype "unspecified"))
    )
    (net (code "122") (name "Net-(K2-Pad3)") (class "Default")
      (node (ref "K2") (pin "3") (pinfunction "3_3") (pintype "input"))
      (node (ref "K2") (pin "6") (pinfunction "6_6") (pintype "input"))
      (node (ref "K3") (pin "2") (pinfunction "2_2") (pintype "input"))
      (node (ref "K3") (pin "7") (pinfunction "7_7") (pintype "input"))
    )
    (net (code "123") (name "Net-(K4-Pad2)") (class "Default")
      (node (ref "K4") (pin "2") (pinfunction "2_2") (pintype "input"))
      (node (ref "K4") (pin "7") (pinfunction "7_7") (pintype "input"))
      (node (ref "K5") (pin "3") (pinfunction "3_3") (pintype "input"))
      (node (ref "K5") (pin "6") (pinfunction "6_6") (pintype "input"))
    )
    (net (code "124") (name "Net-(K6-Pad2)") (class "Default")
      (node (ref "K6") (pin "2") (pinfunction "2_2") (pintype "input"))
      (node (ref "K6") (pin "7") (pinfunction "7_7") (pintype "input"))
      (node (ref "R72") (pin "2") (pinfunction "2_2") (pintype "unspecified"))
    )
    (net (code "125") (name "Net-(LED1-Pad2)") (class "Default")
      (node (ref "LED1") (pin "2") (pinfunction "2_2") (pintype "unspecified"))
      (node (ref "R49") (pin "2") (pinfunction "2_2") (pintype "unspecified"))
    )
    (net (code "126") (name "Net-(LED2-Pad1)") (class "Default")
      (node (ref "LED2") (pin "1") (pinfunction "1_1") (pintype "unspecified"))
      (node (ref "R50") (pin "1") (pinfunction "1_1") (pintype "unspecified"))
    )
    (net (code "127") (name "Net-(P2-CD{slash}DAT3)") (class "Default")
      (node (ref "P2") (pin "2") (pinfunction "CD/DAT3_2") (pintype "unspecified"))
      (node (ref "R37") (pin "1") (pinfunction "1_1") (pintype "unspecified"))
      (node (ref "U1") (pin "54") (pinfunction "PF4/SDC0_D3/UART0_TX_54") (pintype "unspecified"))
    )
    (net (code "128") (name "Net-(P2-CLK)") (class "Default")
      (node (ref "P2") (pin "5") (pinfunction "CLK_5") (pintype "unspecified"))
      (node (ref "R39") (pin "1") (pinfunction "1_1") (pintype "unspecified"))
      (node (ref "U1") (pin "56") (pinfunction "PF2/SDC0_CLK/UART0_RX_56") (pintype "unspecified"))
    )
    (net (code "129") (name "Net-(P2-CMD)") (class "Default")
      (node (ref "P2") (pin "3") (pinfunction "CMD_3") (pintype "unspecified"))
      (node (ref "R38") (pin "1") (pinfunction "1_1") (pintype "unspecified"))
      (node (ref "U1") (pin "55") (pinfunction "PF3/SDC0_CMD/DBG_DO_55") (pintype "unspecified"))
    )
    (net (code "130") (name "Net-(P2-DAT0)") (class "Default")
      (node (ref "P2") (pin "7") (pinfunction "DAT0_7") (pintype "unspecified"))
      (node (ref "R40") (pin "1") (pinfunction "1_1") (pintype "unspecified"))
      (node (ref "U1") (pin "57") (pinfunction "PF1/SDC0_D0/DBG_DI_57") (pintype "unspecified"))
    )
    (net (code "131") (name "Net-(P2-DAT1)") (class "Default")
      (node (ref "P2") (pin "8") (pinfunction "DAT1_8") (pintype "unspecified"))
      (node (ref "R41") (pin "1") (pinfunction "1_1") (pintype "unspecified"))
      (node (ref "U1") (pin "58") (pinfunction "PF0/SDC0_D1/DBG_MS/IR_RX_58") (pintype "unspecified"))
    )
    (net (code "132") (name "Net-(P2-DAT2)") (class "Default")
      (node (ref "P2") (pin "1") (pinfunction "DAT2_1") (pintype "unspecified"))
      (node (ref "R36") (pin "1") (pinfunction "1_1") (pintype "unspecified"))
      (node (ref "U1") (pin "53") (pinfunction "PF5/SDC0_D2/DBG_CK/PWM1_53") (pintype "unspecified"))
    )
    (net (code "133") (name "Net-(Q1-C)") (class "Default")
      (node (ref "K1") (pin "1") (pinfunction "1_1") (pintype "input"))
      (node (ref "Q1") (pin "3") (pinfunction "C_3") (pintype "input"))
    )
    (net (code "134") (name "Net-(Q2-C)") (class "Default")
      (node (ref "K2") (pin "1") (pinfunction "1_1") (pintype "input"))
      (node (ref "Q2") (pin "3") (pinfunction "C_3") (pintype "input"))
    )
    (net (code "135") (name "Net-(Q3-C)") (class "Default")
      (node (ref "K3") (pin "1") (pinfunction "1_1") (pintype "input"))
      (node (ref "Q3") (pin "3") (pinfunction "C_3") (pintype "input"))
    )
    (net (code "136") (name "Net-(Q4-C)") (class "Default")
      (node (ref "K4") (pin "1") (pinfunction "1_1") (pintype "input"))
      (node (ref "Q4") (pin "3") (pinfunction "C_3") (pintype "input"))
    )
    (net (code "137") (name "Net-(Q5-C)") (class "Default")
      (node (ref "K5") (pin "1") (pinfunction "1_1") (pintype "input"))
      (node (ref "Q5") (pin "3") (pinfunction "C_3") (pintype "input"))
    )
    (net (code "138") (name "Net-(Q6-C)") (class "Default")
      (node (ref "K6") (pin "1") (pinfunction "1_1") (pintype "input"))
      (node (ref "Q6") (pin "3") (pinfunction "C_3") (pintype "input"))
    )
    (net (code "139") (name "Net-(R15-Pad2)") (class "Default")
      (node (ref "R15") (pin "2") (pinfunction "2_2") (pintype "unspecified"))
      (node (ref "U3") (pin "125") (pinfunction "IO_125") (pintype "input"))
    )
    (net (code "140") (name "Net-(R22-Pad2)") (class "Default")
      (node (ref "R22") (pin "2") (pinfunction "2_2") (pintype "unspecified"))
      (node (ref "U7") (pin "11") (pinfunction "AINB_11") (pintype "unspecified"))
      (node (ref "U7") (pin "2") (pinfunction "AINA_2") (pintype "unspecified"))
    )
    (net (code "141") (name "Net-(R23-Pad2)") (class "Default")
      (node (ref "R23") (pin "2") (pinfunction "2_2") (pintype "unspecified"))
      (node (ref "U8") (pin "11") (pinfunction "AINB_11") (pintype "unspecified"))
      (node (ref "U8") (pin "2") (pinfunction "AINA_2") (pintype "unspecified"))
    )
    (net (code "142") (name "Net-(S1-P)") (class "Default")
      (node (ref "D4") (pin "2") (pinfunction "2_2") (pintype "unspecified"))
      (node (ref "D5") (pin "2") (pinfunction "2_2") (pintype "unspecified"))
      (node (ref "S1") (pin "2") (pinfunction "P_2") (pintype "unspecified"))
      (node (ref "U13") (pin "1") (pinfunction "CATHODE_1") (pintype "unspecified"))
      (node (ref "U13") (pin "2") (pinfunction "REF_2") (pintype "unspecified"))
    )
    (net (code "143") (name "Net-(U1-HOSCI)") (class "Default")
      (node (ref "C32") (pin "1") (pinfunction "1_1") (pintype "input"))
      (node (ref "U1") (pin "51") (pinfunction "HOSCI_51") (pintype "unspecified"))
      (node (ref "X1") (pin "2") (pinfunction "OSC2_2") (pintype "input"))
    )
    (net (code "144") (name "Net-(U1-HOSCO)") (class "Default")
      (node (ref "C31") (pin "1") (pinfunction "1_1") (pintype "input"))
      (node (ref "U1") (pin "52") (pinfunction "HOSCO_52") (pintype "unspecified"))
      (node (ref "X1") (pin "1") (pinfunction "OSC1_1") (pintype "input"))
    )
    (net (code "145") (name "Net-(U1-PA0{slash}TPX1{slash}DA_BCLK{slash}UART1_RTS{slash}SPI1_CS)") (class "Default")
      (node (ref "P1") (pin "1") (pinfunction "1_1") (pintype "unspecified"))
      (node (ref "U1") (pin "66") (pinfunction "PA0/TPX1/DA_BCLK/UART1_RTS/SPI1_CS_66") (pintype "unspecified"))
    )
    (net (code "146") (name "Net-(U1-PA1{slash}TPX2{slash}DA_LRCK{slash}UART1_CTS{slash}SPI1_MOSI)") (class "Default")
      (node (ref "P1") (pin "4") (pinfunction "4_4") (pintype "unspecified"))
      (node (ref "U1") (pin "65") (pinfunction "PA1/TPX2/DA_LRCK/UART1_CTS/SPI1_MOSI_65") (pintype "unspecified"))
    )
    (net (code "147") (name "Net-(U1-PA2{slash}TPY1{slash}PWM0{slash}DA_IN{slash}UART1_RX{slash}SPI1_CLK)") (class "Default")
      (node (ref "C57") (pin "1") (pinfunction "1_1") (pintype "input"))
      (node (ref "P1") (pin "5") (pinfunction "5_5") (pintype "unspecified"))
      (node (ref "R34") (pin "1") (pinfunction "1_1") (pintype "unspecified"))
      (node (ref "U1") (pin "64") (pinfunction "PA2/TPY1/PWM0/DA_IN/UART1_RX/SPI1_CLK_64") (pintype "unspecified"))
    )
    (net (code "148") (name "Net-(U1-PA3{slash}TPY2{slash}IR_RX{slash}DA_OUT{slash}UART1_TX{slash}SPI1_MISO)") (class "Default")
      (node (ref "C57") (pin "2") (pinfunction "2_2") (pintype "input"))
      (node (ref "P1") (pin "6") (pinfunction "6_6") (pintype "unspecified"))
      (node (ref "R35") (pin "1") (pinfunction "1_1") (pintype "unspecified"))
      (node (ref "U1") (pin "63") (pinfunction "PA3/TPY2/IR_RX/DA_OUT/UART1_TX/SPI1_MISO_63") (pintype "unspecified"))
    )
    (net (code "149") (name "Net-(U1-RESET)") (class "Default")
      (node (ref "R30") (pin "1") (pinfunction "1_1") (pintype "unspecified"))
      (node (ref "U1") (pin "70") (pinfunction "RESET_70") (pintype "unspecified"))
    )
    (net (code "150") (name "Net-(U1-SVREF)") (class "Default")
      (node (ref "C46") (pin "1") (pinfunction "1_1") (pintype "input"))
      (node (ref "R28") (pin "1") (pinfunction "1_1") (pintype "unspecified"))
      (node (ref "R29") (pin "2") (pinfunction "2_2") (pintype "unspecified"))
      (node (ref "U1") (pin "33") (pinfunction "SVREF_33") (pintype "unspecified"))
    )
    (net (code "151") (name "Net-(U1-VRA1)") (class "Default")
      (node (ref "C55") (pin "1") (pinfunction "1_1") (pintype "input"))
      (node (ref "R31") (pin "2") (pinfunction "2_2") (pintype "unspecified"))
      (node (ref "U1") (pin "81") (pinfunction "VRA1_81") (pintype "unspecified"))
    )
    (net (code "152") (name "Net-(U1-VRA2)") (class "Default")
      (node (ref "C56") (pin "1") (pinfunction "1_1") (pintype "input"))
      (node (ref "R32") (pin "2") (pinfunction "2_2") (pintype "unspecified"))
      (node (ref "U1") (pin "83") (pinfunction "VRA2_83") (pintype "unspecified"))
    )
    (net (code "153") (name "Net-(U2-VCC)") (class "Default")
      (node (ref "D3") (pin "1") (pinfunction "1_1") (pintype "unspecified"))
      (node (ref "J1") (pin "4") (pinfunction "4_4") (pintype "input"))
      (node (ref "R33") (pin "2") (pinfunction "2_2") (pintype "unspecified"))
      (node (ref "U2") (pin "3") (pinfunction "/WP_3") (pintype "unspecified"))
      (node (ref "U2") (pin "7") (pinfunction "/HOLD_7") (pintype "unspecified"))
      (node (ref "U2") (pin "8") (pinfunction "VCC_8") (pintype "unspecified"))
    )
    (net (code "154") (name "Net-(U3-(DQ1T),(DATA2),DIFFIO_T10n,IO)") (class "Default")
      (node (ref "R20") (pin "2") (pinfunction "2_2") (pintype "unspecified"))
      (node (ref "U3") (pin "132") (pinfunction "(DQ1T),(DATA2),DIFFIO_T10n,IO_132") (pintype "input"))
    )
    (net (code "155") (name "Net-(U3-(DQ1T),(DATA3),DIFFIO_T10p,IO)") (class "Default")
      (node (ref "R21") (pin "2") (pinfunction "2_2") (pintype "unspecified"))
      (node (ref "U3") (pin "133") (pinfunction "(DQ1T),(DATA3),DIFFIO_T10p,IO_133") (pintype "input"))
    )
    (net (code "156") (name "Net-(U3-CLK1,DIFFCLK_0n)") (class "Default")
      (node (ref "R4") (pin "1") (pinfunction "1_1") (pintype "unspecified"))
      (node (ref "U3") (pin "23") (pinfunction "CLK1,DIFFCLK_0n_23") (pintype "input"))
    )
    (net (code "157") (name "Net-(U3-CLK3,DIFFCLK_1n)") (class "Default")
      (node (ref "C13") (pin "1") (pinfunction "1_1") (pintype "input"))
      (node (ref "R5") (pin "2") (pinfunction "2_2") (pintype "unspecified"))
      (node (ref "U3") (pin "25") (pinfunction "CLK3,DIFFCLK_1n_25") (pintype "input"))
    )
    (net (code "158") (name "Net-(U3-CONF_DONE)") (class "Default")
      (node (ref "R12") (pin "2") (pinfunction "2_2") (pintype "unspecified"))
      (node (ref "U3") (pin "92") (pinfunction "CONF_DONE_92") (pintype "input"))
    )
    (net (code "159") (name "Net-(U3-DIFFIO_T11n,IO)") (class "Default")
      (node (ref "R18") (pin "2") (pinfunction "2_2") (pintype "unspecified"))
      (node (ref "U3") (pin "128") (pinfunction "DIFFIO_T11n,IO_128") (pintype "input"))
    )
    (net (code "160") (name "Net-(U3-DIFFIO_T11p,IO)") (class "Default")
      (node (ref "R19") (pin "2") (pinfunction "2_2") (pintype "unspecified"))
      (node (ref "U3") (pin "129") (pinfunction "DIFFIO_T11p,IO_129") (pintype "input"))
    )
    (net (code "161") (name "Net-(U3-DIFFIO_T12n,IO)") (class "Default")
      (node (ref "R16") (pin "2") (pinfunction "2_2") (pintype "unspecified"))
      (node (ref "U3") (pin "126") (pinfunction "DIFFIO_T12n,IO_126") (pintype "input"))
    )
    (net (code "162") (name "Net-(U3-DIFFIO_T12p,IO)") (class "Default")
      (node (ref "R17") (pin "2") (pinfunction "2_2") (pintype "unspecified"))
      (node (ref "U3") (pin "127") (pinfunction "DIFFIO_T12p,IO_127") (pintype "input"))
    )
    (net (code "163") (name "Net-(U3-DIFFIO_T13p,IO)") (class "Default")
      (node (ref "R14") (pin "2") (pinfunction "2_2") (pintype "unspecified"))
      (node (ref "U3") (pin "124") (pinfunction "DIFFIO_T13p,IO_124") (pintype "input"))
    )
    (net (code "164") (name "Net-(U3-DIFFIO_T16p,IO)") (class "Default")
      (node (ref "R13") (pin "2") (pinfunction "2_2") (pintype "unspecified"))
      (node (ref "U3") (pin "121") (pinfunction "DIFFIO_T16p,IO_121") (pintype "input"))
    )
    (net (code "165") (name "Net-(U3-GNDA1)") (class "Default")
      (node (ref "C2") (pin "2") (pinfunction "2_2") (pintype "input"))
      (node (ref "C5") (pin "2") (pinfunction "2_2") (pintype "input"))
      (node (ref "L2") (pin "2") (pinfunction "2_2") (pintype "unspecified"))
      (node (ref "U3") (pin "36") (pinfunction "GNDA1_36") (pintype "input"))
    )
    (net (code "166") (name "Net-(U3-GNDA2)") (class "Default")
      (node (ref "C3") (pin "2") (pinfunction "2_2") (pintype "input"))
      (node (ref "C6") (pin "1") (pinfunction "1_1") (pintype "input"))
      (node (ref "L3") (pin "2") (pinfunction "2_2") (pintype "unspecified"))
      (node (ref "U3") (pin "108") (pinfunction "GNDA2_108") (pintype "input"))
    )
    (net (code "167") (name "Net-(U3-TCK)") (class "Default")
      (node (ref "R7") (pin "1") (pinfunction "1_1") (pintype "unspecified"))
      (node (ref "U3") (pin "16") (pinfunction "TCK_16") (pintype "input"))
    )
    (net (code "168") (name "Net-(U3-TDI)") (class "Default")
      (node (ref "R9") (pin "2") (pinfunction "2_2") (pintype "unspecified"))
      (node (ref "U3") (pin "15") (pinfunction "TDI_15") (pintype "input"))
    )
    (net (code "169") (name "Net-(U3-TMS)") (class "Default")
      (node (ref "R10") (pin "2") (pinfunction "2_2") (pintype "unspecified"))
      (node (ref "U3") (pin "18") (pinfunction "TMS_18") (pintype "input"))
    )
    (net (code "170") (name "Net-(U3-VCCD_PLL1)") (class "Default")
      (node (ref "C2") (pin "1") (pinfunction "1_1") (pintype "input"))
      (node (ref "L1") (pin "2") (pinfunction "2_2") (pintype "unspecified"))
      (node (ref "U3") (pin "37") (pinfunction "VCCD_PLL1_37") (pintype "input"))
    )
    (net (code "171") (name "Net-(U3-VCCD_PLL2)") (class "Default")
      (node (ref "C3") (pin "1") (pinfunction "1_1") (pintype "input"))
      (node (ref "L4") (pin "2") (pinfunction "2_2") (pintype "unspecified"))
      (node (ref "U3") (pin "109") (pinfunction "VCCD_PLL2_109") (pintype "input"))
    )
    (net (code "172") (name "Net-(U3-nCE)") (class "Default")
      (node (ref "R6") (pin "1") (pinfunction "1_1") (pintype "unspecified"))
      (node (ref "U3") (pin "21") (pinfunction "nCE_21") (pintype "input"))
    )
    (net (code "173") (name "Net-(U3-nCONFIG)") (class "Default")
      (node (ref "R11") (pin "2") (pinfunction "2_2") (pintype "unspecified"))
      (node (ref "U3") (pin "14") (pinfunction "nCONFIG_14") (pintype "input"))
    )
    (net (code "174") (name "Net-(U3-nSTATUS)") (class "Default")
      (node (ref "R8") (pin "2") (pinfunction "2_2") (pintype "unspecified"))
      (node (ref "U3") (pin "9") (pinfunction "nSTATUS_9") (pintype "input"))
    )
    (net (code "175") (name "Net-(U4-DO)") (class "Default")
      (node (ref "R1") (pin "2") (pinfunction "2_2") (pintype "unspecified"))
      (node (ref "U4") (pin "2") (pinfunction "DO_2") (pintype "unspecified"))
    )
    (net (code "176") (name "Net-(U4-VCC)") (class "Default")
      (node (ref "D1") (pin "1") (pinfunction "1_1") (pintype "unspecified"))
      (node (ref "J2") (pin "4") (pinfunction "4_4") (pintype "input"))
      (node (ref "U4") (pin "3") (pinfunction "/WP_3") (pintype "unspecified"))
      (node (ref "U4") (pin "7") (pinfunction "/HOLD_7") (pintype "unspecified"))
      (node (ref "U4") (pin "8") (pinfunction "VCC_8") (pintype "unspecified"))
    )
    (net (code "177") (name "Net-(U5-VCC)") (class "Default")
      (node (ref "D2") (pin "1") (pinfunction "1_1") (pintype "unspecified"))
      (node (ref "J3") (pin "2") (pinfunction "2_2") (pintype "input"))
      (node (ref "R2") (pin "2") (pinfunction "2_2") (pintype "unspecified"))
      (node (ref "R3") (pin "2") (pinfunction "2_2") (pintype "unspecified"))
      (node (ref "U5") (pin "8") (pinfunction "VCC_8") (pintype "unspecified"))
    )
    (net (code "178") (name "Net-(U6-ADJ)") (class "Default")
      (node (ref "R54") (pin "1") (pinfunction "1_1") (pintype "unspecified"))
      (node (ref "R55") (pin "2") (pinfunction "2_2") (pintype "unspecified"))
      (node (ref "U6") (pin "5") (pinfunction "ADJ_5") (pintype "unspecified"))
    )
    (net (code "179") (name "Net-(U7-REFINA)") (class "Default")
      (node (ref "C23") (pin "1") (pinfunction "1_1") (pintype "input"))
      (node (ref "U7") (pin "5") (pinfunction "REFINA_5") (pintype "unspecified"))
      (node (ref "U7") (pin "6") (pinfunction "REFOUT_6") (pintype "output"))
      (node (ref "U7") (pin "7") (pinfunction "REFINB_7") (pintype "unspecified"))
    )
    (net (code "180") (name "Net-(U8-REFINA)") (class "Default")
      (node (ref "C24") (pin "1") (pinfunction "1_1") (pintype "input"))
      (node (ref "U8") (pin "5") (pinfunction "REFINA_5") (pintype "unspecified"))
      (node (ref "U8") (pin "6") (pinfunction "REFOUT_6") (pintype "output"))
      (node (ref "U8") (pin "7") (pinfunction "REFINB_7") (pintype "unspecified"))
    )
    (net (code "181") (name "Net-(U9-PROG)") (class "Default")
      (node (ref "R47") (pin "2") (pinfunction "2_2") (pintype "unspecified"))
      (node (ref "U9") (pin "2") (pinfunction "PROG_2") (pintype "unspecified"))
    )
    (net (code "182") (name "Net-(U9-STDBY#)") (class "Default")
      (node (ref "R49") (pin "1") (pinfunction "1_1") (pintype "unspecified"))
      (node (ref "U9") (pin "6") (pinfunction "STDBY#_6") (pintype "unspecified"))
    )
    (net (code "183") (name "Net-(U10-PROG)") (class "Default")
      (node (ref "R46") (pin "2") (pinfunction "2_2") (pintype "unspecified"))
      (node (ref "U10") (pin "2") (pinfunction "PROG_2") (pintype "unspecified"))
    )
    (net (code "184") (name "Net-(U15-FB)") (class "Default")
      (node (ref "R56") (pin "1") (pinfunction "1_1") (pintype "unspecified"))
      (node (ref "R57") (pin "2") (pinfunction "2_2") (pintype "unspecified"))
      (node (ref "U15") (pin "3") (pinfunction "FB_3") (pintype "unspecified"))
    )
    (net (code "185") (name "Net-(U17-+IN)") (class "Default")
      (node (ref "K3") (pin "3") (pinfunction "3_3") (pintype "input"))
      (node (ref "K3") (pin "6") (pinfunction "6_6") (pintype "input"))
      (node (ref "U17") (pin "3") (pinfunction "+IN_3") (pintype "unspecified"))
    )
    (net (code "186") (name "Net-(U17--IN)") (class "Default")
      (node (ref "C114") (pin "2") (pinfunction "2_2") (pintype "input"))
      (node (ref "K1") (pin "3") (pinfunction "3_3") (pintype "input"))
      (node (ref "K1") (pin "6") (pinfunction "6_6") (pintype "input"))
      (node (ref "R69") (pin "1") (pinfunction "1_1") (pintype "unspecified"))
      (node (ref "U17") (pin "4") (pinfunction "-IN_4") (pintype "unspecified"))
    )
    (net (code "187") (name "Net-(U18-S)") (class "Default")
      (node (ref "C99") (pin "2") (pinfunction "2_2") (pintype "input"))
      (node (ref "R62") (pin "2") (pinfunction "2_2") (pintype "unspecified"))
      (node (ref "U18") (pin "4") (pinfunction "S_4") (pintype "unspecified"))
    )
    (net (code "188") (name "Net-(U18-S1)") (class "Default")
      (node (ref "C99") (pin "1") (pinfunction "1_1") (pintype "input"))
      (node (ref "RF1") (pin "5") (pinfunction "5_5") (pintype "unspecified"))
      (node (ref "U18") (pin "3") (pinfunction "S1_3") (pintype "unspecified"))
    )
    (net (code "189") (name "Net-(U19-S)") (class "Default")
      (node (ref "C133") (pin "2") (pinfunction "2_2") (pintype "input"))
      (node (ref "R80") (pin "2") (pinfunction "2_2") (pintype "unspecified"))
      (node (ref "U19") (pin "4") (pinfunction "S_4") (pintype "unspecified"))
    )
    (net (code "190") (name "Net-(U19-S1)") (class "Default")
      (node (ref "C133") (pin "1") (pinfunction "1_1") (pintype "input"))
      (node (ref "RF2") (pin "5") (pinfunction "5_5") (pintype "unspecified"))
      (node (ref "U19") (pin "3") (pinfunction "S1_3") (pintype "unspecified"))
    )
    (net (code "191") (name "Net-(U20-+IN)") (class "Default")
      (node (ref "K4") (pin "3") (pinfunction "3_3") (pintype "input"))
      (node (ref "K4") (pin "6") (pinfunction "6_6") (pintype "input"))
      (node (ref "U20") (pin "3") (pinfunction "+IN_3") (pintype "unspecified"))
    )
    (net (code "192") (name "Net-(U20--IN)") (class "Default")
      (node (ref "C118") (pin "2") (pinfunction "2_2") (pintype "input"))
      (node (ref "K6") (pin "3") (pinfunction "3_3") (pintype "input"))
      (node (ref "K6") (pin "6") (pinfunction "6_6") (pintype "input"))
      (node (ref "R73") (pin "1") (pinfunction "1_1") (pintype "unspecified"))
      (node (ref "U20") (pin "4") (pinfunction "-IN_4") (pintype "unspecified"))
    )
    (net (code "193") (name "Net-(U21-CATHODE)") (class "Default")
      (node (ref "R81") (pin "2") (pinfunction "2_2") (pintype "unspecified"))
      (node (ref "R82") (pin "1") (pinfunction "1_1") (pintype "unspecified"))
      (node (ref "U21") (pin "1") (pinfunction "CATHODE_1") (pintype "unspecified"))
      (node (ref "U21") (pin "2") (pinfunction "REF_2") (pintype "unspecified"))
    )
    (net (code "194") (name "Net-(X2-OUT)") (class "Default")
      (node (ref "R4") (pin "2") (pinfunction "2_2") (pintype "unspecified"))
      (node (ref "X2") (pin "3") (pinfunction "OUT_3") (pintype "unspecified"))
    )
    (net (code "195") (name "POWER_ENABLE") (class "Default")
      (node (ref "C67") (pin "1") (pinfunction "1_1") (pintype "input"))
      (node (ref "D4") (pin "1") (pinfunction "1_1") (pintype "unspecified"))
      (node (ref "R52") (pin "2") (pinfunction "2_2") (pintype "unspecified"))
      (node (ref "U6") (pin "1") (pinfunction "EN_1") (pintype "unspecified"))
    )
    (net (code "196") (name "POWER_ON") (class "Default")
      (node (ref "D5") (pin "1") (pinfunction "1_1") (pintype "unspecified"))
      (node (ref "R53") (pin "2") (pinfunction "2_2") (pintype "unspecified"))
      (node (ref "U1") (pin "38") (pinfunction "PE11/CLK_OUT/TWI0_SCK/IR_RX_38") (pintype "unspecified"))
    )
    (net (code "197") (name "USB-DM") (class "Default")
      (node (ref "U1") (pin "68") (pinfunction "USB-DM_68") (pintype "unspecified"))
      (node (ref "USB1") (pin "A7") (pinfunction "DN1_A7") (pintype "unspecified"))
      (node (ref "USB1") (pin "B7") (pinfunction "DN2_B7") (pintype "unspecified"))
    )
    (net (code "198") (name "USB-DP") (class "Default")
      (node (ref "U1") (pin "69") (pinfunction "USB-DP_69") (pintype "unspecified"))
      (node (ref "USB1") (pin "A6") (pinfunction "DP1_A6") (pintype "unspecified"))
      (node (ref "USB1") (pin "B6") (pinfunction "DP2_B6") (pintype "unspecified"))
    )
    (net (code "199") (name "VBAT") (class "Default")
      (node (ref "C65") (pin "1") (pinfunction "1_1") (pintype "input"))
      (node (ref "C68") (pin "1") (pinfunction "1_1") (pintype "input"))
      (node (ref "C69") (pin "1") (pinfunction "1_1") (pintype "input"))
      (node (ref "C70") (pin "1") (pinfunction "1_1") (pintype "input"))
      (node (ref "C71") (pin "1") (pinfunction "1_1") (pintype "input"))
      (node (ref "C72") (pin "1") (pinfunction "1_1") (pintype "input"))
      (node (ref "C95") (pin "1") (pinfunction "1_1") (pintype "input"))
      (node (ref "C96") (pin "1") (pinfunction "1_1") (pintype "input"))
      (node (ref "CON1") (pin "1") (pinfunction "1_1") (pintype "bidirectional"))
      (node (ref "L6") (pin "1") (pinfunction "1_1") (pintype "unspecified"))
      (node (ref "S1") (pin "3") (pinfunction "S_3") (pintype "unspecified"))
      (node (ref "U10") (pin "5") (pinfunction "BAT_5") (pintype "unspecified"))
      (node (ref "U16") (pin "6") (pinfunction "IN_6") (pintype "unspecified"))
      (node (ref "U6") (pin "2") (pinfunction "in_2") (pintype "unspecified"))
      (node (ref "U9") (pin "5") (pinfunction "BAT_5") (pintype "unspecified"))
    )
    (net (code "200") (name "VREF") (class "Default")
      (node (ref "C66") (pin "1") (pinfunction "1_1") (pintype "input"))
      (node (ref "R51") (pin "2") (pinfunction "2_2") (pintype "unspecified"))
      (node (ref "U1") (pin "79") (pinfunction "LRADC0_79") (pintype "unspecified"))
      (node (ref "U13") (pin "3") (pinfunction "ANODE_3") (pintype "unspecified"))
    )
    (net (code "201") (name "VRF1") (class "Default")
      (node (ref "C106") (pin "2") (pinfunction "2_2") (pintype "input"))
      (node (ref "C107") (pin "1") (pinfunction "1_1") (pintype "input"))
      (node (ref "C108") (pin "1") (pinfunction "1_1") (pintype "input"))
      (node (ref "C109") (pin "1") (pinfunction "1_1") (pintype "input"))
      (node (ref "C110") (pin "1") (pinfunction "1_1") (pintype "input"))
      (node (ref "C111") (pin "2") (pinfunction "2_2") (pintype "input"))
      (node (ref "C115") (pin "2") (pinfunction "2_2") (pintype "input"))
      (node (ref "C116") (pin "2") (pinfunction "2_2") (pintype "input"))
      (node (ref "C117") (pin "2") (pinfunction "2_2") (pintype "input"))
      (node (ref "C121") (pin "2") (pinfunction "2_2") (pintype "input"))
      (node (ref "C122") (pin "1") (pinfunction "1_1") (pintype "input"))
      (node (ref "C123") (pin "1") (pinfunction "1_1") (pintype "input"))
      (node (ref "C124") (pin "1") (pinfunction "1_1") (pintype "input"))
      (node (ref "C125") (pin "1") (pinfunction "1_1") (pintype "input"))
      (node (ref "C126") (pin "2") (pinfunction "2_2") (pintype "input"))
      (node (ref "C134") (pin "2") (pinfunction "2_2") (pintype "input"))
      (node (ref "C135") (pin "2") (pinfunction "2_2") (pintype "input"))
      (node (ref "D11") (pin "1") (pinfunction "1_1") (pintype "unspecified"))
      (node (ref "D12") (pin "2") (pinfunction "2_2") (pintype "unspecified"))
      (node (ref "R66") (pin "2") (pinfunction "2_2") (pintype "unspecified"))
      (node (ref "R67") (pin "2") (pinfunction "2_2") (pintype "unspecified"))
      (node (ref "R68") (pin "1") (pinfunction "1_1") (pintype "unspecified"))
      (node (ref "R70") (pin "1") (pinfunction "1_1") (pintype "unspecified"))
      (node (ref "R71") (pin "1") (pinfunction "1_1") (pintype "unspecified"))
      (node (ref "R72") (pin "1") (pinfunction "1_1") (pintype "unspecified"))
      (node (ref "R74") (pin "1") (pinfunction "1_1") (pintype "unspecified"))
      (node (ref "R75") (pin "2") (pinfunction "2_2") (pintype "unspecified"))
      (node (ref "R76") (pin "2") (pinfunction "2_2") (pintype "unspecified"))
      (node (ref "R82") (pin "2") (pinfunction "2_2") (pintype "unspecified"))
    )
    (net (code "202") (name "VUSB") (class "Default")
      (node (ref "C60") (pin "1") (pinfunction "1_1") (pintype "input"))
      (node (ref "C61") (pin "1") (pinfunction "1_1") (pintype "input"))
      (node (ref "C62") (pin "1") (pinfunction "1_1") (pintype "input"))
      (node (ref "C63") (pin "1") (pinfunction "1_1") (pintype "input"))
      (node (ref "C64") (pin "1") (pinfunction "1_1") (pintype "input"))
      (node (ref "LED1") (pin "1") (pinfunction "1_1") (pintype "unspecified"))
      (node (ref "R50") (pin "2") (pinfunction "2_2") (pintype "unspecified"))
      (node (ref "U10") (pin "4") (pinfunction "VCC_4") (pintype "unspecified"))
      (node (ref "U10") (pin "8") (pinfunction "CE_8") (pintype "unspecified"))
      (node (ref "U9") (pin "4") (pinfunction "VCC_4") (pintype "unspecified"))
      (node (ref "U9") (pin "8") (pinfunction "CE_8") (pintype "unspecified"))
      (node (ref "USB1") (pin "A4") (pinfunction "VBUS_A4") (pintype "unspecified"))
      (node (ref "USB1") (pin "A9") (pinfunction "VBUS_A9") (pintype "unspecified"))
      (node (ref "USB1") (pin "B4") (pinfunction "VBUS_B4") (pintype "unspecified"))
      (node (ref "USB1") (pin "B9") (pinfunction "VBUS_B9") (pintype "unspecified"))
    )
    (net (code "203") (name "unconnected-(P3-Pad45)") (class "Default")
      (node (ref "P3") (pin "45") (pinfunction "45_45") (pintype "unspecified"))
    )
    (net (code "204") (name "unconnected-(S1-O-Pad1)") (class "Default")
      (node (ref "S1") (pin "1") (pinfunction "O_1") (pintype "unspecified"))
    )
    (net (code "205") (name "unconnected-(U1-FMINL-Pad84)") (class "Default")
      (node (ref "U1") (pin "84") (pinfunction "FMINL_84") (pintype "unspecified"))
    )
    (net (code "206") (name "unconnected-(U1-FMINR-Pad85)") (class "Default")
      (node (ref "U1") (pin "85") (pinfunction "FMINR_85") (pintype "unspecified"))
    )
    (net (code "207") (name "unconnected-(U1-HPCOM-Pad3)") (class "Default")
      (node (ref "U1") (pin "3") (pinfunction "HPCOM_3") (pintype "unspecified"))
    )
    (net (code "208") (name "unconnected-(U1-HPCOMFB-Pad2)") (class "Default")
      (node (ref "U1") (pin "2") (pinfunction "HPCOMFB_2") (pintype "unspecified"))
    )
    (net (code "209") (name "unconnected-(U1-HPL-Pad1)") (class "Default")
      (node (ref "U1") (pin "1") (pinfunction "HPL_1") (pintype "unspecified"))
    )
    (net (code "210") (name "unconnected-(U1-HPR-Pad88)") (class "Default")
      (node (ref "U1") (pin "88") (pinfunction "HPR_88") (pintype "unspecified"))
    )
    (net (code "211") (name "unconnected-(U1-HPVCC-Pad4)") (class "Default")
      (node (ref "U1") (pin "4") (pinfunction "HPVCC_4") (pintype "unspecified"))
    )
    (net (code "212") (name "unconnected-(U1-LINEIN-Pad86)") (class "Default")
      (node (ref "U1") (pin "86") (pinfunction "LINEIN_86") (pintype "unspecified"))
    )
    (net (code "213") (name "unconnected-(U1-MICIN-Pad87)") (class "Default")
      (node (ref "U1") (pin "87") (pinfunction "MICIN_87") (pintype "unspecified"))
    )
    (net (code "214") (name "unconnected-(U1-PD0{slash}LCD_D2{slash}TWI0_SDA-Pad6)") (class "Default")
      (node (ref "U1") (pin "6") (pinfunction "PD0/LCD_D2/TWI0_SDA_6") (pintype "unspecified"))
    )
    (net (code "215") (name "unconnected-(U1-PD12{slash}LCD_D18{slash}TWI0_SCK-Pad18)") (class "Default")
      (node (ref "U1") (pin "18") (pinfunction "PD12/LCD_D18/TWI0_SCK_18") (pintype "unspecified"))
    )
    (net (code "216") (name "unconnected-(U1-TVIN0-Pad78)") (class "Default")
      (node (ref "U1") (pin "78") (pinfunction "TVIN0_78") (pintype "unspecified"))
    )
    (net (code "217") (name "unconnected-(U1-TVIN1-Pad77)") (class "Default")
      (node (ref "U1") (pin "77") (pinfunction "TVIN1_77") (pintype "unspecified"))
    )
    (net (code "218") (name "unconnected-(U1-TVOUT-Pad72)") (class "Default")
      (node (ref "U1") (pin "72") (pinfunction "TVOUT_72") (pintype "unspecified"))
    )
    (net (code "219") (name "unconnected-(U1-TV_VCC-Pad73)") (class "Default")
      (node (ref "U1") (pin "73") (pinfunction "TV_VCC_73") (pintype "unspecified"))
    )
    (net (code "220") (name "unconnected-(U1-TV_VRN-Pad75)") (class "Default")
      (node (ref "U1") (pin "75") (pinfunction "TV_VRN_75") (pintype "unspecified"))
    )
    (net (code "221") (name "unconnected-(U1-TV_VRP-Pad76)") (class "Default")
      (node (ref "U1") (pin "76") (pinfunction "TV_VRP_76") (pintype "unspecified"))
    )
    (net (code "222") (name "unconnected-(U3-(DQ1B),DIFFIO_B9n,IO-Pad50)") (class "Default")
      (node (ref "U3") (pin "50") (pinfunction "(DQ1B),DIFFIO_B9n,IO_50") (pintype "input"))
    )
    (net (code "223") (name "unconnected-(U3-(DQ1B),DIFFIO_B9p,IO-Pad49)") (class "Default")
      (node (ref "U3") (pin "49") (pinfunction "(DQ1B),DIFFIO_B9p,IO_49") (pintype "input"))
    )
    (net (code "224") (name "unconnected-(U3-(DQ1B),DIFFIO_B10p,IO-Pad51)") (class "Default")
      (node (ref "U3") (pin "51") (pinfunction "(DQ1B),DIFFIO_B10p,IO_51") (pintype "input"))
    )
    (net (code "225") (name "unconnected-(U3-(DQ1T),DIFFIO_T16n,IO-Pad120)") (class "Default")
      (node (ref "U3") (pin "120") (pinfunction "(DQ1T),DIFFIO_T16n,IO_120") (pintype "input"))
    )
    (net (code "226") (name "unconnected-(U3-(DQ1T),RDN4,IO-Pad115)") (class "Default")
      (node (ref "U3") (pin "115") (pinfunction "(DQ1T),RDN4,IO_115") (pintype "input"))
    )
    (net (code "227") (name "unconnected-(U3-(DQ1T),RUP4,IO-Pad114)") (class "Default")
      (node (ref "U3") (pin "114") (pinfunction "(DQ1T),RUP4,IO_114") (pintype "input"))
    )
    (net (code "228") (name "unconnected-(U3-(DQS0L{slash}CQ1L,DPCLK0),DIFFIO_L4p,IO-Pad10)") (class "Default")
      (node (ref "U3") (pin "10") (pinfunction "(DQS0L/CQ1L,DPCLK0),DIFFIO_L4p,IO_10") (pintype "input"))
    )
    (net (code "229") (name "unconnected-(U3-(DQS1L{slash}CQ1L#,DPCLK1),DIFFIO_L8p,IO-Pad30)") (class "Default")
      (node (ref "U3") (pin "30") (pinfunction "(DQS1L/CQ1L#,DPCLK1),DIFFIO_L8p,IO_30") (pintype "input"))
    )
    (net (code "230") (name "unconnected-(U3-CLK2,DIFFCLK_1p-Pad24)") (class "Default")
      (node (ref "U3") (pin "24") (pinfunction "CLK2,DIFFCLK_1p_24") (pintype "input"))
    )
    (net (code "231") (name "unconnected-(U3-DIFFIO_B11p,IO-Pad52)") (class "Default")
      (node (ref "U3") (pin "52") (pinfunction "DIFFIO_B11p,IO_52") (pintype "input"))
    )
    (net (code "232") (name "unconnected-(U3-DIFFIO_L4n,IO-Pad11)") (class "Default")
      (node (ref "U3") (pin "11") (pinfunction "DIFFIO_L4n,IO_11") (pintype "input"))
    )
    (net (code "233") (name "unconnected-(U3-DIFFIO_L6n,IO-Pad28)") (class "Default")
      (node (ref "U3") (pin "28") (pinfunction "DIFFIO_L6n,IO_28") (pintype "input"))
    )
    (net (code "234") (name "unconnected-(U3-IO-Pad34)") (class "Default")
      (node (ref "U3") (pin "34") (pinfunction "IO_34") (pintype "input"))
    )
    (net (code "235") (name "unconnected-(U3-PLL1_CLKOUTn,IO-Pad44)") (class "Default")
      (node (ref "U3") (pin "44") (pinfunction "PLL1_CLKOUTn,IO_44") (pintype "input"))
    )
    (net (code "236") (name "unconnected-(U3-PLL1_CLKOUTp,IO-Pad43)") (class "Default")
      (node (ref "U3") (pin "43") (pinfunction "PLL1_CLKOUTp,IO_43") (pintype "input"))
    )
    (net (code "237") (name "unconnected-(U3-PLL2_CLKOUTp,IO-Pad113)") (class "Default")
      (node (ref "U3") (pin "113") (pinfunction "PLL2_CLKOUTp,IO_113") (pintype "input"))
    )
    (net (code "238") (name "unconnected-(U3-RDN1,IO-Pad33)") (class "Default")
      (node (ref "U3") (pin "33") (pinfunction "RDN1,IO_33") (pintype "input"))
    )
    (net (code "239") (name "unconnected-(U3-RDN3,IO-Pad77)") (class "Default")
      (node (ref "U3") (pin "77") (pinfunction "RDN3,IO_77") (pintype "input"))
    )
    (net (code "240") (name "unconnected-(U3-RUP1,IO-Pad32)") (class "Default")
      (node (ref "U3") (pin "32") (pinfunction "RUP1,IO_32") (pintype "input"))
    )
    (net (code "241") (name "unconnected-(U3-RUP3,IO-Pad76)") (class "Default")
      (node (ref "U3") (pin "76") (pinfunction "RUP3,IO_76") (pintype "input"))
    )
    (net (code "242") (name "unconnected-(U3-TDO-Pad20)") (class "Default")
      (node (ref "U3") (pin "20") (pinfunction "TDO_20") (pintype "input"))
    )
    (net (code "243") (name "unconnected-(U3-VREFB1N0,IO-Pad7)") (class "Default")
      (node (ref "U3") (pin "7") (pinfunction "VREFB1N0,IO_7") (pintype "input"))
    )
    (net (code "244") (name "unconnected-(U3-VREFB2N0,IO-Pad31)") (class "Default")
      (node (ref "U3") (pin "31") (pinfunction "VREFB2N0,IO_31") (pintype "input"))
    )
    (net (code "245") (name "unconnected-(U3-VREFB3N0,IO-Pad46)") (class "Default")
      (node (ref "U3") (pin "46") (pinfunction "VREFB3N0,IO_46") (pintype "input"))
    )
    (net (code "246") (name "unconnected-(U3-VREFB5N0,IO-Pad80)") (class "Default")
      (node (ref "U3") (pin "80") (pinfunction "VREFB5N0,IO_80") (pintype "input"))
    )
    (net (code "247") (name "unconnected-(U3-VREFB7N0,IO-Pad119)") (class "Default")
      (node (ref "U3") (pin "119") (pinfunction "VREFB7N0,IO_119") (pintype "input"))
    )
    (net (code "248") (name "unconnected-(U5-A0-Pad1)") (class "Default")
      (node (ref "U5") (pin "1") (pinfunction "A0_1") (pintype "unspecified"))
    )
    (net (code "249") (name "unconnected-(U5-A1-Pad2)") (class "Default")
      (node (ref "U5") (pin "2") (pinfunction "A1_2") (pintype "unspecified"))
    )
    (net (code "250") (name "unconnected-(U5-A2-Pad3)") (class "Default")
      (node (ref "U5") (pin "3") (pinfunction "A2_3") (pintype "unspecified"))
    )
    (net (code "251") (name "unconnected-(U5-WP-Pad7)") (class "Default")
      (node (ref "U5") (pin "7") (pinfunction "WP_7") (pintype "unspecified"))
    )
    (net (code "252") (name "unconnected-(U7-NC-Pad25)") (class "Default")
      (node (ref "U7") (pin "25") (pinfunction "NC_25") (pintype "unspecified"))
    )
    (net (code "253") (name "unconnected-(U7-NC-Pad26)") (class "Default")
      (node (ref "U7") (pin "26") (pinfunction "NC_26") (pintype "unspecified"))
    )
    (net (code "254") (name "unconnected-(U7-NC-Pad35)") (class "Default")
      (node (ref "U7") (pin "35") (pinfunction "NC_35") (pintype "unspecified"))
    )
    (net (code "255") (name "unconnected-(U7-NC-Pad36)") (class "Default")
      (node (ref "U7") (pin "36") (pinfunction "NC_36") (pintype "unspecified"))
    )
    (net (code "256") (name "unconnected-(U8-NC-Pad25)") (class "Default")
      (node (ref "U8") (pin "25") (pinfunction "NC_25") (pintype "unspecified"))
    )
    (net (code "257") (name "unconnected-(U8-NC-Pad26)") (class "Default")
      (node (ref "U8") (pin "26") (pinfunction "NC_26") (pintype "unspecified"))
    )
    (net (code "258") (name "unconnected-(U8-NC-Pad35)") (class "Default")
      (node (ref "U8") (pin "35") (pinfunction "NC_35") (pintype "unspecified"))
    )
    (net (code "259") (name "unconnected-(U8-NC-Pad36)") (class "Default")
      (node (ref "U8") (pin "36") (pinfunction "NC_36") (pintype "unspecified"))
    )
    (net (code "260") (name "unconnected-(U9-EP-Pad9)") (class "Default")
      (node (ref "U9") (pin "9") (pinfunction "EP_9") (pintype "unspecified"))
    )
    (net (code "261") (name "unconnected-(U10-CHRG#-Pad7)") (class "Default")
      (node (ref "U10") (pin "7") (pinfunction "CHRG#_7") (pintype "unspecified"))
    )
    (net (code "262") (name "unconnected-(U10-EP-Pad9)") (class "Default")
      (node (ref "U10") (pin "9") (pinfunction "EP_9") (pintype "unspecified"))
    )
    (net (code "263") (name "unconnected-(U10-STDBY#-Pad6)") (class "Default")
      (node (ref "U10") (pin "6") (pinfunction "STDBY#_6") (pintype "unspecified"))
    )
    (net (code "264") (name "unconnected-(USB1-CC1-PadA5)") (class "Default")
      (node (ref "USB1") (pin "A5") (pinfunction "CC1_A5") (pintype "unspecified"))
    )
    (net (code "265") (name "unconnected-(USB1-CC2-PadB5)") (class "Default")
      (node (ref "USB1") (pin "B5") (pinfunction "CC2_B5") (pintype "unspecified"))
    )
    (net (code "266") (name "unconnected-(USB1-Pad13)") (class "Default")
      (node (ref "USB1") (pin "13") (pinfunction "13_13") (pintype "unspecified"))
    )
    (net (code "267") (name "unconnected-(USB1-Pad14)") (class "Default")
      (node (ref "USB1") (pin "14") (pinfunction "14_14") (pintype "unspecified"))
    )
    (net (code "268") (name "unconnected-(USB1-Pad15)") (class "Default")
      (node (ref "USB1") (pin "15") (pinfunction "15_15") (pintype "unspecified"))
    )
    (net (code "269") (name "unconnected-(USB1-Pad16)") (class "Default")
      (node (ref "USB1") (pin "16") (pinfunction "16_16") (pintype "unspecified"))
    )
    (net (code "270") (name "unconnected-(USB1-SBU1-PadA8)") (class "Default")
      (node (ref "USB1") (pin "A8") (pinfunction "SBU1_A8") (pintype "unspecified"))
    )
    (net (code "271") (name "unconnected-(USB1-SBU2-PadB8)") (class "Default")
      (node (ref "USB1") (pin "B8") (pinfunction "SBU2_B8") (pintype "unspecified"))
    )
  )
)
